# DAC__Sources.net
KiCad netlist of a schematic drawn in Altium Designer
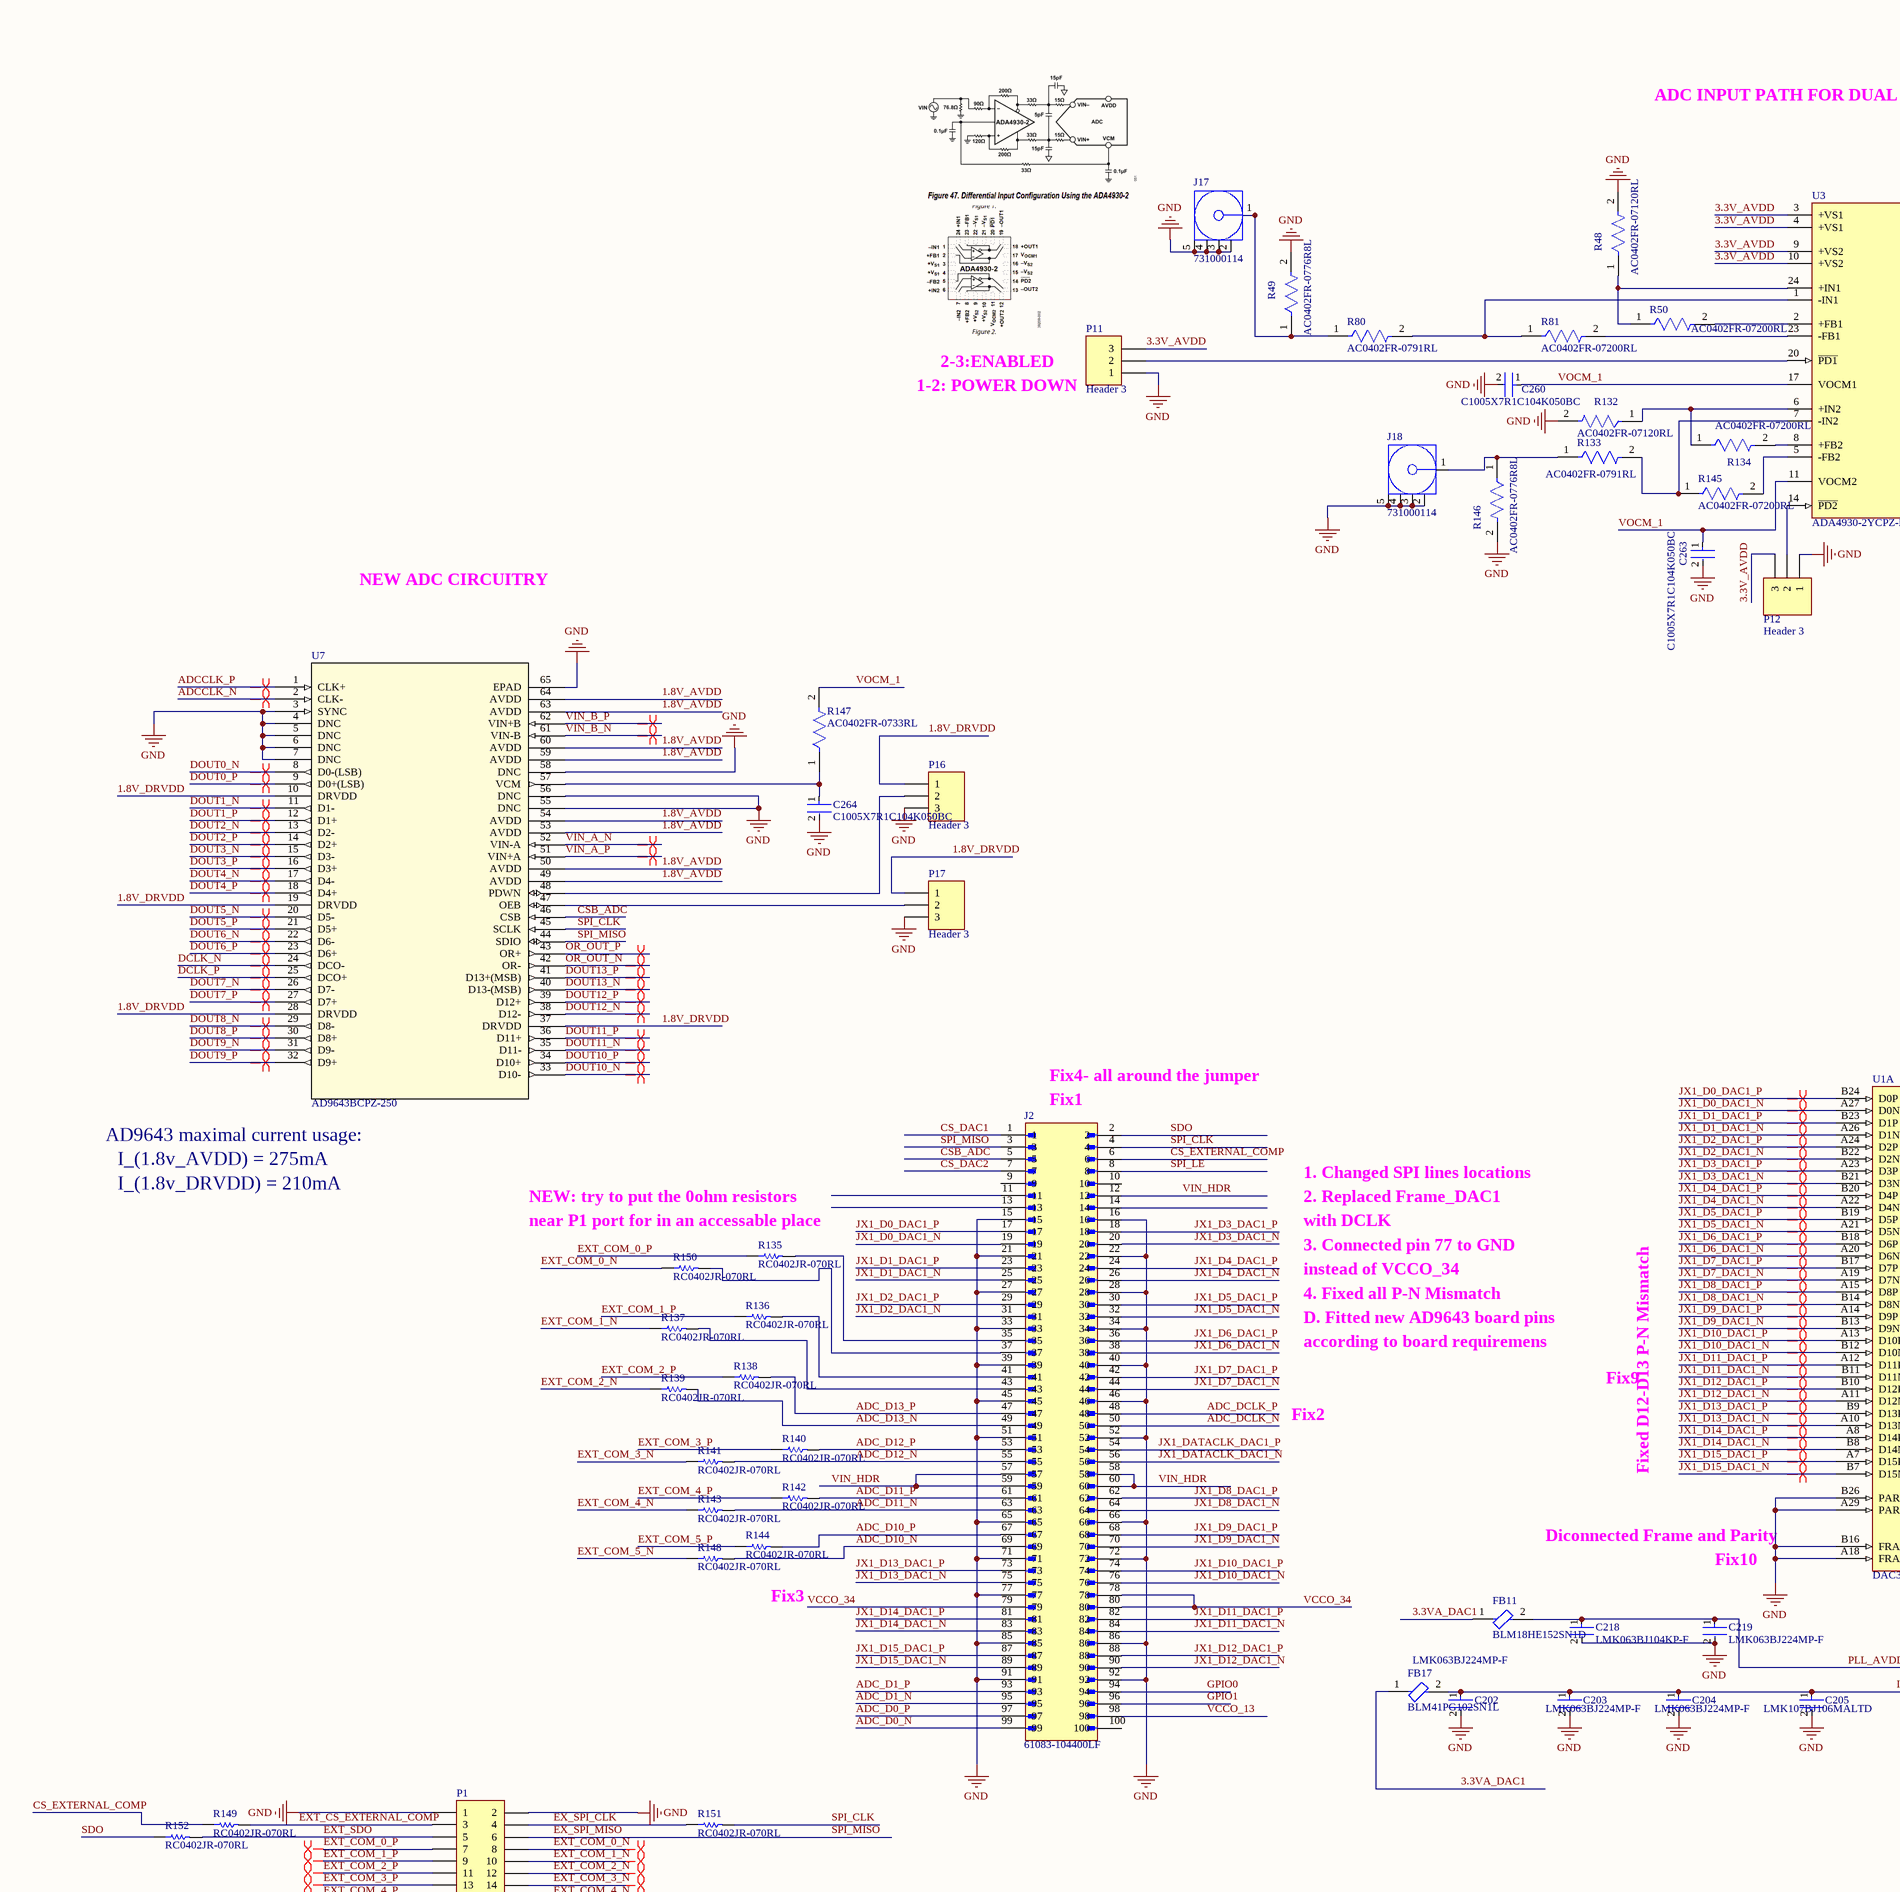
[diagram p0: DACֹֹ_Sources.SchDoc, top left]
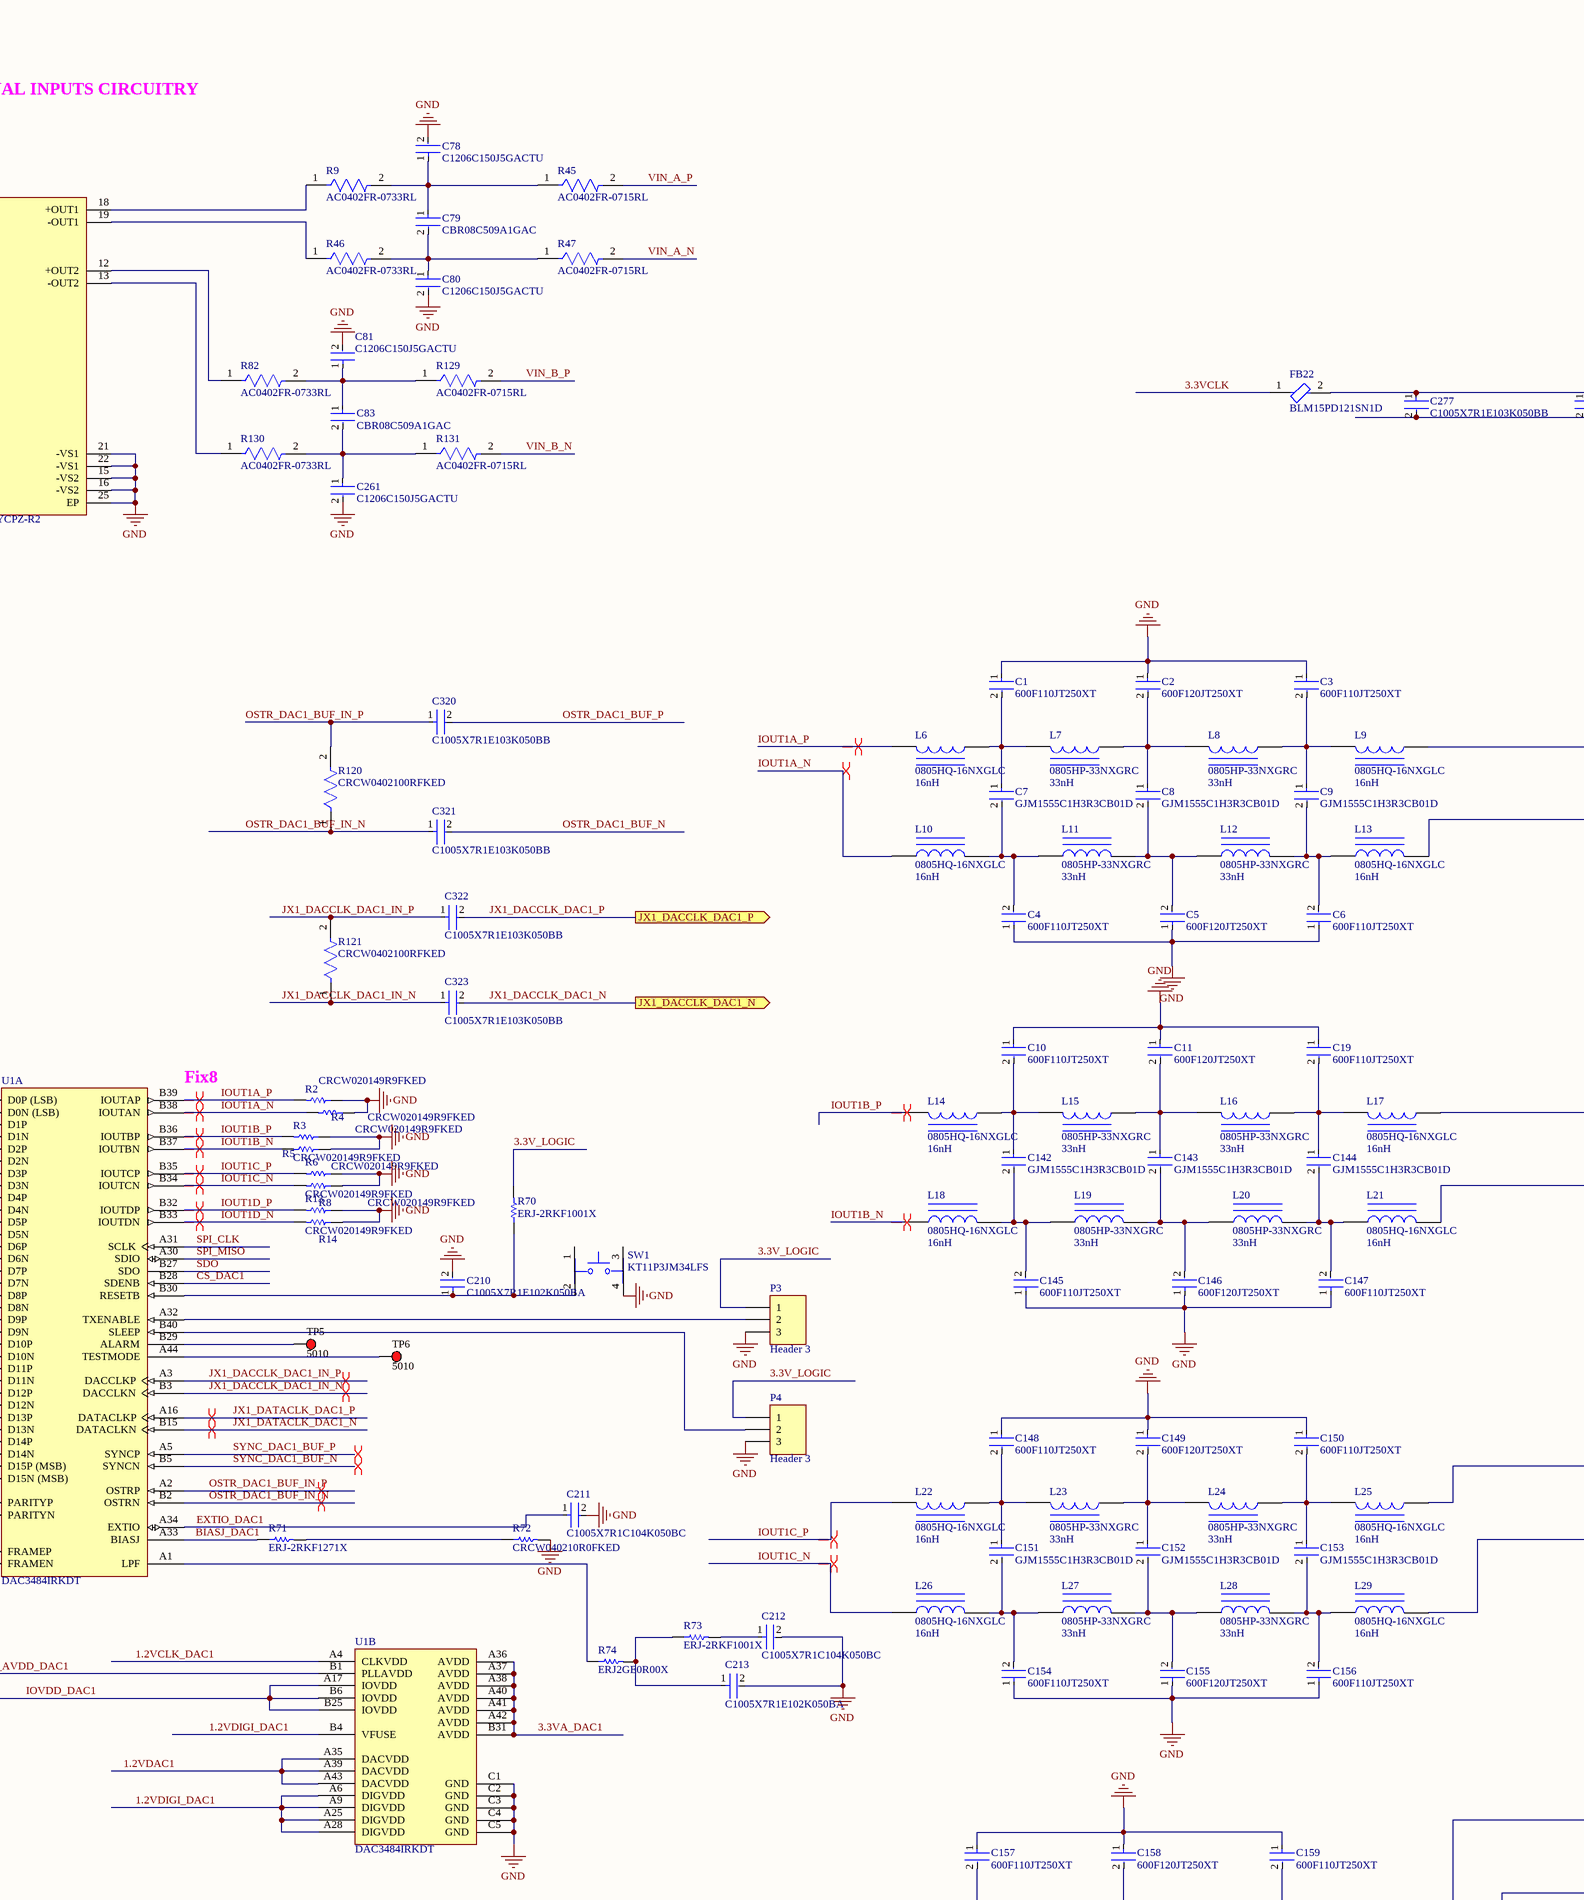
[diagram p1: DACֹֹ_Sources.SchDoc, top middle]
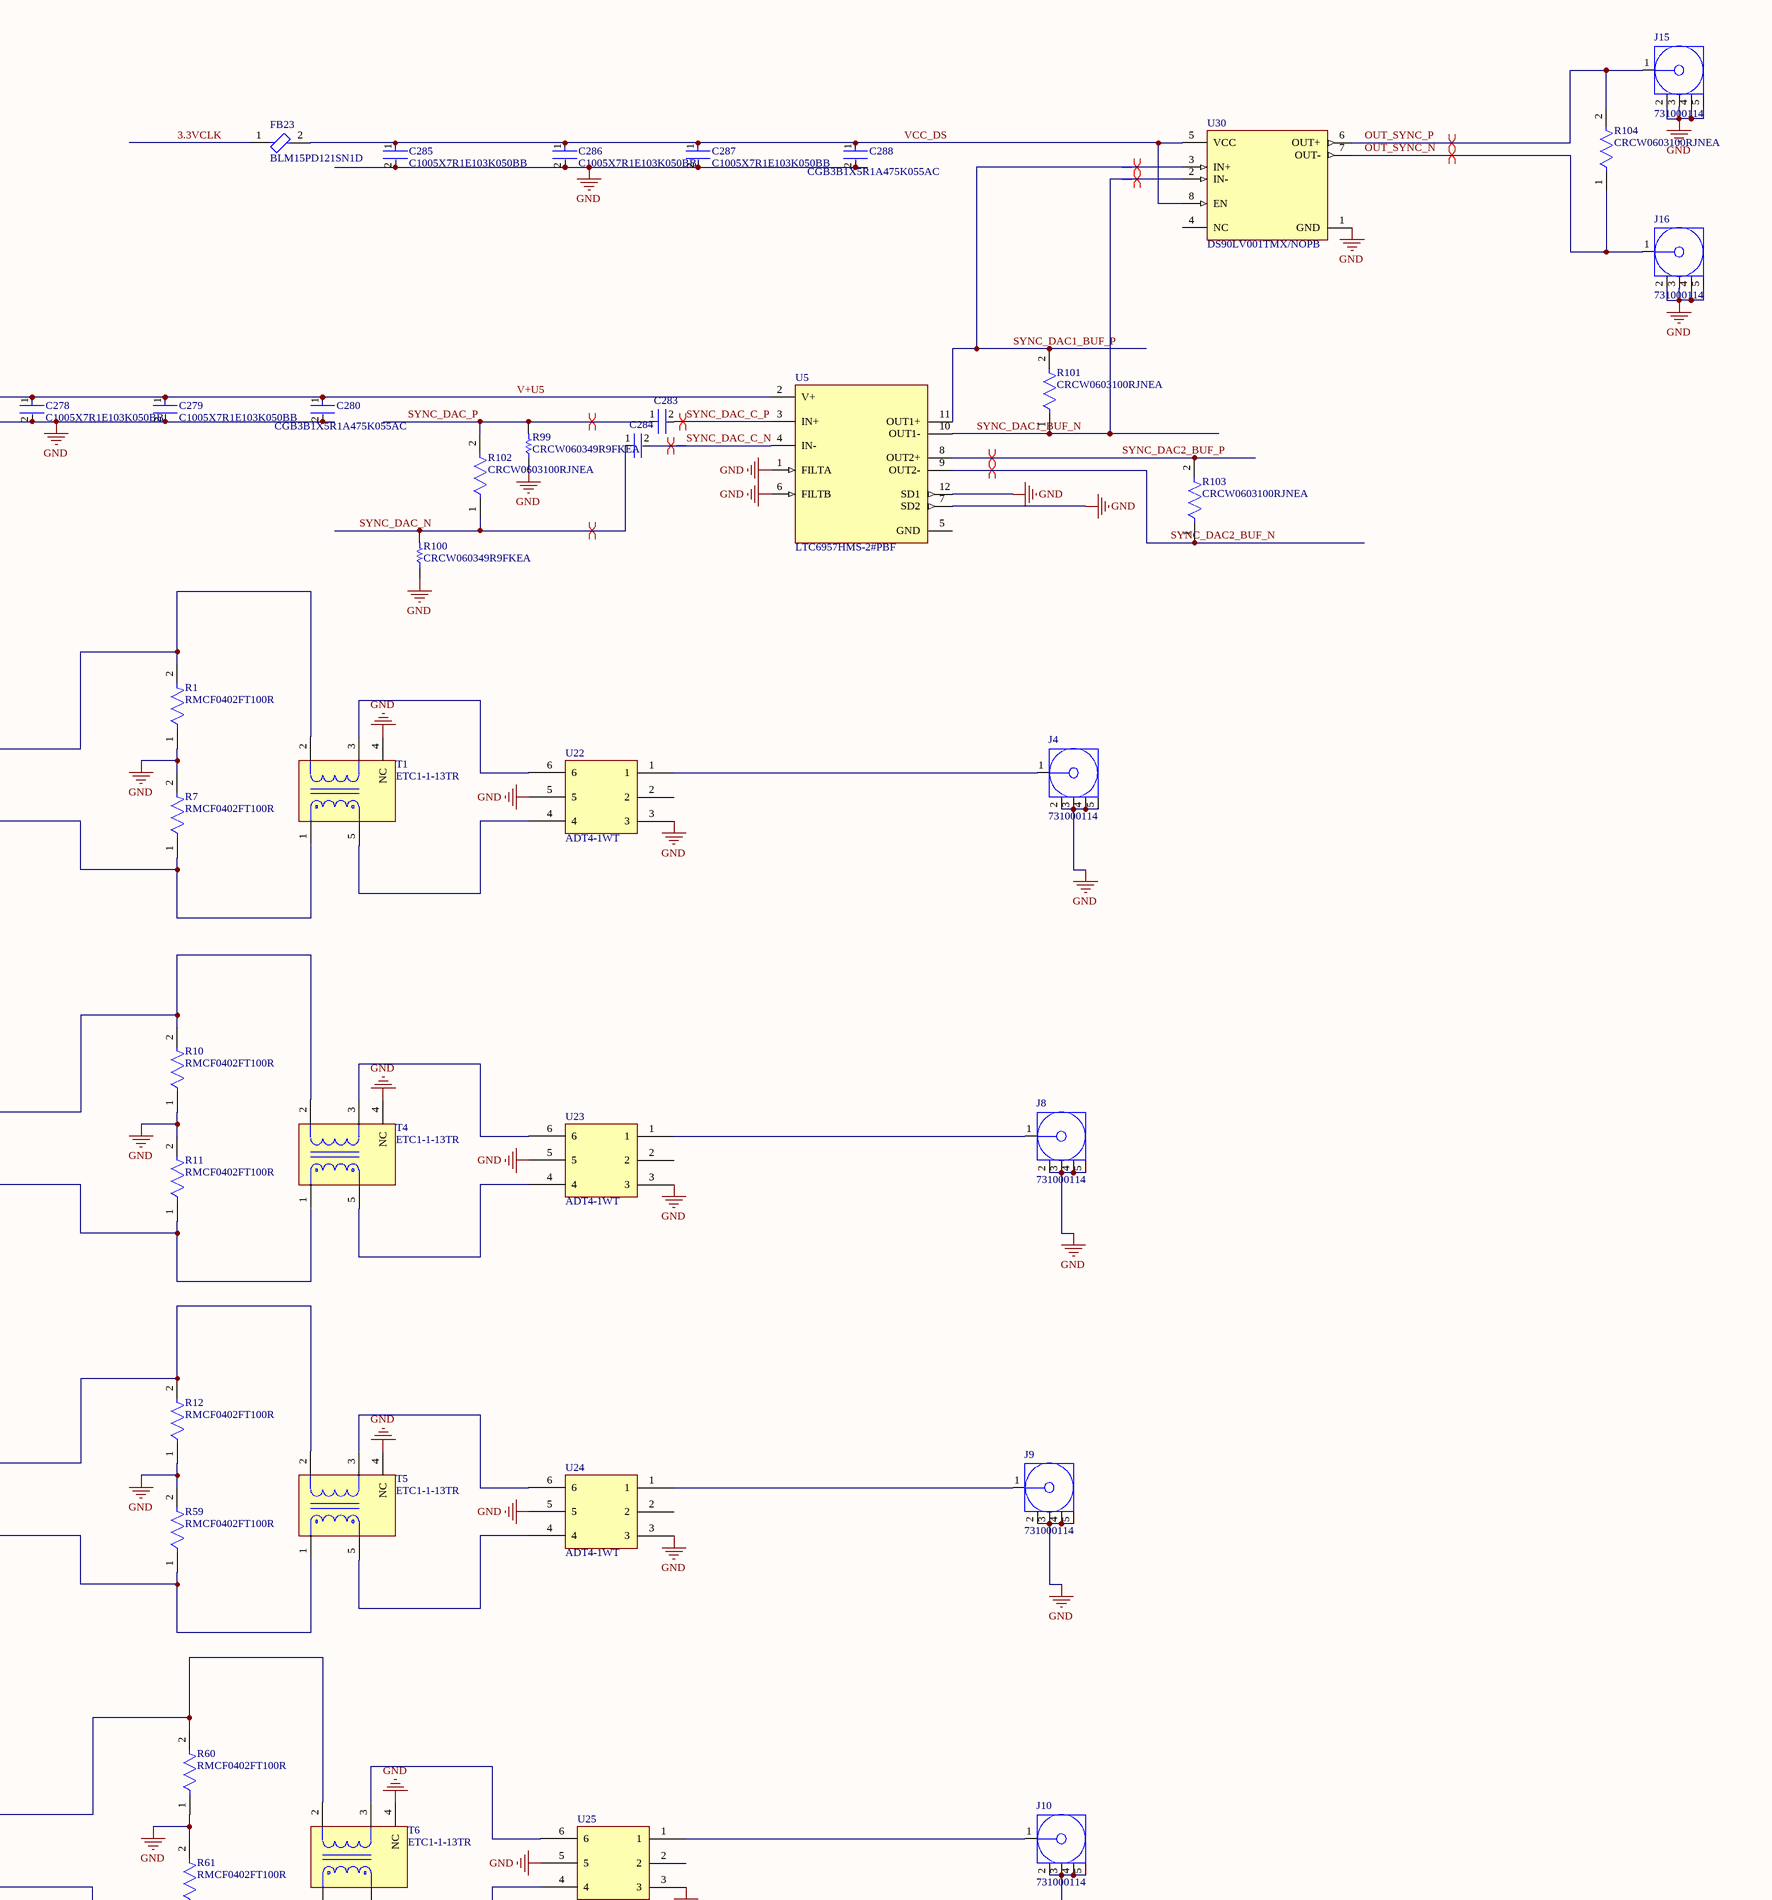
[diagram p2: DACֹֹ_Sources.SchDoc, top right]
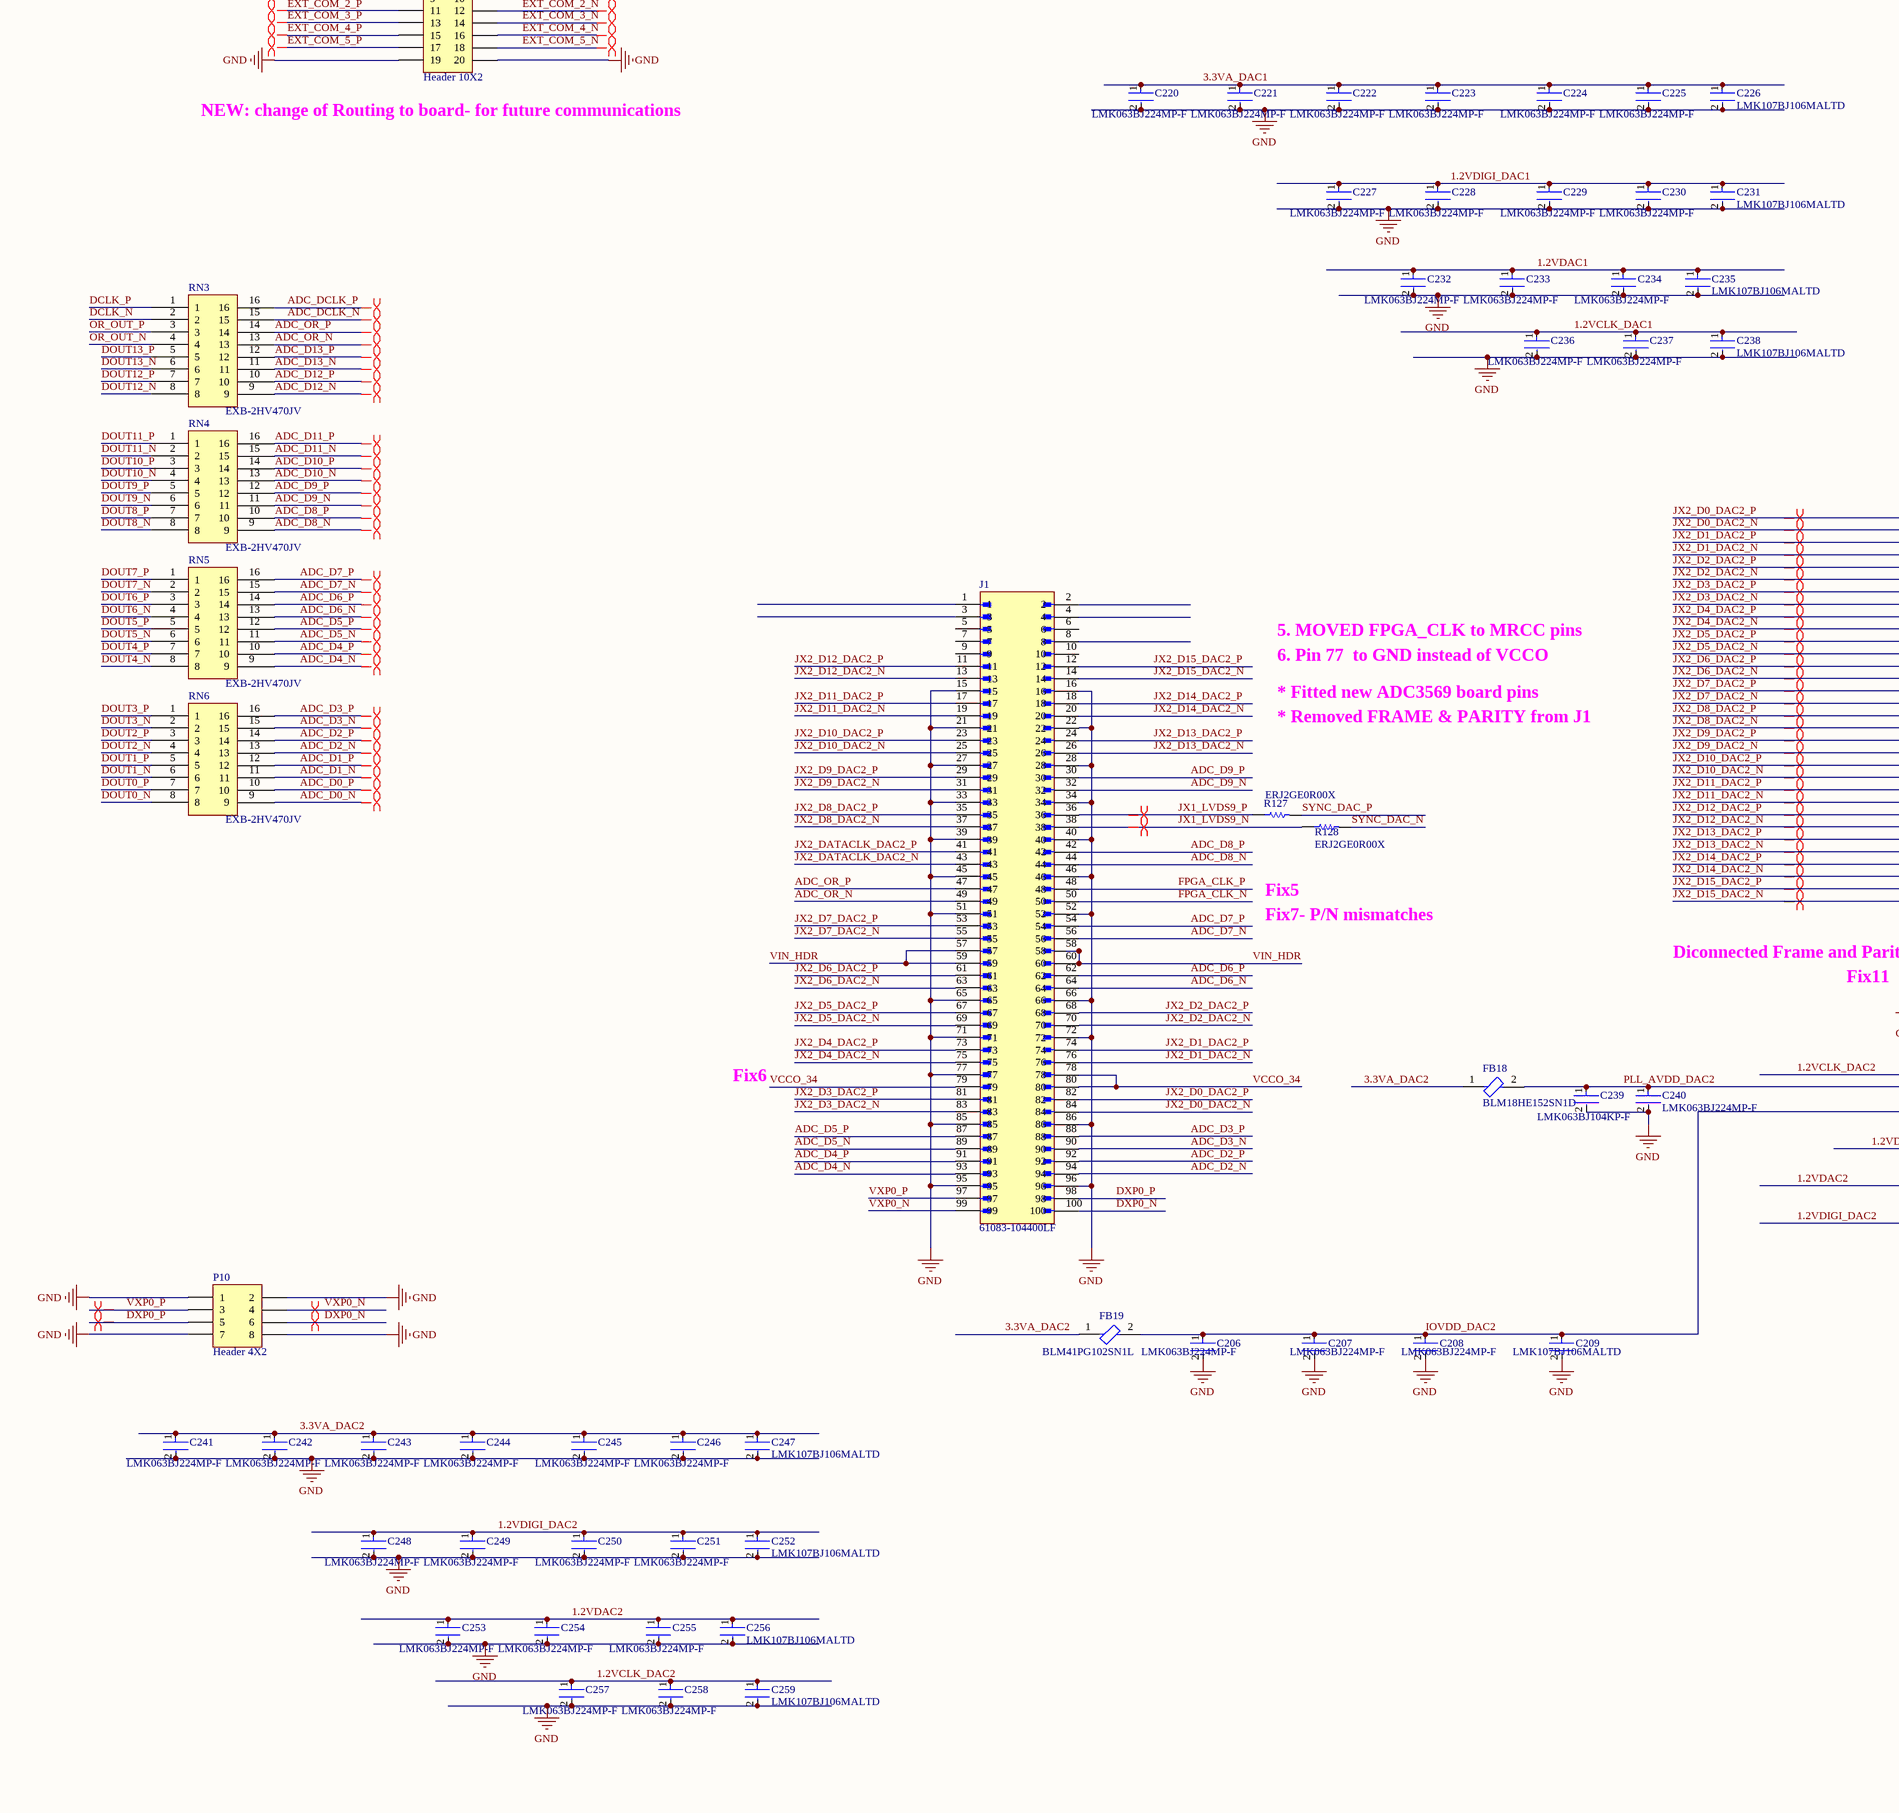
[diagram p3: DACֹֹ_Sources.SchDoc, bottom left]
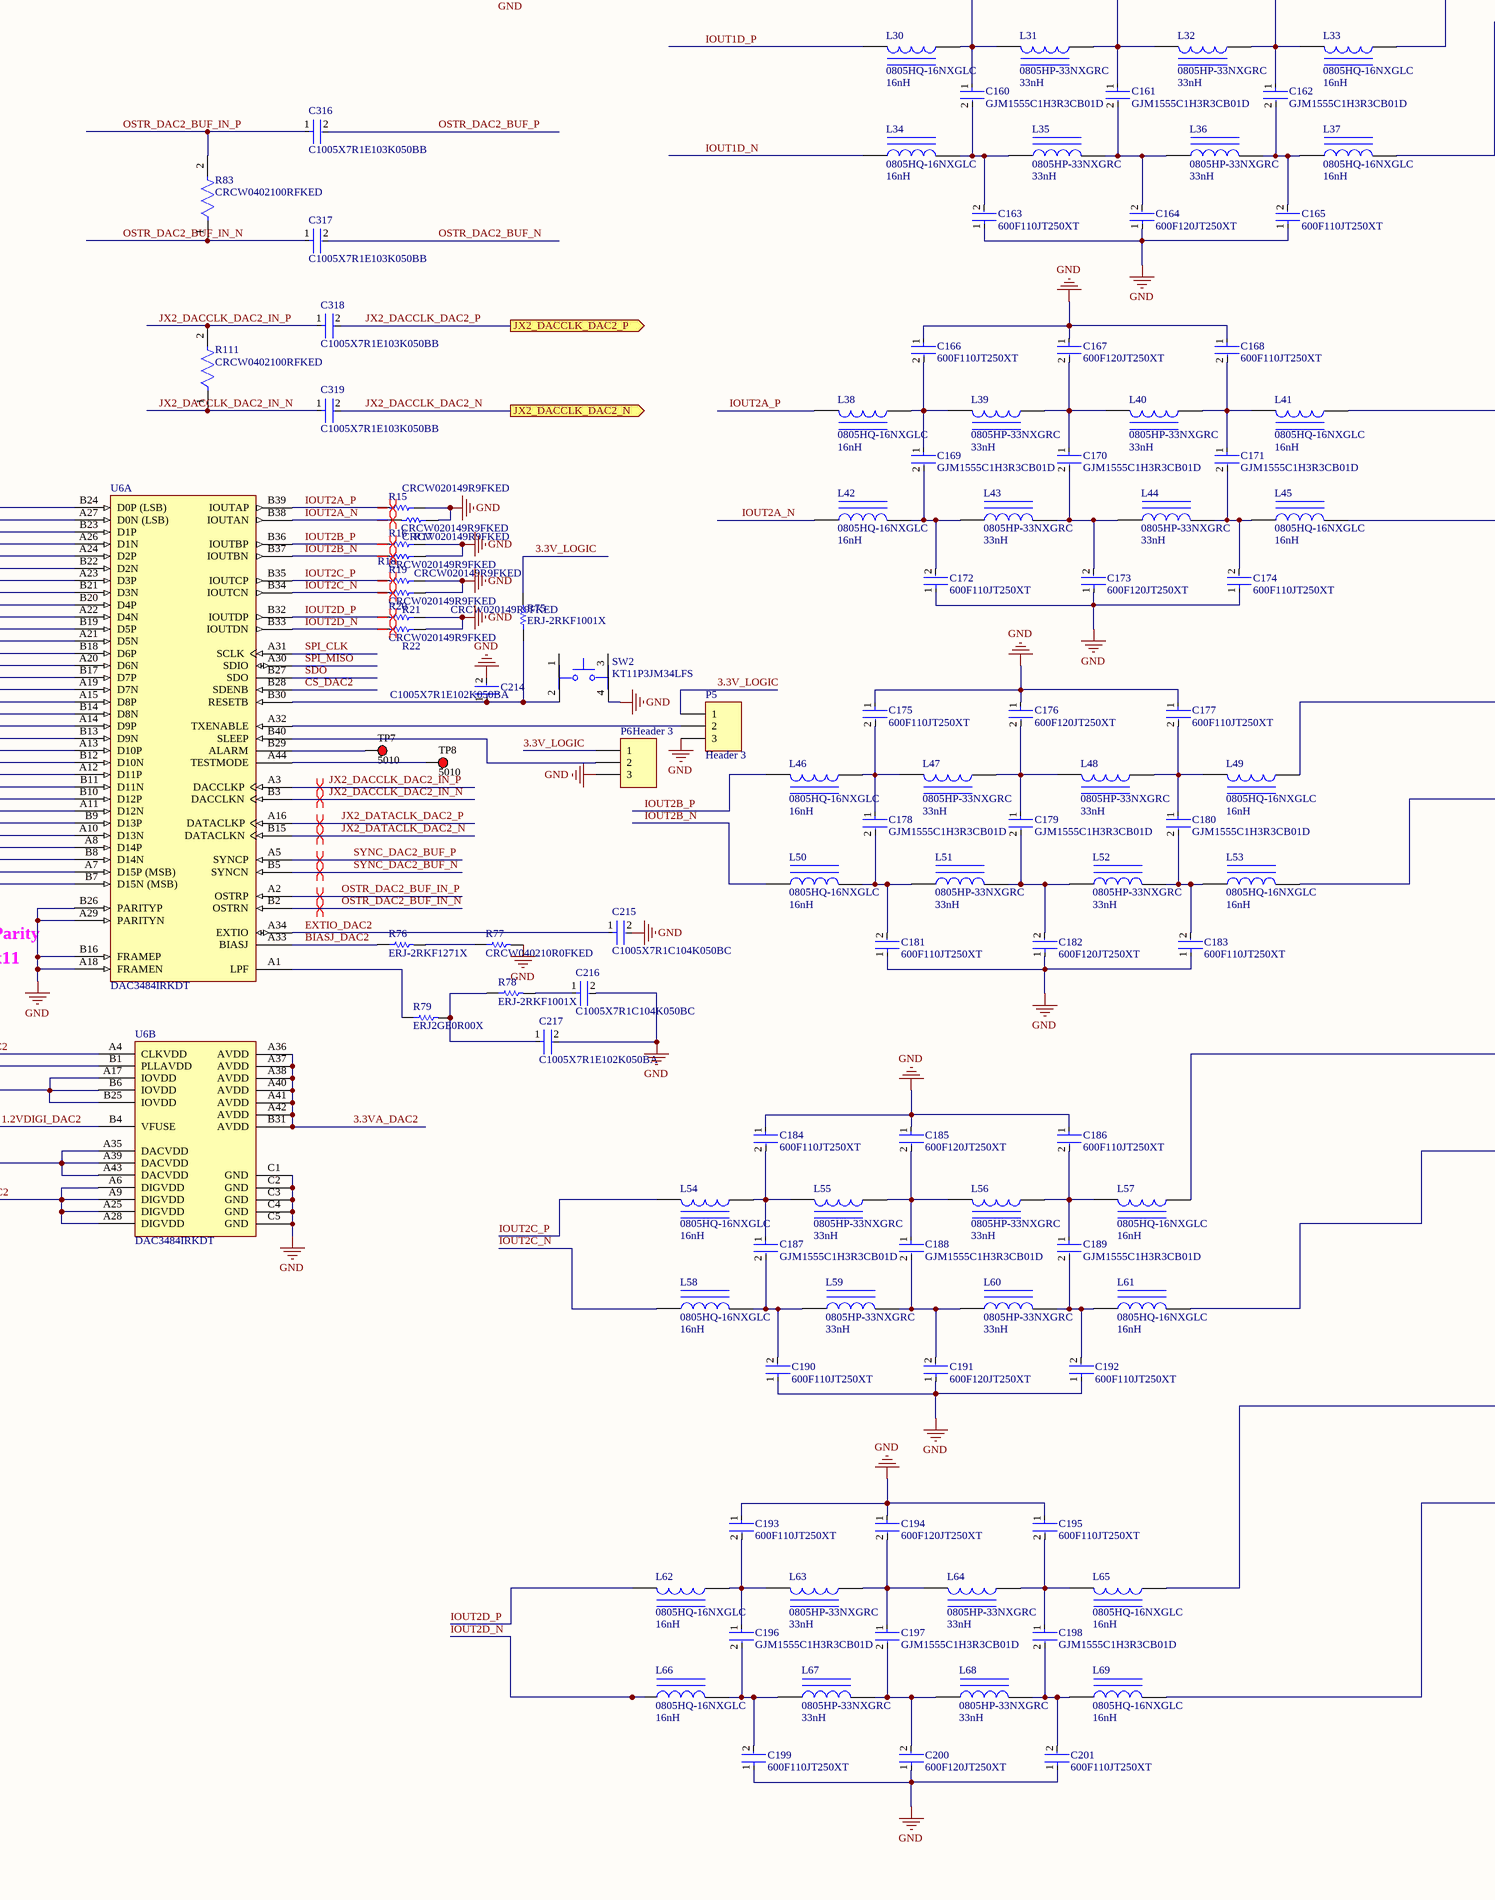
[diagram p4: DACֹֹ_Sources.SchDoc, bottom middle]
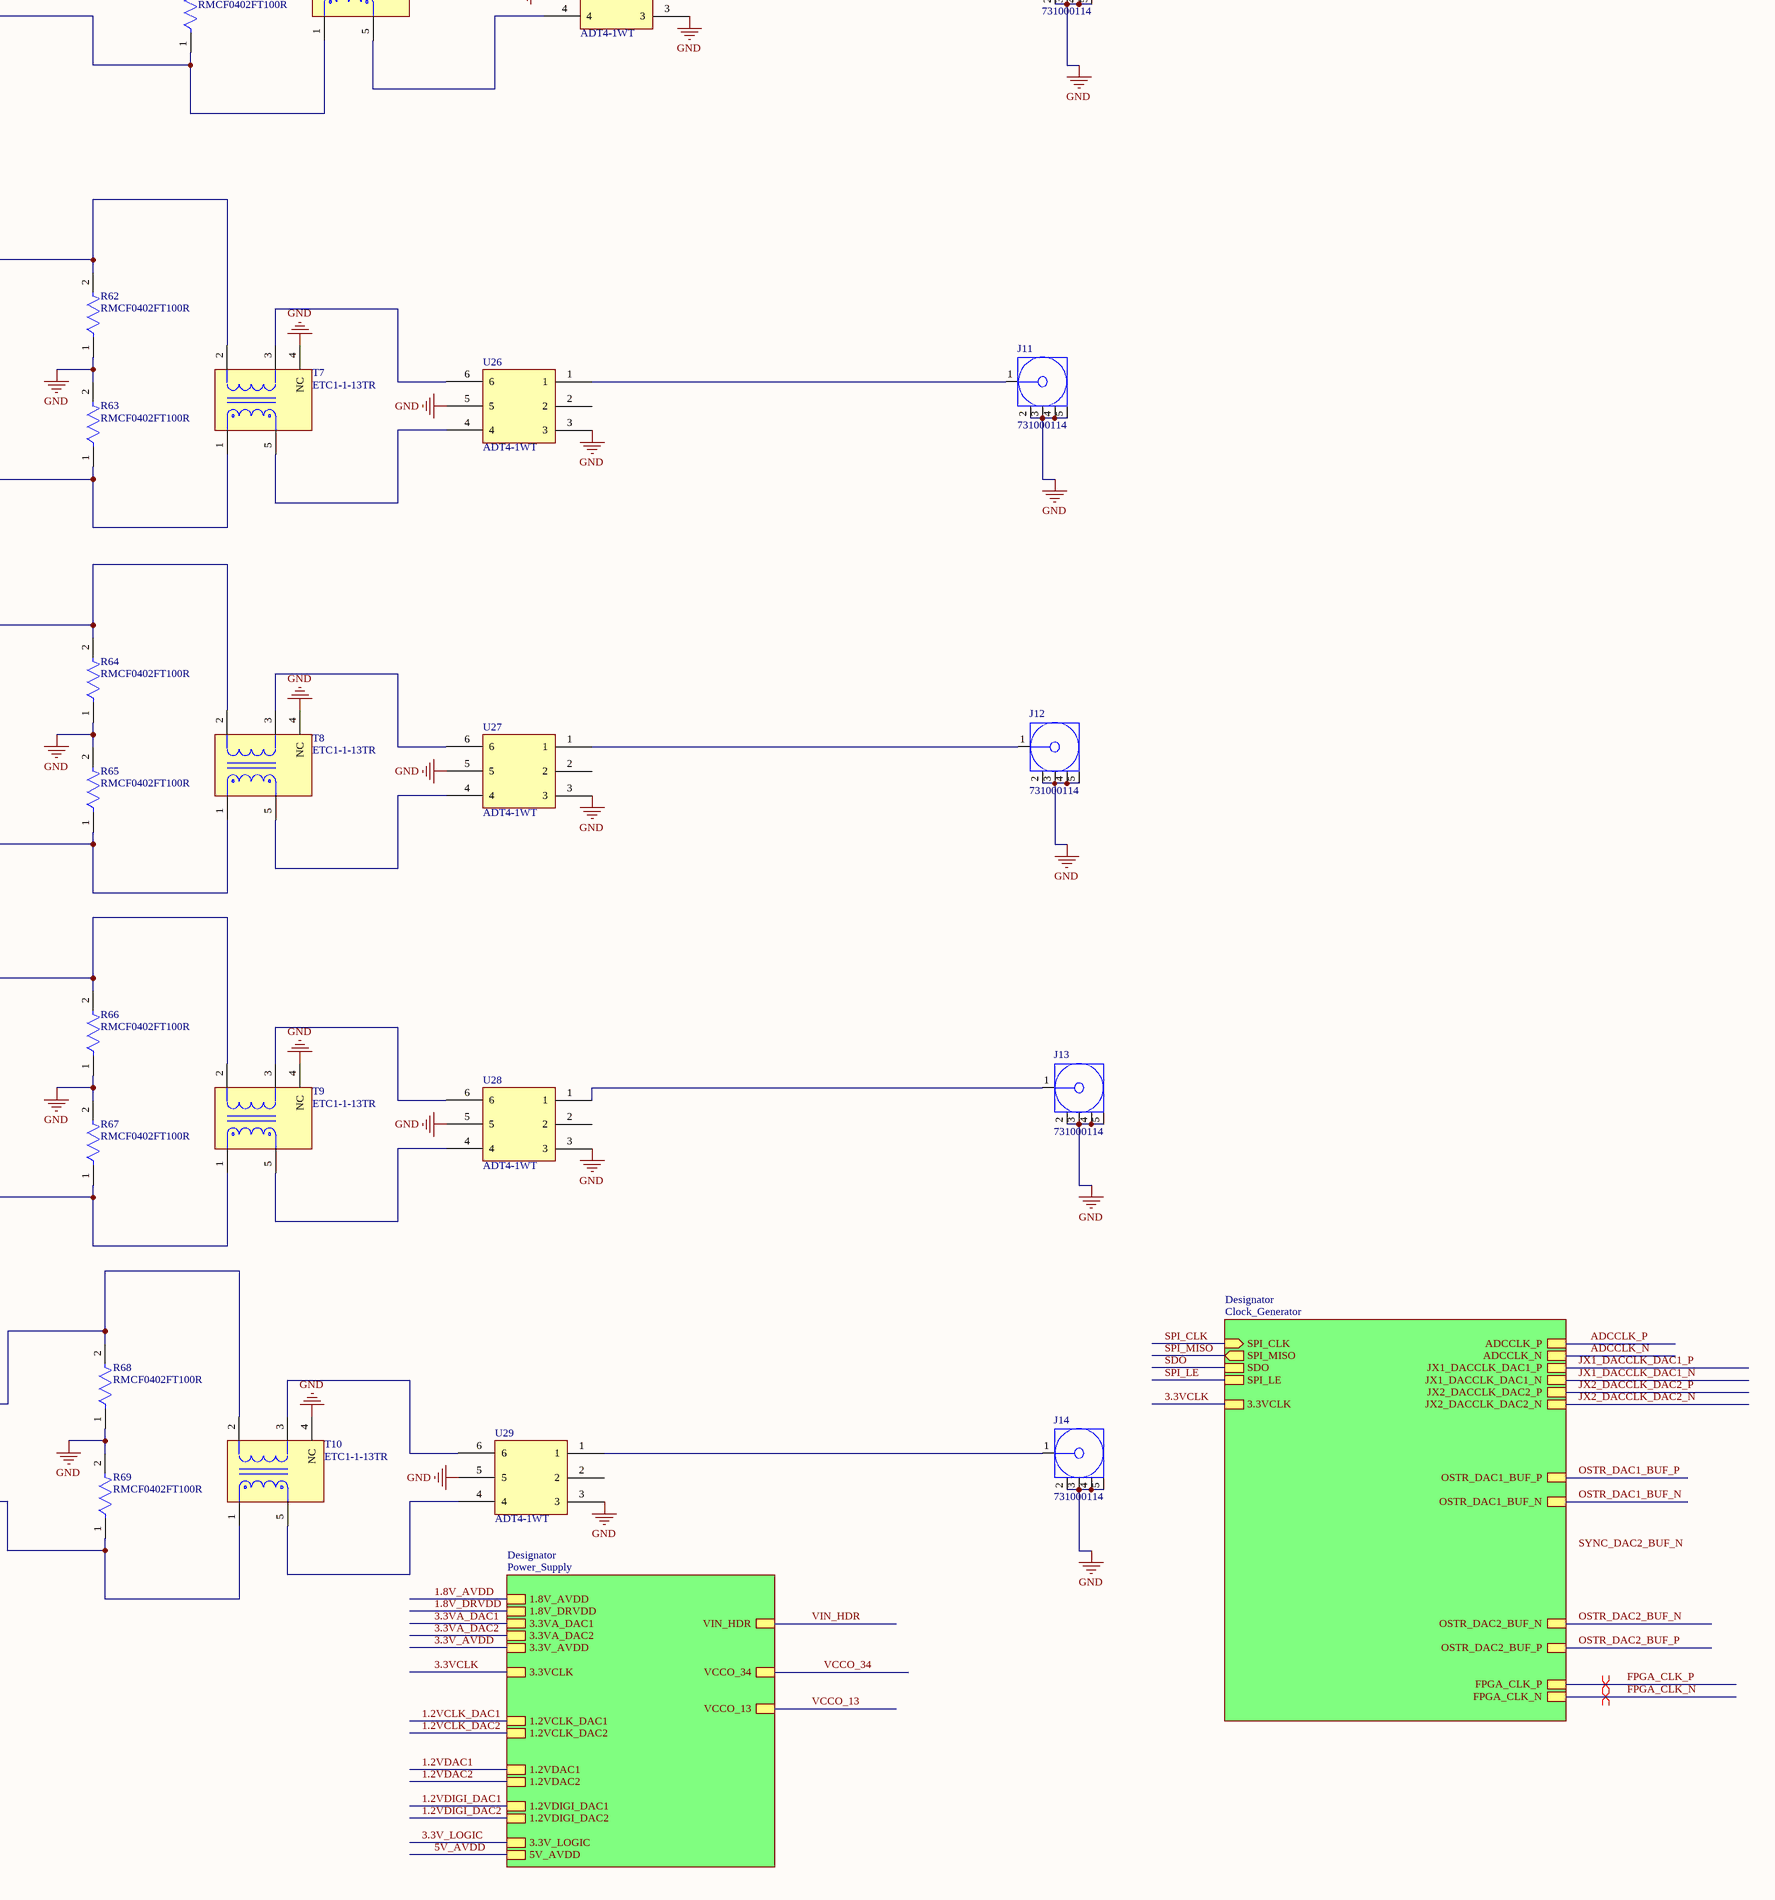
[diagram p5: DACֹֹ_Sources.SchDoc, bottom right]

(export (version "E")
  (design (tool "Eeschema 10.0.6"))
  (components
    (comp (ref "C1")
      (value "600F110JT250XT")
      (footprint "C0805")
      (description "CAP CER 11PF 50V 5% NP0 0805")
      (fields (field (name "TOLERANCE") "0.05") (field (name "MANUFACTURER PART NUMBER") "C0805C110J5GACTU"))
      (libsource (lib "DACֹֹ_Sources") (part "b4654b650e69147ec39a6b967a45e02"))
    )
    (comp (ref "C2")
      (value "600F120JT250XT")
      (footprint "C0805")
      (description "CAP CER 11PF 50V 5% NP0 0805")
      (fields (field (name "TOLERANCE") "0.05") (field (name "MANUFACTURER PART NUMBER") "C0805C110J5GACTU"))
      (libsource (lib "DACֹֹ_Sources") (part "b4654b650e69147ec39a6b967a45e02"))
    )
    (comp (ref "C3")
      (value "600F110JT250XT")
      (footprint "C0805")
      (description "CAP CER 11PF 50V 5% NP0 0805")
      (fields (field (name "TOLERANCE") "0.05") (field (name "MANUFACTURER PART NUMBER") "C0805C110J5GACTU"))
      (libsource (lib "DACֹֹ_Sources") (part "b4654b650e69147ec39a6b967a45e02"))
    )
    (comp (ref "C4")
      (value "600F110JT250XT")
      (footprint "C0805")
      (description "CAP CER 11PF 50V 5% NP0 0805")
      (fields (field (name "TOLERANCE") "0.05") (field (name "MANUFACTURER PART NUMBER") "C0805C110J5GACTU"))
      (libsource (lib "DACֹֹ_Sources") (part "b4654b650e69147ec39a6b967a45e02"))
    )
    (comp (ref "C5")
      (value "600F120JT250XT")
      (footprint "C0805")
      (description "CAP CER 11PF 50V 5% NP0 0805")
      (fields (field (name "TOLERANCE") "0.05") (field (name "MANUFACTURER PART NUMBER") "C0805C110J5GACTU"))
      (libsource (lib "DACֹֹ_Sources") (part "b4654b650e69147ec39a6b967a45e02"))
    )
    (comp (ref "C6")
      (value "600F110JT250XT")
      (footprint "C0805")
      (description "CAP CER 11PF 50V 5% NP0 0805")
      (fields (field (name "TOLERANCE") "0.05") (field (name "MANUFACTURER PART NUMBER") "C0805C110J5GACTU"))
      (libsource (lib "DACֹֹ_Sources") (part "b4654b650e69147ec39a6b967a45e02"))
    )
    (comp (ref "C7")
      (value "GJM1555C1H3R3CB01D")
      (footprint "C0402")
      (description "Multi-Layer Ceramic Capacitor 3.3pF C0G  ±0.25pF 0402 Paper T/R")
      (fields (field (name "VOLTAGE") "50V"))
      (libsource (lib "DACֹֹ_Sources") (part "02cd4be3c70576c341d710602a673aa"))
    )
    (comp (ref "C8")
      (value "GJM1555C1H3R3CB01D")
      (footprint "C0402")
      (description "Multi-Layer Ceramic Capacitor 3.3pF C0G  ±0.25pF 0402 Paper T/R")
      (fields (field (name "VOLTAGE") "50V"))
      (libsource (lib "DACֹֹ_Sources") (part "02cd4be3c70576c341d710602a673aa"))
    )
    (comp (ref "C9")
      (value "GJM1555C1H3R3CB01D")
      (footprint "C0402")
      (description "Multi-Layer Ceramic Capacitor 3.3pF C0G  ±0.25pF 0402 Paper T/R")
      (fields (field (name "VOLTAGE") "50V"))
      (libsource (lib "DACֹֹ_Sources") (part "02cd4be3c70576c341d710602a673aa"))
    )
    (comp (ref "C10")
      (value "600F110JT250XT")
      (footprint "C0805")
      (description "CAP CER 11PF 50V 5% NP0 0805")
      (fields (field (name "TOLERANCE") "0.05") (field (name "MANUFACTURER PART NUMBER") "C0805C110J5GACTU"))
      (libsource (lib "DACֹֹ_Sources") (part "b4654b650e69147ec39a6b967a45e02"))
    )
    (comp (ref "C11")
      (value "600F120JT250XT")
      (footprint "C0805")
      (description "CAP CER 11PF 50V 5% NP0 0805")
      (fields (field (name "TOLERANCE") "0.05") (field (name "MANUFACTURER PART NUMBER") "C0805C110J5GACTU"))
      (libsource (lib "DACֹֹ_Sources") (part "b4654b650e69147ec39a6b967a45e02"))
    )
    (comp (ref "C19")
      (value "600F110JT250XT")
      (footprint "C0805")
      (description "CAP CER 11PF 50V 5% NP0 0805")
      (fields (field (name "TOLERANCE") "0.05") (field (name "MANUFACTURER PART NUMBER") "C0805C110J5GACTU"))
      (libsource (lib "DACֹֹ_Sources") (part "b4654b650e69147ec39a6b967a45e02"))
    )
    (comp (ref "C78")
      (value "C1206C150J5GACTU")
      (footprint "C1206")
      (description "1206 C 15pF Ceramic Multilayer Capacitor; 50 VDC; +125degC; C0G Dielec; +/-5%")
      (fields (field (name "TOLERANCE") "0.05") (field (name "MANUFACTURER") "KEMET"))
      (libsource (lib "Simulation Generic Components") (part "b4654b650e69147ec39a6b967a45e02"))
    )
    (comp (ref "C79")
      (value "CBR08C509A1GAC")
      (footprint "C0805")
      (description "CAP CER 5PF 100V NP0 0805")
      (fields (field (name "TOLERANCE") "0.05 pF") (field (name "MANUFACTURER") "KEMET"))
      (libsource (lib "Simulation Generic Components") (part "11868f565c42a9108669ba33697ecf6"))
    )
    (comp (ref "C80")
      (value "C1206C150J5GACTU")
      (footprint "C1206")
      (description "1206 C 15pF Ceramic Multilayer Capacitor; 50 VDC; +125degC; C0G Dielec; +/-5%")
      (fields (field (name "TOLERANCE") "0.05") (field (name "MANUFACTURER") "KEMET"))
      (libsource (lib "Simulation Generic Components") (part "b4654b650e69147ec39a6b967a45e02"))
    )
    (comp (ref "C81")
      (value "C1206C150J5GACTU")
      (footprint "C1206")
      (description "1206 C 15pF Ceramic Multilayer Capacitor; 50 VDC; +125degC; C0G Dielec; +/-5%")
      (fields (field (name "TOLERANCE") "0.05") (field (name "MANUFACTURER") "KEMET"))
      (libsource (lib "Simulation Generic Components") (part "b4654b650e69147ec39a6b967a45e02"))
    )
    (comp (ref "C83")
      (value "CBR08C509A1GAC")
      (footprint "C0805")
      (description "CAP CER 5PF 100V NP0 0805")
      (fields (field (name "TOLERANCE") "0.05 pF") (field (name "MANUFACTURER") "KEMET"))
      (libsource (lib "Simulation Generic Components") (part "11868f565c42a9108669ba33697ecf6"))
    )
    (comp (ref "C142")
      (value "GJM1555C1H3R3CB01D")
      (footprint "C0402")
      (description "Multi-Layer Ceramic Capacitor 3.3pF C0G  ±0.25pF 0402 Paper T/R")
      (fields (field (name "VOLTAGE") "50V"))
      (libsource (lib "DACֹֹ_Sources") (part "02cd4be3c70576c341d710602a673aa"))
    )
    (comp (ref "C143")
      (value "GJM1555C1H3R3CB01D")
      (footprint "C0402")
      (description "Multi-Layer Ceramic Capacitor 3.3pF C0G  ±0.25pF 0402 Paper T/R")
      (fields (field (name "VOLTAGE") "50V"))
      (libsource (lib "DACֹֹ_Sources") (part "02cd4be3c70576c341d710602a673aa"))
    )
    (comp (ref "C144")
      (value "GJM1555C1H3R3CB01D")
      (footprint "C0402")
      (description "Multi-Layer Ceramic Capacitor 3.3pF C0G  ±0.25pF 0402 Paper T/R")
      (fields (field (name "VOLTAGE") "50V"))
      (libsource (lib "DACֹֹ_Sources") (part "02cd4be3c70576c341d710602a673aa"))
    )
    (comp (ref "C145")
      (value "600F110JT250XT")
      (footprint "C0805")
      (description "CAP CER 11PF 50V 5% NP0 0805")
      (fields (field (name "TOLERANCE") "0.05") (field (name "MANUFACTURER PART NUMBER") "C0805C110J5GACTU"))
      (libsource (lib "DACֹֹ_Sources") (part "b4654b650e69147ec39a6b967a45e02"))
    )
    (comp (ref "C146")
      (value "600F120JT250XT")
      (footprint "C0805")
      (description "CAP CER 11PF 50V 5% NP0 0805")
      (fields (field (name "TOLERANCE") "0.05") (field (name "MANUFACTURER PART NUMBER") "C0805C110J5GACTU"))
      (libsource (lib "DACֹֹ_Sources") (part "b4654b650e69147ec39a6b967a45e02"))
    )
    (comp (ref "C147")
      (value "600F110JT250XT")
      (footprint "C0805")
      (description "CAP CER 11PF 50V 5% NP0 0805")
      (fields (field (name "TOLERANCE") "0.05") (field (name "MANUFACTURER PART NUMBER") "C0805C110J5GACTU"))
      (libsource (lib "DACֹֹ_Sources") (part "b4654b650e69147ec39a6b967a45e02"))
    )
    (comp (ref "C148")
      (value "600F110JT250XT")
      (footprint "C0805")
      (description "CAP CER 11PF 50V 5% NP0 0805")
      (fields (field (name "TOLERANCE") "0.05") (field (name "MANUFACTURER PART NUMBER") "C0805C110J5GACTU"))
      (libsource (lib "DACֹֹ_Sources") (part "b4654b650e69147ec39a6b967a45e02"))
    )
    (comp (ref "C149")
      (value "600F120JT250XT")
      (footprint "C0805")
      (description "CAP CER 11PF 50V 5% NP0 0805")
      (fields (field (name "TOLERANCE") "0.05") (field (name "MANUFACTURER PART NUMBER") "C0805C110J5GACTU"))
      (libsource (lib "DACֹֹ_Sources") (part "b4654b650e69147ec39a6b967a45e02"))
    )
    (comp (ref "C150")
      (value "600F110JT250XT")
      (footprint "C0805")
      (description "CAP CER 11PF 50V 5% NP0 0805")
      (fields (field (name "TOLERANCE") "0.05") (field (name "MANUFACTURER PART NUMBER") "C0805C110J5GACTU"))
      (libsource (lib "DACֹֹ_Sources") (part "b4654b650e69147ec39a6b967a45e02"))
    )
    (comp (ref "C151")
      (value "GJM1555C1H3R3CB01D")
      (footprint "C0402")
      (description "Multi-Layer Ceramic Capacitor 3.3pF C0G  ±0.25pF 0402 Paper T/R")
      (fields (field (name "VOLTAGE") "50V"))
      (libsource (lib "DACֹֹ_Sources") (part "02cd4be3c70576c341d710602a673aa"))
    )
    (comp (ref "C152")
      (value "GJM1555C1H3R3CB01D")
      (footprint "C0402")
      (description "Multi-Layer Ceramic Capacitor 3.3pF C0G  ±0.25pF 0402 Paper T/R")
      (fields (field (name "VOLTAGE") "50V"))
      (libsource (lib "DACֹֹ_Sources") (part "02cd4be3c70576c341d710602a673aa"))
    )
    (comp (ref "C153")
      (value "GJM1555C1H3R3CB01D")
      (footprint "C0402")
      (description "Multi-Layer Ceramic Capacitor 3.3pF C0G  ±0.25pF 0402 Paper T/R")
      (fields (field (name "VOLTAGE") "50V"))
      (libsource (lib "DACֹֹ_Sources") (part "02cd4be3c70576c341d710602a673aa"))
    )
    (comp (ref "C154")
      (value "600F110JT250XT")
      (footprint "C0805")
      (description "CAP CER 11PF 50V 5% NP0 0805")
      (fields (field (name "TOLERANCE") "0.05") (field (name "MANUFACTURER PART NUMBER") "C0805C110J5GACTU"))
      (libsource (lib "DACֹֹ_Sources") (part "b4654b650e69147ec39a6b967a45e02"))
    )
    (comp (ref "C155")
      (value "600F120JT250XT")
      (footprint "C0805")
      (description "CAP CER 11PF 50V 5% NP0 0805")
      (fields (field (name "TOLERANCE") "0.05") (field (name "MANUFACTURER PART NUMBER") "C0805C110J5GACTU"))
      (libsource (lib "DACֹֹ_Sources") (part "b4654b650e69147ec39a6b967a45e02"))
    )
    (comp (ref "C156")
      (value "600F110JT250XT")
      (footprint "C0805")
      (description "CAP CER 11PF 50V 5% NP0 0805")
      (fields (field (name "TOLERANCE") "0.05") (field (name "MANUFACTURER PART NUMBER") "C0805C110J5GACTU"))
      (libsource (lib "DACֹֹ_Sources") (part "b4654b650e69147ec39a6b967a45e02"))
    )
    (comp (ref "C157")
      (value "600F110JT250XT")
      (footprint "C0805")
      (description "CAP CER 11PF 50V 5% NP0 0805")
      (fields (field (name "TOLERANCE") "0.05") (field (name "MANUFACTURER PART NUMBER") "C0805C110J5GACTU"))
      (libsource (lib "DACֹֹ_Sources") (part "b4654b650e69147ec39a6b967a45e02"))
    )
    (comp (ref "C158")
      (value "600F120JT250XT")
      (footprint "C0805")
      (description "CAP CER 11PF 50V 5% NP0 0805")
      (fields (field (name "TOLERANCE") "0.05") (field (name "MANUFACTURER PART NUMBER") "C0805C110J5GACTU"))
      (libsource (lib "DACֹֹ_Sources") (part "b4654b650e69147ec39a6b967a45e02"))
    )
    (comp (ref "C159")
      (value "600F110JT250XT")
      (footprint "C0805")
      (description "CAP CER 11PF 50V 5% NP0 0805")
      (fields (field (name "TOLERANCE") "0.05") (field (name "MANUFACTURER PART NUMBER") "C0805C110J5GACTU"))
      (libsource (lib "DACֹֹ_Sources") (part "b4654b650e69147ec39a6b967a45e02"))
    )
    (comp (ref "C160")
      (value "GJM1555C1H3R3CB01D")
      (footprint "C0402")
      (description "Multi-Layer Ceramic Capacitor 3.3pF C0G  ±0.25pF 0402 Paper T/R")
      (fields (field (name "VOLTAGE") "50V"))
      (libsource (lib "DACֹֹ_Sources") (part "02cd4be3c70576c341d710602a673aa"))
    )
    (comp (ref "C161")
      (value "GJM1555C1H3R3CB01D")
      (footprint "C0402")
      (description "Multi-Layer Ceramic Capacitor 3.3pF C0G  ±0.25pF 0402 Paper T/R")
      (fields (field (name "VOLTAGE") "50V"))
      (libsource (lib "DACֹֹ_Sources") (part "02cd4be3c70576c341d710602a673aa"))
    )
    (comp (ref "C162")
      (value "GJM1555C1H3R3CB01D")
      (footprint "C0402")
      (description "Multi-Layer Ceramic Capacitor 3.3pF C0G  ±0.25pF 0402 Paper T/R")
      (fields (field (name "VOLTAGE") "50V"))
      (libsource (lib "DACֹֹ_Sources") (part "02cd4be3c70576c341d710602a673aa"))
    )
    (comp (ref "C163")
      (value "600F110JT250XT")
      (footprint "C0805")
      (description "CAP CER 11PF 50V 5% NP0 0805")
      (fields (field (name "TOLERANCE") "0.05") (field (name "MANUFACTURER PART NUMBER") "C0805C110J5GACTU"))
      (libsource (lib "DACֹֹ_Sources") (part "b4654b650e69147ec39a6b967a45e02"))
    )
    (comp (ref "C164")
      (value "600F120JT250XT")
      (footprint "C0805")
      (description "CAP CER 11PF 50V 5% NP0 0805")
      (fields (field (name "TOLERANCE") "0.05") (field (name "MANUFACTURER PART NUMBER") "C0805C110J5GACTU"))
      (libsource (lib "DACֹֹ_Sources") (part "b4654b650e69147ec39a6b967a45e02"))
    )
    (comp (ref "C165")
      (value "600F110JT250XT")
      (footprint "C0805")
      (description "CAP CER 11PF 50V 5% NP0 0805")
      (fields (field (name "TOLERANCE") "0.05") (field (name "MANUFACTURER PART NUMBER") "C0805C110J5GACTU"))
      (libsource (lib "DACֹֹ_Sources") (part "b4654b650e69147ec39a6b967a45e02"))
    )
    (comp (ref "C166")
      (value "600F110JT250XT")
      (footprint "C0805")
      (description "CAP CER 11PF 50V 5% NP0 0805")
      (fields (field (name "TOLERANCE") "0.05") (field (name "MANUFACTURER PART NUMBER") "C0805C110J5GACTU"))
      (libsource (lib "DACֹֹ_Sources") (part "b4654b650e69147ec39a6b967a45e02"))
    )
    (comp (ref "C167")
      (value "600F120JT250XT")
      (footprint "C0805")
      (description "CAP CER 11PF 50V 5% NP0 0805")
      (fields (field (name "TOLERANCE") "0.05") (field (name "MANUFACTURER PART NUMBER") "C0805C110J5GACTU"))
      (libsource (lib "DACֹֹ_Sources") (part "b4654b650e69147ec39a6b967a45e02"))
    )
    (comp (ref "C168")
      (value "600F110JT250XT")
      (footprint "C0805")
      (description "CAP CER 11PF 50V 5% NP0 0805")
      (fields (field (name "TOLERANCE") "0.05") (field (name "MANUFACTURER PART NUMBER") "C0805C110J5GACTU"))
      (libsource (lib "DACֹֹ_Sources") (part "b4654b650e69147ec39a6b967a45e02"))
    )
    (comp (ref "C169")
      (value "GJM1555C1H3R3CB01D")
      (footprint "C0402")
      (description "Multi-Layer Ceramic Capacitor 3.3pF C0G  ±0.25pF 0402 Paper T/R")
      (fields (field (name "VOLTAGE") "50V"))
      (libsource (lib "DACֹֹ_Sources") (part "02cd4be3c70576c341d710602a673aa"))
    )
    (comp (ref "C170")
      (value "GJM1555C1H3R3CB01D")
      (footprint "C0402")
      (description "Multi-Layer Ceramic Capacitor 3.3pF C0G  ±0.25pF 0402 Paper T/R")
      (fields (field (name "VOLTAGE") "50V"))
      (libsource (lib "DACֹֹ_Sources") (part "02cd4be3c70576c341d710602a673aa"))
    )
    (comp (ref "C171")
      (value "GJM1555C1H3R3CB01D")
      (footprint "C0402")
      (description "Multi-Layer Ceramic Capacitor 3.3pF C0G  ±0.25pF 0402 Paper T/R")
      (fields (field (name "VOLTAGE") "50V"))
      (libsource (lib "DACֹֹ_Sources") (part "02cd4be3c70576c341d710602a673aa"))
    )
    (comp (ref "C172")
      (value "600F110JT250XT")
      (footprint "C0805")
      (description "CAP CER 11PF 50V 5% NP0 0805")
      (fields (field (name "TOLERANCE") "0.05") (field (name "MANUFACTURER PART NUMBER") "C0805C110J5GACTU"))
      (libsource (lib "DACֹֹ_Sources") (part "b4654b650e69147ec39a6b967a45e02"))
    )
    (comp (ref "C173")
      (value "600F120JT250XT")
      (footprint "C0805")
      (description "CAP CER 11PF 50V 5% NP0 0805")
      (fields (field (name "TOLERANCE") "0.05") (field (name "MANUFACTURER PART NUMBER") "C0805C110J5GACTU"))
      (libsource (lib "DACֹֹ_Sources") (part "b4654b650e69147ec39a6b967a45e02"))
    )
    (comp (ref "C174")
      (value "600F110JT250XT")
      (footprint "C0805")
      (description "CAP CER 11PF 50V 5% NP0 0805")
      (fields (field (name "TOLERANCE") "0.05") (field (name "MANUFACTURER PART NUMBER") "C0805C110J5GACTU"))
      (libsource (lib "DACֹֹ_Sources") (part "b4654b650e69147ec39a6b967a45e02"))
    )
    (comp (ref "C175")
      (value "600F110JT250XT")
      (footprint "C0805")
      (description "CAP CER 11PF 50V 5% NP0 0805")
      (fields (field (name "TOLERANCE") "0.05") (field (name "MANUFACTURER PART NUMBER") "C0805C110J5GACTU"))
      (libsource (lib "DACֹֹ_Sources") (part "b4654b650e69147ec39a6b967a45e02"))
    )
    (comp (ref "C176")
      (value "600F120JT250XT")
      (footprint "C0805")
      (description "CAP CER 11PF 50V 5% NP0 0805")
      (fields (field (name "TOLERANCE") "0.05") (field (name "MANUFACTURER PART NUMBER") "C0805C110J5GACTU"))
      (libsource (lib "DACֹֹ_Sources") (part "b4654b650e69147ec39a6b967a45e02"))
    )
    (comp (ref "C177")
      (value "600F110JT250XT")
      (footprint "C0805")
      (description "CAP CER 11PF 50V 5% NP0 0805")
      (fields (field (name "TOLERANCE") "0.05") (field (name "MANUFACTURER PART NUMBER") "C0805C110J5GACTU"))
      (libsource (lib "DACֹֹ_Sources") (part "b4654b650e69147ec39a6b967a45e02"))
    )
    (comp (ref "C178")
      (value "GJM1555C1H3R3CB01D")
      (footprint "C0402")
      (description "Multi-Layer Ceramic Capacitor 3.3pF C0G  ±0.25pF 0402 Paper T/R")
      (fields (field (name "VOLTAGE") "50V"))
      (libsource (lib "DACֹֹ_Sources") (part "02cd4be3c70576c341d710602a673aa"))
    )
    (comp (ref "C179")
      (value "GJM1555C1H3R3CB01D")
      (footprint "C0402")
      (description "Multi-Layer Ceramic Capacitor 3.3pF C0G  ±0.25pF 0402 Paper T/R")
      (fields (field (name "VOLTAGE") "50V"))
      (libsource (lib "DACֹֹ_Sources") (part "02cd4be3c70576c341d710602a673aa"))
    )
    (comp (ref "C180")
      (value "GJM1555C1H3R3CB01D")
      (footprint "C0402")
      (description "Multi-Layer Ceramic Capacitor 3.3pF C0G  ±0.25pF 0402 Paper T/R")
      (fields (field (name "VOLTAGE") "50V"))
      (libsource (lib "DACֹֹ_Sources") (part "02cd4be3c70576c341d710602a673aa"))
    )
    (comp (ref "C181")
      (value "600F110JT250XT")
      (footprint "C0805")
      (description "CAP CER 11PF 50V 5% NP0 0805")
      (fields (field (name "TOLERANCE") "0.05") (field (name "MANUFACTURER PART NUMBER") "C0805C110J5GACTU"))
      (libsource (lib "DACֹֹ_Sources") (part "b4654b650e69147ec39a6b967a45e02"))
    )
    (comp (ref "C182")
      (value "600F120JT250XT")
      (footprint "C0805")
      (description "CAP CER 11PF 50V 5% NP0 0805")
      (fields (field (name "TOLERANCE") "0.05") (field (name "MANUFACTURER PART NUMBER") "C0805C110J5GACTU"))
      (libsource (lib "DACֹֹ_Sources") (part "b4654b650e69147ec39a6b967a45e02"))
    )
    (comp (ref "C183")
      (value "600F110JT250XT")
      (footprint "C0805")
      (description "CAP CER 11PF 50V 5% NP0 0805")
      (fields (field (name "TOLERANCE") "0.05") (field (name "MANUFACTURER PART NUMBER") "C0805C110J5GACTU"))
      (libsource (lib "DACֹֹ_Sources") (part "b4654b650e69147ec39a6b967a45e02"))
    )
    (comp (ref "C184")
      (value "600F110JT250XT")
      (footprint "C0805")
      (description "CAP CER 11PF 50V 5% NP0 0805")
      (fields (field (name "TOLERANCE") "0.05") (field (name "MANUFACTURER PART NUMBER") "C0805C110J5GACTU"))
      (libsource (lib "DACֹֹ_Sources") (part "b4654b650e69147ec39a6b967a45e02"))
    )
    (comp (ref "C185")
      (value "600F120JT250XT")
      (footprint "C0805")
      (description "CAP CER 11PF 50V 5% NP0 0805")
      (fields (field (name "TOLERANCE") "0.05") (field (name "MANUFACTURER PART NUMBER") "C0805C110J5GACTU"))
      (libsource (lib "DACֹֹ_Sources") (part "b4654b650e69147ec39a6b967a45e02"))
    )
    (comp (ref "C186")
      (value "600F110JT250XT")
      (footprint "C0805")
      (description "CAP CER 11PF 50V 5% NP0 0805")
      (fields (field (name "TOLERANCE") "0.05") (field (name "MANUFACTURER PART NUMBER") "C0805C110J5GACTU"))
      (libsource (lib "DACֹֹ_Sources") (part "b4654b650e69147ec39a6b967a45e02"))
    )
    (comp (ref "C187")
      (value "GJM1555C1H3R3CB01D")
      (footprint "C0402")
      (description "Multi-Layer Ceramic Capacitor 3.3pF C0G  ±0.25pF 0402 Paper T/R")
      (fields (field (name "VOLTAGE") "50V"))
      (libsource (lib "DACֹֹ_Sources") (part "02cd4be3c70576c341d710602a673aa"))
    )
    (comp (ref "C188")
      (value "GJM1555C1H3R3CB01D")
      (footprint "C0402")
      (description "Multi-Layer Ceramic Capacitor 3.3pF C0G  ±0.25pF 0402 Paper T/R")
      (fields (field (name "VOLTAGE") "50V"))
      (libsource (lib "DACֹֹ_Sources") (part "02cd4be3c70576c341d710602a673aa"))
    )
    (comp (ref "C189")
      (value "GJM1555C1H3R3CB01D")
      (footprint "C0402")
      (description "Multi-Layer Ceramic Capacitor 3.3pF C0G  ±0.25pF 0402 Paper T/R")
      (fields (field (name "VOLTAGE") "50V"))
      (libsource (lib "DACֹֹ_Sources") (part "02cd4be3c70576c341d710602a673aa"))
    )
    (comp (ref "C190")
      (value "600F110JT250XT")
      (footprint "C0805")
      (description "CAP CER 11PF 50V 5% NP0 0805")
      (fields (field (name "TOLERANCE") "0.05") (field (name "MANUFACTURER PART NUMBER") "C0805C110J5GACTU"))
      (libsource (lib "DACֹֹ_Sources") (part "b4654b650e69147ec39a6b967a45e02"))
    )
    (comp (ref "C191")
      (value "600F120JT250XT")
      (footprint "C0805")
      (description "CAP CER 11PF 50V 5% NP0 0805")
      (fields (field (name "TOLERANCE") "0.05") (field (name "MANUFACTURER PART NUMBER") "C0805C110J5GACTU"))
      (libsource (lib "DACֹֹ_Sources") (part "b4654b650e69147ec39a6b967a45e02"))
    )
    (comp (ref "C192")
      (value "600F110JT250XT")
      (footprint "C0805")
      (description "CAP CER 11PF 50V 5% NP0 0805")
      (fields (field (name "TOLERANCE") "0.05") (field (name "MANUFACTURER PART NUMBER") "C0805C110J5GACTU"))
      (libsource (lib "DACֹֹ_Sources") (part "b4654b650e69147ec39a6b967a45e02"))
    )
    (comp (ref "C193")
      (value "600F110JT250XT")
      (footprint "C0805")
      (description "CAP CER 11PF 50V 5% NP0 0805")
      (fields (field (name "TOLERANCE") "0.05") (field (name "MANUFACTURER PART NUMBER") "C0805C110J5GACTU"))
      (libsource (lib "DACֹֹ_Sources") (part "b4654b650e69147ec39a6b967a45e02"))
    )
    (comp (ref "C194")
      (value "600F120JT250XT")
      (footprint "C0805")
      (description "CAP CER 11PF 50V 5% NP0 0805")
      (fields (field (name "TOLERANCE") "0.05") (field (name "MANUFACTURER PART NUMBER") "C0805C110J5GACTU"))
      (libsource (lib "DACֹֹ_Sources") (part "b4654b650e69147ec39a6b967a45e02"))
    )
    (comp (ref "C195")
      (value "600F110JT250XT")
      (footprint "C0805")
      (description "CAP CER 11PF 50V 5% NP0 0805")
      (fields (field (name "TOLERANCE") "0.05") (field (name "MANUFACTURER PART NUMBER") "C0805C110J5GACTU"))
      (libsource (lib "DACֹֹ_Sources") (part "b4654b650e69147ec39a6b967a45e02"))
    )
    (comp (ref "C196")
      (value "GJM1555C1H3R3CB01D")
      (footprint "C0402")
      (description "Multi-Layer Ceramic Capacitor 3.3pF C0G  ±0.25pF 0402 Paper T/R")
      (fields (field (name "VOLTAGE") "50V"))
      (libsource (lib "DACֹֹ_Sources") (part "02cd4be3c70576c341d710602a673aa"))
    )
    (comp (ref "C197")
      (value "GJM1555C1H3R3CB01D")
      (footprint "C0402")
      (description "Multi-Layer Ceramic Capacitor 3.3pF C0G  ±0.25pF 0402 Paper T/R")
      (fields (field (name "VOLTAGE") "50V"))
      (libsource (lib "DACֹֹ_Sources") (part "02cd4be3c70576c341d710602a673aa"))
    )
    (comp (ref "C198")
      (value "GJM1555C1H3R3CB01D")
      (footprint "C0402")
      (description "Multi-Layer Ceramic Capacitor 3.3pF C0G  ±0.25pF 0402 Paper T/R")
      (fields (field (name "VOLTAGE") "50V"))
      (libsource (lib "DACֹֹ_Sources") (part "02cd4be3c70576c341d710602a673aa"))
    )
    (comp (ref "C199")
      (value "600F110JT250XT")
      (footprint "C0805")
      (description "CAP CER 11PF 50V 5% NP0 0805")
      (fields (field (name "TOLERANCE") "0.05") (field (name "MANUFACTURER PART NUMBER") "C0805C110J5GACTU"))
      (libsource (lib "DACֹֹ_Sources") (part "b4654b650e69147ec39a6b967a45e02"))
    )
    (comp (ref "C200")
      (value "600F120JT250XT")
      (footprint "C0805")
      (description "CAP CER 11PF 50V 5% NP0 0805")
      (fields (field (name "TOLERANCE") "0.05") (field (name "MANUFACTURER PART NUMBER") "C0805C110J5GACTU"))
      (libsource (lib "DACֹֹ_Sources") (part "b4654b650e69147ec39a6b967a45e02"))
    )
    (comp (ref "C201")
      (value "600F110JT250XT")
      (footprint "C0805")
      (description "CAP CER 11PF 50V 5% NP0 0805")
      (fields (field (name "TOLERANCE") "0.05") (field (name "MANUFACTURER PART NUMBER") "C0805C110J5GACTU"))
      (libsource (lib "DACֹֹ_Sources") (part "b4654b650e69147ec39a6b967a45e02"))
    )
    (comp (ref "C202")
      (value "LMK063BJ224MP-F")
      (footprint "C0201")
      (description "None")
      (fields (field (name "VOLTAGE") "10V") (field (name "TOLERANCE") "20%"))
      (libsource (lib "DACֹֹ_Sources") (part "b4654b650e69147ec39a6b967a45e02"))
    )
    (comp (ref "C203")
      (value "LMK063BJ224MP-F")
      (footprint "C0201")
      (description "None")
      (fields (field (name "VOLTAGE") "10V") (field (name "TOLERANCE") "20%"))
      (libsource (lib "DACֹֹ_Sources") (part "b4654b650e69147ec39a6b967a45e02"))
    )
    (comp (ref "C204")
      (value "LMK063BJ224MP-F")
      (footprint "C0201")
      (description "None")
      (fields (field (name "VOLTAGE") "10V") (field (name "TOLERANCE") "20%"))
      (libsource (lib "DACֹֹ_Sources") (part "b4654b650e69147ec39a6b967a45e02"))
    )
    (comp (ref "C205")
      (value "LMK107BJ106MALTD")
      (footprint "C0603")
      (description "CAP CER 10UF 10V X5R 0603")
      (fields (field (name "TOLERANCE") "20%"))
      (libsource (lib "DACֹֹ_Sources") (part "b4654b650e69147ec39a6b967a45e02"))
    )
    (comp (ref "C206")
      (value "LMK063BJ224MP-F")
      (footprint "C0201")
      (description "None")
      (fields (field (name "VOLTAGE") "10V") (field (name "TOLERANCE") "20%"))
      (libsource (lib "DACֹֹ_Sources") (part "b4654b650e69147ec39a6b967a45e02"))
    )
    (comp (ref "C207")
      (value "LMK063BJ224MP-F")
      (footprint "C0201")
      (description "None")
      (fields (field (name "VOLTAGE") "10V") (field (name "TOLERANCE") "20%"))
      (libsource (lib "DACֹֹ_Sources") (part "b4654b650e69147ec39a6b967a45e02"))
    )
    (comp (ref "C208")
      (value "LMK063BJ224MP-F")
      (footprint "C0201")
      (description "None")
      (fields (field (name "VOLTAGE") "10V") (field (name "TOLERANCE") "20%"))
      (libsource (lib "DACֹֹ_Sources") (part "b4654b650e69147ec39a6b967a45e02"))
    )
    (comp (ref "C209")
      (value "LMK107BJ106MALTD")
      (footprint "C0603")
      (description "CAP CER 10UF 10V X5R 0603")
      (fields (field (name "TOLERANCE") "20%"))
      (libsource (lib "DACֹֹ_Sources") (part "b4654b650e69147ec39a6b967a45e02"))
    )
    (comp (ref "C210")
      (value "C1005X7R1E102K050BA")
      (footprint "C0402")
      (description "Multilayer Ceramic Capacitors 1nF ±10% 25V X7R SMD 0402")
      (fields (field (name "TOLERANCE") "10%"))
      (libsource (lib "DACֹֹ_Sources") (part "b4654b650e69147ec39a6b967a45e02"))
    )
    (comp (ref "C211")
      (value "C1005X7R1C104K050BC")
      (footprint "C0402")
      (description "Multilayer Ceramic Capacitors 100nF ±10% 16V X7R SMD 0402")
      (fields (field (name "VOLTAGE") "16V") (field (name "TOLERANCE") "10%"))
      (libsource (lib "DACֹֹ_Sources") (part "b4654b650e69147ec39a6b967a45e02"))
    )
    (comp (ref "C212")
      (value "C1005X7R1C104K050BC")
      (footprint "C0402")
      (description "Multilayer Ceramic Capacitors 100nF ±10% 16V X7R SMD 0402")
      (fields (field (name "VOLTAGE") "16V") (field (name "TOLERANCE") "10%"))
      (libsource (lib "DACֹֹ_Sources") (part "b4654b650e69147ec39a6b967a45e02"))
    )
    (comp (ref "C213")
      (value "C1005X7R1E102K050BA")
      (footprint "C0402")
      (description "Multilayer Ceramic Capacitors 1nF ±10% 25V X7R SMD 0402")
      (fields (field (name "TOLERANCE") "10%"))
      (libsource (lib "DACֹֹ_Sources") (part "b4654b650e69147ec39a6b967a45e02"))
    )
    (comp (ref "C214")
      (value "C1005X7R1E102K050BA")
      (footprint "C0402")
      (description "Multilayer Ceramic Capacitors 1nF ±10% 25V X7R SMD 0402")
      (fields (field (name "TOLERANCE") "10%"))
      (libsource (lib "DACֹֹ_Sources") (part "b4654b650e69147ec39a6b967a45e02"))
    )
    (comp (ref "C215")
      (value "C1005X7R1C104K050BC")
      (footprint "C0402")
      (description "Multilayer Ceramic Capacitors 100nF ±10% 16V X7R SMD 0402")
      (fields (field (name "VOLTAGE") "16V") (field (name "TOLERANCE") "10%"))
      (libsource (lib "DACֹֹ_Sources") (part "b4654b650e69147ec39a6b967a45e02"))
    )
    (comp (ref "C216")
      (value "C1005X7R1C104K050BC")
      (footprint "C0402")
      (description "Multilayer Ceramic Capacitors 100nF ±10% 16V X7R SMD 0402")
      (fields (field (name "VOLTAGE") "16V") (field (name "TOLERANCE") "10%"))
      (libsource (lib "DACֹֹ_Sources") (part "b4654b650e69147ec39a6b967a45e02"))
    )
    (comp (ref "C217")
      (value "C1005X7R1E102K050BA")
      (footprint "C0402")
      (description "Multilayer Ceramic Capacitors 1nF ±10% 25V X7R SMD 0402")
      (fields (field (name "TOLERANCE") "10%"))
      (libsource (lib "DACֹֹ_Sources") (part "b4654b650e69147ec39a6b967a45e02"))
    )
    (comp (ref "C218")
      (value "LMK063BJ104KP-F")
      (footprint "C0201")
      (description "None")
      (fields (field (name "TOLERANCE") "10%"))
      (libsource (lib "DACֹֹ_Sources") (part "b4654b650e69147ec39a6b967a45e02"))
    )
    (comp (ref "C219")
      (value "LMK063BJ224MP-F")
      (footprint "C0201")
      (description "None")
      (fields (field (name "VOLTAGE") "10V") (field (name "TOLERANCE") "20%"))
      (libsource (lib "DACֹֹ_Sources") (part "b4654b650e69147ec39a6b967a45e02"))
    )
    (comp (ref "C220")
      (value "LMK063BJ224MP-F")
      (footprint "C0201")
      (description "None")
      (fields (field (name "VOLTAGE") "10V") (field (name "TOLERANCE") "20%"))
      (libsource (lib "DACֹֹ_Sources") (part "b4654b650e69147ec39a6b967a45e02"))
    )
    (comp (ref "C221")
      (value "LMK063BJ224MP-F")
      (footprint "C0201")
      (description "None")
      (fields (field (name "VOLTAGE") "10V") (field (name "TOLERANCE") "20%"))
      (libsource (lib "DACֹֹ_Sources") (part "b4654b650e69147ec39a6b967a45e02"))
    )
    (comp (ref "C222")
      (value "LMK063BJ224MP-F")
      (footprint "C0201")
      (description "None")
      (fields (field (name "VOLTAGE") "10V") (field (name "TOLERANCE") "20%"))
      (libsource (lib "DACֹֹ_Sources") (part "b4654b650e69147ec39a6b967a45e02"))
    )
    (comp (ref "C223")
      (value "LMK063BJ224MP-F")
      (footprint "C0201")
      (description "None")
      (fields (field (name "VOLTAGE") "10V") (field (name "TOLERANCE") "20%"))
      (libsource (lib "DACֹֹ_Sources") (part "b4654b650e69147ec39a6b967a45e02"))
    )
    (comp (ref "C224")
      (value "LMK063BJ224MP-F")
      (footprint "C0201")
      (description "None")
      (fields (field (name "VOLTAGE") "10V") (field (name "TOLERANCE") "20%"))
      (libsource (lib "DACֹֹ_Sources") (part "b4654b650e69147ec39a6b967a45e02"))
    )
    (comp (ref "C225")
      (value "LMK063BJ224MP-F")
      (footprint "C0201")
      (description "None")
      (fields (field (name "VOLTAGE") "10V") (field (name "TOLERANCE") "20%"))
      (libsource (lib "DACֹֹ_Sources") (part "b4654b650e69147ec39a6b967a45e02"))
    )
    (comp (ref "C226")
      (value "LMK107BJ106MALTD")
      (footprint "C0603")
      (description "CAP CER 10UF 10V X5R 0603")
      (fields (field (name "TOLERANCE") "20%"))
      (libsource (lib "DACֹֹ_Sources") (part "b4654b650e69147ec39a6b967a45e02"))
    )
    (comp (ref "C227")
      (value "LMK063BJ224MP-F")
      (footprint "C0201")
      (description "None")
      (fields (field (name "VOLTAGE") "10V") (field (name "TOLERANCE") "20%"))
      (libsource (lib "DACֹֹ_Sources") (part "b4654b650e69147ec39a6b967a45e02"))
    )
    (comp (ref "C228")
      (value "LMK063BJ224MP-F")
      (footprint "C0201")
      (description "None")
      (fields (field (name "VOLTAGE") "10V") (field (name "TOLERANCE") "20%"))
      (libsource (lib "DACֹֹ_Sources") (part "b4654b650e69147ec39a6b967a45e02"))
    )
    (comp (ref "C229")
      (value "LMK063BJ224MP-F")
      (footprint "C0201")
      (description "None")
      (fields (field (name "VOLTAGE") "10V") (field (name "TOLERANCE") "20%"))
      (libsource (lib "DACֹֹ_Sources") (part "b4654b650e69147ec39a6b967a45e02"))
    )
    (comp (ref "C230")
      (value "LMK063BJ224MP-F")
      (footprint "C0201")
      (description "None")
      (fields (field (name "VOLTAGE") "10V") (field (name "TOLERANCE") "20%"))
      (libsource (lib "DACֹֹ_Sources") (part "b4654b650e69147ec39a6b967a45e02"))
    )
    (comp (ref "C231")
      (value "LMK107BJ106MALTD")
      (footprint "C0603")
      (description "CAP CER 10UF 10V X5R 0603")
      (fields (field (name "TOLERANCE") "20%"))
      (libsource (lib "DACֹֹ_Sources") (part "b4654b650e69147ec39a6b967a45e02"))
    )
    (comp (ref "C232")
      (value "LMK063BJ224MP-F")
      (footprint "C0201")
      (description "None")
      (fields (field (name "VOLTAGE") "10V") (field (name "TOLERANCE") "20%"))
      (libsource (lib "DACֹֹ_Sources") (part "b4654b650e69147ec39a6b967a45e02"))
    )
    (comp (ref "C233")
      (value "LMK063BJ224MP-F")
      (footprint "C0201")
      (description "None")
      (fields (field (name "VOLTAGE") "10V") (field (name "TOLERANCE") "20%"))
      (libsource (lib "DACֹֹ_Sources") (part "b4654b650e69147ec39a6b967a45e02"))
    )
    (comp (ref "C234")
      (value "LMK063BJ224MP-F")
      (footprint "C0201")
      (description "None")
      (fields (field (name "VOLTAGE") "10V") (field (name "TOLERANCE") "20%"))
      (libsource (lib "DACֹֹ_Sources") (part "b4654b650e69147ec39a6b967a45e02"))
    )
    (comp (ref "C235")
      (value "LMK107BJ106MALTD")
      (footprint "C0603")
      (description "CAP CER 10UF 10V X5R 0603")
      (fields (field (name "TOLERANCE") "20%"))
      (libsource (lib "DACֹֹ_Sources") (part "b4654b650e69147ec39a6b967a45e02"))
    )
    (comp (ref "C236")
      (value "LMK063BJ224MP-F")
      (footprint "C0201")
      (description "None")
      (fields (field (name "VOLTAGE") "10V") (field (name "TOLERANCE") "20%"))
      (libsource (lib "DACֹֹ_Sources") (part "b4654b650e69147ec39a6b967a45e02"))
    )
    (comp (ref "C237")
      (value "LMK063BJ224MP-F")
      (footprint "C0201")
      (description "None")
      (fields (field (name "VOLTAGE") "10V") (field (name "TOLERANCE") "20%"))
      (libsource (lib "DACֹֹ_Sources") (part "b4654b650e69147ec39a6b967a45e02"))
    )
    (comp (ref "C238")
      (value "LMK107BJ106MALTD")
      (footprint "C0603")
      (description "CAP CER 10UF 10V X5R 0603")
      (fields (field (name "TOLERANCE") "20%"))
      (libsource (lib "DACֹֹ_Sources") (part "b4654b650e69147ec39a6b967a45e02"))
    )
    (comp (ref "C239")
      (value "LMK063BJ104KP-F")
      (footprint "C0201")
      (description "None")
      (fields (field (name "TOLERANCE") "10%"))
      (libsource (lib "DACֹֹ_Sources") (part "b4654b650e69147ec39a6b967a45e02"))
    )
    (comp (ref "C240")
      (value "LMK063BJ224MP-F")
      (footprint "C0201")
      (description "None")
      (fields (field (name "VOLTAGE") "10V") (field (name "TOLERANCE") "20%"))
      (libsource (lib "DACֹֹ_Sources") (part "b4654b650e69147ec39a6b967a45e02"))
    )
    (comp (ref "C241")
      (value "LMK063BJ224MP-F")
      (footprint "C0201")
      (description "None")
      (fields (field (name "VOLTAGE") "10V") (field (name "TOLERANCE") "20%"))
      (libsource (lib "DACֹֹ_Sources") (part "b4654b650e69147ec39a6b967a45e02"))
    )
    (comp (ref "C242")
      (value "LMK063BJ224MP-F")
      (footprint "C0201")
      (description "None")
      (fields (field (name "VOLTAGE") "10V") (field (name "TOLERANCE") "20%"))
      (libsource (lib "DACֹֹ_Sources") (part "b4654b650e69147ec39a6b967a45e02"))
    )
    (comp (ref "C243")
      (value "LMK063BJ224MP-F")
      (footprint "C0201")
      (description "None")
      (fields (field (name "VOLTAGE") "10V") (field (name "TOLERANCE") "20%"))
      (libsource (lib "DACֹֹ_Sources") (part "b4654b650e69147ec39a6b967a45e02"))
    )
    (comp (ref "C244")
      (value "LMK063BJ224MP-F")
      (footprint "C0201")
      (description "None")
      (fields (field (name "VOLTAGE") "10V") (field (name "TOLERANCE") "20%"))
      (libsource (lib "DACֹֹ_Sources") (part "b4654b650e69147ec39a6b967a45e02"))
    )
    (comp (ref "C245")
      (value "LMK063BJ224MP-F")
      (footprint "C0201")
      (description "None")
      (fields (field (name "VOLTAGE") "10V") (field (name "TOLERANCE") "20%"))
      (libsource (lib "DACֹֹ_Sources") (part "b4654b650e69147ec39a6b967a45e02"))
    )
    (comp (ref "C246")
      (value "LMK063BJ224MP-F")
      (footprint "C0201")
      (description "None")
      (fields (field (name "VOLTAGE") "10V") (field (name "TOLERANCE") "20%"))
      (libsource (lib "DACֹֹ_Sources") (part "b4654b650e69147ec39a6b967a45e02"))
    )
    (comp (ref "C247")
      (value "LMK107BJ106MALTD")
      (footprint "C0603")
      (description "CAP CER 10UF 10V X5R 0603")
      (fields (field (name "TOLERANCE") "20%"))
      (libsource (lib "DACֹֹ_Sources") (part "b4654b650e69147ec39a6b967a45e02"))
    )
    (comp (ref "C248")
      (value "LMK063BJ224MP-F")
      (footprint "C0201")
      (description "None")
      (fields (field (name "VOLTAGE") "10V") (field (name "TOLERANCE") "20%"))
      (libsource (lib "DACֹֹ_Sources") (part "b4654b650e69147ec39a6b967a45e02"))
    )
    (comp (ref "C249")
      (value "LMK063BJ224MP-F")
      (footprint "C0201")
      (description "None")
      (fields (field (name "VOLTAGE") "10V") (field (name "TOLERANCE") "20%"))
      (libsource (lib "DACֹֹ_Sources") (part "b4654b650e69147ec39a6b967a45e02"))
    )
    (comp (ref "C250")
      (value "LMK063BJ224MP-F")
      (footprint "C0201")
      (description "None")
      (fields (field (name "VOLTAGE") "10V") (field (name "TOLERANCE") "20%"))
      (libsource (lib "DACֹֹ_Sources") (part "b4654b650e69147ec39a6b967a45e02"))
    )
    (comp (ref "C251")
      (value "LMK063BJ224MP-F")
      (footprint "C0201")
      (description "None")
      (fields (field (name "VOLTAGE") "10V") (field (name "TOLERANCE") "20%"))
      (libsource (lib "DACֹֹ_Sources") (part "b4654b650e69147ec39a6b967a45e02"))
    )
    (comp (ref "C252")
      (value "LMK107BJ106MALTD")
      (footprint "C0603")
      (description "CAP CER 10UF 10V X5R 0603")
      (fields (field (name "TOLERANCE") "20%"))
      (libsource (lib "DACֹֹ_Sources") (part "b4654b650e69147ec39a6b967a45e02"))
    )
    (comp (ref "C253")
      (value "LMK063BJ224MP-F")
      (footprint "C0201")
      (description "None")
      (fields (field (name "VOLTAGE") "10V") (field (name "TOLERANCE") "20%"))
      (libsource (lib "DACֹֹ_Sources") (part "b4654b650e69147ec39a6b967a45e02"))
    )
    (comp (ref "C254")
      (value "LMK063BJ224MP-F")
      (footprint "C0201")
      (description "None")
      (fields (field (name "VOLTAGE") "10V") (field (name "TOLERANCE") "20%"))
      (libsource (lib "DACֹֹ_Sources") (part "b4654b650e69147ec39a6b967a45e02"))
    )
    (comp (ref "C255")
      (value "LMK063BJ224MP-F")
      (footprint "C0201")
      (description "None")
      (fields (field (name "VOLTAGE") "10V") (field (name "TOLERANCE") "20%"))
      (libsource (lib "DACֹֹ_Sources") (part "b4654b650e69147ec39a6b967a45e02"))
    )
    (comp (ref "C256")
      (value "LMK107BJ106MALTD")
      (footprint "C0603")
      (description "CAP CER 10UF 10V X5R 0603")
      (fields (field (name "TOLERANCE") "20%"))
      (libsource (lib "DACֹֹ_Sources") (part "b4654b650e69147ec39a6b967a45e02"))
    )
    (comp (ref "C257")
      (value "LMK063BJ224MP-F")
      (footprint "C0201")
      (description "None")
      (fields (field (name "VOLTAGE") "10V") (field (name "TOLERANCE") "20%"))
      (libsource (lib "DACֹֹ_Sources") (part "b4654b650e69147ec39a6b967a45e02"))
    )
    (comp (ref "C258")
      (value "LMK063BJ224MP-F")
      (footprint "C0201")
      (description "None")
      (fields (field (name "VOLTAGE") "10V") (field (name "TOLERANCE") "20%"))
      (libsource (lib "DACֹֹ_Sources") (part "b4654b650e69147ec39a6b967a45e02"))
    )
    (comp (ref "C259")
      (value "LMK107BJ106MALTD")
      (footprint "C0603")
      (description "CAP CER 10UF 10V X5R 0603")
      (fields (field (name "TOLERANCE") "20%"))
      (libsource (lib "DACֹֹ_Sources") (part "b4654b650e69147ec39a6b967a45e02"))
    )
    (comp (ref "C260")
      (value "C1005X7R1C104K050BC")
      (footprint "C0402")
      (description "Multilayer Ceramic Capacitors 100nF ±10% 16V X7R SMD 0402")
      (fields (field (name "VOLTAGE") "16V") (field (name "TOLERANCE") "10%"))
      (libsource (lib "Simulation Generic Components") (part "b4654b650e69147ec39a6b967a45e02"))
    )
    (comp (ref "C261")
      (value "C1206C150J5GACTU")
      (footprint "C1206")
      (description "1206 C 15pF Ceramic Multilayer Capacitor; 50 VDC; +125degC; C0G Dielec; +/-5%")
      (fields (field (name "TOLERANCE") "0.05") (field (name "MANUFACTURER") "KEMET"))
      (libsource (lib "Simulation Generic Components") (part "b4654b650e69147ec39a6b967a45e02"))
    )
    (comp (ref "C263")
      (value "C1005X7R1C104K050BC")
      (footprint "C0402")
      (description "Multilayer Ceramic Capacitors 100nF ±10% 16V X7R SMD 0402")
      (fields (field (name "VOLTAGE") "16V") (field (name "TOLERANCE") "10%"))
      (libsource (lib "Simulation Generic Components") (part "b4654b650e69147ec39a6b967a45e02"))
    )
    (comp (ref "C264")
      (value "C1005X7R1C104K050BC")
      (footprint "C0402")
      (description "Multilayer Ceramic Capacitors 100nF ±10% 16V X7R SMD 0402")
      (fields (field (name "VOLTAGE") "16V") (field (name "TOLERANCE") "10%"))
      (libsource (lib "Simulation Generic Components") (part "b4654b650e69147ec39a6b967a45e02"))
    )
    (comp (ref "C277")
      (value "C1005X7R1E103K050BB")
      (footprint "C0402")
      (description "Multilayer Ceramic Capacitors 10nF ±10% 25V X7R SMD 0402")
      (fields (field (name "TOLERANCE") "10%") (field (name "VOLTAGE") "25V"))
      (libsource (lib "DACֹֹ_Sources") (part "b4654b650e69147ec39a6b967a45e02"))
    )
    (comp (ref "C278")
      (value "C1005X7R1E103K050BB")
      (footprint "C0402")
      (description "Multilayer Ceramic Capacitors 10nF ±10% 25V X7R SMD 0402")
      (fields (field (name "TOLERANCE") "10%") (field (name "VOLTAGE") "25V"))
      (libsource (lib "DACֹֹ_Sources") (part "b4654b650e69147ec39a6b967a45e02"))
    )
    (comp (ref "C279")
      (value "C1005X7R1E103K050BB")
      (footprint "C0402")
      (description "Multilayer Ceramic Capacitors 10nF ±10% 25V X7R SMD 0402")
      (fields (field (name "TOLERANCE") "10%") (field (name "VOLTAGE") "25V"))
      (libsource (lib "DACֹֹ_Sources") (part "b4654b650e69147ec39a6b967a45e02"))
    )
    (comp (ref "C280")
      (value "CGB3B1X5R1A475K055AC")
      (footprint "C0603")
      (description "CAP CER 4.7UF 10V X5R 0603")
      (fields (field (name "TOLERANCE") "10%"))
      (libsource (lib "DACֹֹ_Sources") (part "b4654b650e69147ec39a6b967a45e02"))
    )
    (comp (ref "C283")
      (value "CC0603KRX7R9BB103")
      (footprint "C0603")
      (description "CAP CER 10000PF 50V X7R 0603")
      (fields (field (name "TOLERANCE") "0.1") (field (name "MANUFACTURER") "YAGEO"))
      (libsource (lib "DACֹֹ_Sources") (part "11868f565c42a9108669ba33697ecf6"))
    )
    (comp (ref "C284")
      (value "CC0603KRX7R9BB103")
      (footprint "C0603")
      (description "CAP CER 10000PF 50V X7R 0603")
      (fields (field (name "TOLERANCE") "0.1") (field (name "MANUFACTURER") "YAGEO"))
      (libsource (lib "DACֹֹ_Sources") (part "11868f565c42a9108669ba33697ecf6"))
    )
    (comp (ref "C285")
      (value "C1005X7R1E103K050BB")
      (footprint "C0402")
      (description "Multilayer Ceramic Capacitors 10nF ±10% 25V X7R SMD 0402")
      (fields (field (name "TOLERANCE") "10%") (field (name "VOLTAGE") "25V"))
      (libsource (lib "DACֹֹ_Sources") (part "b4654b650e69147ec39a6b967a45e02"))
    )
    (comp (ref "C286")
      (value "C1005X7R1E103K050BB")
      (footprint "C0402")
      (description "Multilayer Ceramic Capacitors 10nF ±10% 25V X7R SMD 0402")
      (fields (field (name "TOLERANCE") "10%") (field (name "VOLTAGE") "25V"))
      (libsource (lib "DACֹֹ_Sources") (part "b4654b650e69147ec39a6b967a45e02"))
    )
    (comp (ref "C287")
      (value "C1005X7R1E103K050BB")
      (footprint "C0402")
      (description "Multilayer Ceramic Capacitors 10nF ±10% 25V X7R SMD 0402")
      (fields (field (name "TOLERANCE") "10%") (field (name "VOLTAGE") "25V"))
      (libsource (lib "DACֹֹ_Sources") (part "b4654b650e69147ec39a6b967a45e02"))
    )
    (comp (ref "C288")
      (value "CGB3B1X5R1A475K055AC")
      (footprint "C0603")
      (description "CAP CER 4.7UF 10V X5R 0603")
      (fields (field (name "TOLERANCE") "10%"))
      (libsource (lib "DACֹֹ_Sources") (part "b4654b650e69147ec39a6b967a45e02"))
    )
    (comp (ref "C316")
      (value "C1005X7R1E103K050BB")
      (footprint "C0402")
      (description "Multilayer Ceramic Capacitors 10nF ±10% 25V X7R SMD 0402")
      (fields (field (name "TOLERANCE") "10%") (field (name "VOLTAGE") "25V"))
      (libsource (lib "DACֹֹ_Sources") (part "b4654b650e69147ec39a6b967a45e02"))
    )
    (comp (ref "C317")
      (value "C1005X7R1E103K050BB")
      (footprint "C0402")
      (description "Multilayer Ceramic Capacitors 10nF ±10% 25V X7R SMD 0402")
      (fields (field (name "TOLERANCE") "10%") (field (name "VOLTAGE") "25V"))
      (libsource (lib "DACֹֹ_Sources") (part "b4654b650e69147ec39a6b967a45e02"))
    )
    (comp (ref "C318")
      (value "C1005X7R1E103K050BB")
      (footprint "C0402")
      (description "Multilayer Ceramic Capacitors 10nF ±10% 25V X7R SMD 0402")
      (fields (field (name "TOLERANCE") "10%") (field (name "VOLTAGE") "25V"))
      (libsource (lib "DACֹֹ_Sources") (part "b4654b650e69147ec39a6b967a45e02"))
    )
    (comp (ref "C319")
      (value "C1005X7R1E103K050BB")
      (footprint "C0402")
      (description "Multilayer Ceramic Capacitors 10nF ±10% 25V X7R SMD 0402")
      (fields (field (name "TOLERANCE") "10%") (field (name "VOLTAGE") "25V"))
      (libsource (lib "DACֹֹ_Sources") (part "b4654b650e69147ec39a6b967a45e02"))
    )
    (comp (ref "C320")
      (value "C1005X7R1E103K050BB")
      (footprint "C0402")
      (description "Multilayer Ceramic Capacitors 10nF ±10% 25V X7R SMD 0402")
      (fields (field (name "TOLERANCE") "10%") (field (name "VOLTAGE") "25V"))
      (libsource (lib "DACֹֹ_Sources") (part "b4654b650e69147ec39a6b967a45e02"))
    )
    (comp (ref "C321")
      (value "C1005X7R1E103K050BB")
      (footprint "C0402")
      (description "Multilayer Ceramic Capacitors 10nF ±10% 25V X7R SMD 0402")
      (fields (field (name "TOLERANCE") "10%") (field (name "VOLTAGE") "25V"))
      (libsource (lib "DACֹֹ_Sources") (part "b4654b650e69147ec39a6b967a45e02"))
    )
    (comp (ref "C322")
      (value "C1005X7R1E103K050BB")
      (footprint "C0402")
      (description "Multilayer Ceramic Capacitors 10nF ±10% 25V X7R SMD 0402")
      (fields (field (name "TOLERANCE") "10%") (field (name "VOLTAGE") "25V"))
      (libsource (lib "DACֹֹ_Sources") (part "b4654b650e69147ec39a6b967a45e02"))
    )
    (comp (ref "C323")
      (value "C1005X7R1E103K050BB")
      (footprint "C0402")
      (description "Multilayer Ceramic Capacitors 10nF ±10% 25V X7R SMD 0402")
      (fields (field (name "TOLERANCE") "10%") (field (name "VOLTAGE") "25V"))
      (libsource (lib "DACֹֹ_Sources") (part "b4654b650e69147ec39a6b967a45e02"))
    )
    (comp (ref "FB11")
      (value "BLM18HE152SN1D")
      (footprint "BLM18")
      (description "Chip Ferrite Bead, 0603, 1500Ω @ 100MHz, 0.5Ω, 25%, 500mA")
      (fields (field (name "TOLERANCE") "25%"))
      (libsource (lib "DACֹֹ_Sources") (part "5f30dd21d616792df468990f7003faa"))
    )
    (comp (ref "FB17")
      (value "BLM41PG102SN1L")
      (footprint "BLM41")
      (description "Ferrite Bead, 1806, 1000Ω @ 100MHz, 25%, 0.09Ω, 1.5A")
      (fields (field (name "TOLERANCE") "25%"))
      (libsource (lib "DACֹֹ_Sources") (part "5f30dd21d616792df468990f7003faa"))
    )
    (comp (ref "FB18")
      (value "BLM18HE152SN1D")
      (footprint "BLM41")
      (description "Chip Ferrite Bead, 0603, 1500Ω @ 100MHz, 0.5Ω, 25%, 500mA")
      (fields (field (name "TOLERANCE") "25%"))
      (libsource (lib "DACֹֹ_Sources") (part "5f30dd21d616792df468990f7003faa"))
    )
    (comp (ref "FB19")
      (value "BLM41PG102SN1L")
      (footprint "BLM41")
      (description "Ferrite Bead, 1806, 1000Ω @ 100MHz, 25%, 0.09Ω, 1.5A")
      (fields (field (name "TOLERANCE") "25%"))
      (libsource (lib "DACֹֹ_Sources") (part "5f30dd21d616792df468990f7003faa"))
    )
    (comp (ref "FB22")
      (value "BLM15PD121SN1D")
      (footprint "BLM15")
      (description "Chip Ferrite Bead, 0402, 120Ω @ 100MHz, 0.09Ω, 25%, 1.3A")
      (fields (field (name "TOLERANCE") "25%"))
      (libsource (lib "DACֹֹ_Sources") (part "5f30dd21d616792df468990f7003faa"))
    )
    (comp (ref "FB23")
      (value "BLM15PD121SN1D")
      (footprint "BLM15")
      (description "Chip Ferrite Bead, 0402, 120Ω @ 100MHz, 0.09Ω, 25%, 1.3A")
      (fields (field (name "TOLERANCE") "25%"))
      (libsource (lib "DACֹֹ_Sources") (part "5f30dd21d616792df468990f7003faa"))
    )
    (comp (ref "J1")
      (value "61083-104400LF")
      (footprint "AMPHENOL_61083-104400LF")
      (description "Conn Fine Pitch Connector PL 100 POS 0.8mm Solder ST Top Entry SMD BergstakÂ® Tube")
      (fields (field (name "MF") "Amphenol"))
      (libsource (lib "DACֹֹ_Sources") (part "61083-104400LF"))
    )
    (comp (ref "J2")
      (value "61083-104400LF")
      (footprint "AMPHENOL_61083-104400LF")
      (description "Conn Fine Pitch Connector PL 100 POS 0.8mm Solder ST Top Entry SMD BergstakÂ® Tube")
      (fields (field (name "MF") "Amphenol"))
      (libsource (lib "DACֹֹ_Sources") (part "61083-104400LF"))
    )
    (comp (ref "J4")
      (value "731000114")
      (footprint "MOLX-731000114_V")
      (description "SMA Right-Angle PCB Jack Receptacle, Brass Body, Gold Plated, 50 Ohm, 5-Pin THD, RoHS, Tray")
      (fields (field (name "MANUFACTURER") "Molex"))
      (libsource (lib "DACֹֹ_Sources") (part "CN-S-4F-RF5"))
    )
    (comp (ref "J8")
      (value "731000114")
      (footprint "MOLX-731000114_V")
      (description "SMA Right-Angle PCB Jack Receptacle, Brass Body, Gold Plated, 50 Ohm, 5-Pin THD, RoHS, Tray")
      (fields (field (name "MANUFACTURER") "Molex"))
      (libsource (lib "DACֹֹ_Sources") (part "CN-S-4F-RF5"))
    )
    (comp (ref "J9")
      (value "731000114")
      (footprint "MOLX-731000114_V")
      (description "SMA Right-Angle PCB Jack Receptacle, Brass Body, Gold Plated, 50 Ohm, 5-Pin THD, RoHS, Tray")
      (fields (field (name "MANUFACTURER") "Molex"))
      (libsource (lib "DACֹֹ_Sources") (part "CN-S-4F-RF5"))
    )
    (comp (ref "J10")
      (value "731000114")
      (footprint "MOLX-731000114_V")
      (description "SMA Right-Angle PCB Jack Receptacle, Brass Body, Gold Plated, 50 Ohm, 5-Pin THD, RoHS, Tray")
      (fields (field (name "MANUFACTURER") "Molex"))
      (libsource (lib "DACֹֹ_Sources") (part "CN-S-4F-RF5"))
    )
    (comp (ref "J11")
      (value "731000114")
      (footprint "MOLX-731000114_V")
      (description "SMA Right-Angle PCB Jack Receptacle, Brass Body, Gold Plated, 50 Ohm, 5-Pin THD, RoHS, Tray")
      (fields (field (name "MANUFACTURER") "Molex"))
      (libsource (lib "DACֹֹ_Sources") (part "CN-S-4F-RF5"))
    )
    (comp (ref "J12")
      (value "731000114")
      (footprint "MOLX-731000114_V")
      (description "SMA Right-Angle PCB Jack Receptacle, Brass Body, Gold Plated, 50 Ohm, 5-Pin THD, RoHS, Tray")
      (fields (field (name "MANUFACTURER") "Molex"))
      (libsource (lib "DACֹֹ_Sources") (part "CN-S-4F-RF5"))
    )
    (comp (ref "J13")
      (value "731000114")
      (footprint "MOLX-731000114_V")
      (description "SMA Right-Angle PCB Jack Receptacle, Brass Body, Gold Plated, 50 Ohm, 5-Pin THD, RoHS, Tray")
      (fields (field (name "MANUFACTURER") "Molex"))
      (libsource (lib "DACֹֹ_Sources") (part "CN-S-4F-RF5"))
    )
    (comp (ref "J14")
      (value "731000114")
      (footprint "MOLX-731000114_V")
      (description "SMA Right-Angle PCB Jack Receptacle, Brass Body, Gold Plated, 50 Ohm, 5-Pin THD, RoHS, Tray")
      (fields (field (name "MANUFACTURER") "Molex"))
      (libsource (lib "DACֹֹ_Sources") (part "CN-S-4F-RF5"))
    )
    (comp (ref "J15")
      (value "731000114")
      (footprint "MOLX-731000114_V")
      (description "SMA Right-Angle PCB Jack Receptacle, Brass Body, Gold Plated, 50 Ohm, 5-Pin THD, RoHS, Tray")
      (fields (field (name "MANUFACTURER") "Molex"))
      (libsource (lib "DACֹֹ_Sources") (part "CN-S-4F-RF5"))
    )
    (comp (ref "J16")
      (value "731000114")
      (footprint "MOLX-731000114_V")
      (description "SMA Right-Angle PCB Jack Receptacle, Brass Body, Gold Plated, 50 Ohm, 5-Pin THD, RoHS, Tray")
      (fields (field (name "MANUFACTURER") "Molex"))
      (libsource (lib "DACֹֹ_Sources") (part "CN-S-4F-RF5"))
    )
    (comp (ref "J17")
      (value "731000114")
      (footprint "MOLX-731000114_V")
      (description "SMA Right-Angle PCB Jack Receptacle, Brass Body, Gold Plated, 50 Ohm, 5-Pin THD, RoHS, Tray")
      (fields (field (name "MANUFACTURER") "Molex"))
      (libsource (lib "DACֹֹ_Sources") (part "CN-S-4F-RF5"))
    )
    (comp (ref "J18")
      (value "731000114")
      (footprint "MOLX-731000114_V")
      (description "SMA Right-Angle PCB Jack Receptacle, Brass Body, Gold Plated, 50 Ohm, 5-Pin THD, RoHS, Tray")
      (fields (field (name "MANUFACTURER") "Molex"))
      (libsource (lib "DACֹֹ_Sources") (part "CN-S-4F-RF5"))
    )
    (comp (ref "L6")
      (value "0805HQ-16NXGLC")
      (footprint "0805HP")
      (fields (field (name "ALTIUM_VALUE") "16nH") (field (name "PUBLISHER") "Altium Limited"))
      (libsource (lib "DACֹֹ_Sources") (part "Inductor Iron"))
    )
    (comp (ref "L7")
      (value "0805HP-33NXGRC")
      (footprint "0805HP")
      (description "0805HP  33nH")
      (fields (field (name "ALTIUM_VALUE") "33nH") (field (name "PUBLISHER") "Altium Limited"))
      (libsource (lib "DACֹֹ_Sources") (part "Inductor Iron"))
    )
    (comp (ref "L8")
      (value "0805HP-33NXGRC")
      (footprint "0805HP")
      (description "0805HP  33nH")
      (fields (field (name "ALTIUM_VALUE") "33nH") (field (name "PUBLISHER") "Altium Limited"))
      (libsource (lib "DACֹֹ_Sources") (part "Inductor Iron"))
    )
    (comp (ref "L9")
      (value "0805HQ-16NXGLC")
      (footprint "0805HP")
      (fields (field (name "ALTIUM_VALUE") "16nH") (field (name "PUBLISHER") "Altium Limited"))
      (libsource (lib "DACֹֹ_Sources") (part "Inductor Iron"))
    )
    (comp (ref "L10")
      (value "0805HQ-16NXGLC")
      (footprint "0805HP")
      (fields (field (name "ALTIUM_VALUE") "16nH") (field (name "PUBLISHER") "Altium Limited"))
      (libsource (lib "DACֹֹ_Sources") (part "Inductor Iron"))
    )
    (comp (ref "L11")
      (value "0805HP-33NXGRC")
      (footprint "0805HP")
      (description "0805HP  33nH")
      (fields (field (name "ALTIUM_VALUE") "33nH") (field (name "PUBLISHER") "Altium Limited"))
      (libsource (lib "DACֹֹ_Sources") (part "Inductor Iron"))
    )
    (comp (ref "L12")
      (value "0805HP-33NXGRC")
      (footprint "0805HP")
      (description "0805HP  33nH")
      (fields (field (name "ALTIUM_VALUE") "33nH") (field (name "PUBLISHER") "Altium Limited"))
      (libsource (lib "DACֹֹ_Sources") (part "Inductor Iron"))
    )
    (comp (ref "L13")
      (value "0805HQ-16NXGLC")
      (footprint "0805HP")
      (fields (field (name "ALTIUM_VALUE") "16nH") (field (name "PUBLISHER") "Altium Limited"))
      (libsource (lib "DACֹֹ_Sources") (part "Inductor Iron"))
    )
    (comp (ref "L14")
      (value "0805HQ-16NXGLC")
      (footprint "0805HP")
      (fields (field (name "ALTIUM_VALUE") "16nH") (field (name "PUBLISHER") "Altium Limited"))
      (libsource (lib "DACֹֹ_Sources") (part "Inductor Iron"))
    )
    (comp (ref "L15")
      (value "0805HP-33NXGRC")
      (footprint "0805HP")
      (description "0805HP  33nH")
      (fields (field (name "ALTIUM_VALUE") "33nH") (field (name "PUBLISHER") "Altium Limited"))
      (libsource (lib "DACֹֹ_Sources") (part "Inductor Iron"))
    )
    (comp (ref "L16")
      (value "0805HP-33NXGRC")
      (footprint "0805HP")
      (description "0805HP  33nH")
      (fields (field (name "ALTIUM_VALUE") "33nH") (field (name "PUBLISHER") "Altium Limited"))
      (libsource (lib "DACֹֹ_Sources") (part "Inductor Iron"))
    )
    (comp (ref "L17")
      (value "0805HQ-16NXGLC")
      (footprint "0805HP")
      (fields (field (name "ALTIUM_VALUE") "16nH") (field (name "PUBLISHER") "Altium Limited"))
      (libsource (lib "DACֹֹ_Sources") (part "Inductor Iron"))
    )
    (comp (ref "L18")
      (value "0805HQ-16NXGLC")
      (footprint "0805HP")
      (fields (field (name "ALTIUM_VALUE") "16nH") (field (name "PUBLISHER") "Altium Limited"))
      (libsource (lib "DACֹֹ_Sources") (part "Inductor Iron"))
    )
    (comp (ref "L19")
      (value "0805HP-33NXGRC")
      (footprint "0805HP")
      (description "0805HP  33nH")
      (fields (field (name "ALTIUM_VALUE") "33nH") (field (name "PUBLISHER") "Altium Limited"))
      (libsource (lib "DACֹֹ_Sources") (part "Inductor Iron"))
    )
    (comp (ref "L20")
      (value "0805HP-33NXGRC")
      (footprint "0805HP")
      (description "0805HP  33nH")
      (fields (field (name "ALTIUM_VALUE") "33nH") (field (name "PUBLISHER") "Altium Limited"))
      (libsource (lib "DACֹֹ_Sources") (part "Inductor Iron"))
    )
    (comp (ref "L21")
      (value "0805HQ-16NXGLC")
      (footprint "0805HP")
      (fields (field (name "ALTIUM_VALUE") "16nH") (field (name "PUBLISHER") "Altium Limited"))
      (libsource (lib "DACֹֹ_Sources") (part "Inductor Iron"))
    )
    (comp (ref "L22")
      (value "0805HQ-16NXGLC")
      (footprint "0805HP")
      (fields (field (name "ALTIUM_VALUE") "16nH") (field (name "PUBLISHER") "Altium Limited"))
      (libsource (lib "DACֹֹ_Sources") (part "Inductor Iron"))
    )
    (comp (ref "L23")
      (value "0805HP-33NXGRC")
      (footprint "0805HP")
      (description "0805HP  33nH")
      (fields (field (name "ALTIUM_VALUE") "33nH") (field (name "PUBLISHER") "Altium Limited"))
      (libsource (lib "DACֹֹ_Sources") (part "Inductor Iron"))
    )
    (comp (ref "L24")
      (value "0805HP-33NXGRC")
      (footprint "0805HP")
      (description "0805HP  33nH")
      (fields (field (name "ALTIUM_VALUE") "33nH") (field (name "PUBLISHER") "Altium Limited"))
      (libsource (lib "DACֹֹ_Sources") (part "Inductor Iron"))
    )
    (comp (ref "L25")
      (value "0805HQ-16NXGLC")
      (footprint "0805HP")
      (fields (field (name "ALTIUM_VALUE") "16nH") (field (name "PUBLISHER") "Altium Limited"))
      (libsource (lib "DACֹֹ_Sources") (part "Inductor Iron"))
    )
    (comp (ref "L26")
      (value "0805HQ-16NXGLC")
      (footprint "0805HP")
      (fields (field (name "ALTIUM_VALUE") "16nH") (field (name "PUBLISHER") "Altium Limited"))
      (libsource (lib "DACֹֹ_Sources") (part "Inductor Iron"))
    )
    (comp (ref "L27")
      (value "0805HP-33NXGRC")
      (footprint "0805HP")
      (description "0805HP  33nH")
      (fields (field (name "ALTIUM_VALUE") "33nH") (field (name "PUBLISHER") "Altium Limited"))
      (libsource (lib "DACֹֹ_Sources") (part "Inductor Iron"))
    )
    (comp (ref "L28")
      (value "0805HP-33NXGRC")
      (footprint "0805HP")
      (description "0805HP  33nH")
      (fields (field (name "ALTIUM_VALUE") "33nH") (field (name "PUBLISHER") "Altium Limited"))
      (libsource (lib "DACֹֹ_Sources") (part "Inductor Iron"))
    )
    (comp (ref "L29")
      (value "0805HQ-16NXGLC")
      (footprint "0805HP")
      (fields (field (name "ALTIUM_VALUE") "16nH") (field (name "PUBLISHER") "Altium Limited"))
      (libsource (lib "DACֹֹ_Sources") (part "Inductor Iron"))
    )
    (comp (ref "L30")
      (value "0805HQ-16NXGLC")
      (footprint "0805HP")
      (fields (field (name "ALTIUM_VALUE") "16nH") (field (name "PUBLISHER") "Altium Limited"))
      (libsource (lib "DACֹֹ_Sources") (part "Inductor Iron"))
    )
    (comp (ref "L31")
      (value "0805HP-33NXGRC")
      (footprint "0805HP")
      (description "0805HP  33nH")
      (fields (field (name "ALTIUM_VALUE") "33nH") (field (name "PUBLISHER") "Altium Limited"))
      (libsource (lib "DACֹֹ_Sources") (part "Inductor Iron"))
    )
    (comp (ref "L32")
      (value "0805HP-33NXGRC")
      (footprint "0805HP")
      (description "0805HP  33nH")
      (fields (field (name "ALTIUM_VALUE") "33nH") (field (name "PUBLISHER") "Altium Limited"))
      (libsource (lib "DACֹֹ_Sources") (part "Inductor Iron"))
    )
    (comp (ref "L33")
      (value "0805HQ-16NXGLC")
      (footprint "0805HP")
      (fields (field (name "ALTIUM_VALUE") "16nH") (field (name "PUBLISHER") "Altium Limited"))
      (libsource (lib "DACֹֹ_Sources") (part "Inductor Iron"))
    )
    (comp (ref "L34")
      (value "0805HQ-16NXGLC")
      (footprint "0805HP")
      (fields (field (name "ALTIUM_VALUE") "16nH") (field (name "PUBLISHER") "Altium Limited"))
      (libsource (lib "DACֹֹ_Sources") (part "Inductor Iron"))
    )
    (comp (ref "L35")
      (value "0805HP-33NXGRC")
      (footprint "0805HP")
      (description "0805HP  33nH")
      (fields (field (name "ALTIUM_VALUE") "33nH") (field (name "PUBLISHER") "Altium Limited"))
      (libsource (lib "DACֹֹ_Sources") (part "Inductor Iron"))
    )
    (comp (ref "L36")
      (value "0805HP-33NXGRC")
      (footprint "0805HP")
      (description "0805HP  33nH")
      (fields (field (name "ALTIUM_VALUE") "33nH") (field (name "PUBLISHER") "Altium Limited"))
      (libsource (lib "DACֹֹ_Sources") (part "Inductor Iron"))
    )
    (comp (ref "L37")
      (value "0805HQ-16NXGLC")
      (footprint "0805HP")
      (fields (field (name "ALTIUM_VALUE") "16nH") (field (name "PUBLISHER") "Altium Limited"))
      (libsource (lib "DACֹֹ_Sources") (part "Inductor Iron"))
    )
    (comp (ref "L38")
      (value "0805HQ-16NXGLC")
      (footprint "0805HP")
      (fields (field (name "ALTIUM_VALUE") "16nH") (field (name "PUBLISHER") "Altium Limited"))
      (libsource (lib "DACֹֹ_Sources") (part "Inductor Iron"))
    )
    (comp (ref "L39")
      (value "0805HP-33NXGRC")
      (footprint "0805HP")
      (description "0805HP  33nH")
      (fields (field (name "ALTIUM_VALUE") "33nH") (field (name "PUBLISHER") "Altium Limited"))
      (libsource (lib "DACֹֹ_Sources") (part "Inductor Iron"))
    )
    (comp (ref "L40")
      (value "0805HP-33NXGRC")
      (footprint "0805HP")
      (description "0805HP  33nH")
      (fields (field (name "ALTIUM_VALUE") "33nH") (field (name "PUBLISHER") "Altium Limited"))
      (libsource (lib "DACֹֹ_Sources") (part "Inductor Iron"))
    )
    (comp (ref "L41")
      (value "0805HQ-16NXGLC")
      (footprint "0805HP")
      (fields (field (name "ALTIUM_VALUE") "16nH") (field (name "PUBLISHER") "Altium Limited"))
      (libsource (lib "DACֹֹ_Sources") (part "Inductor Iron"))
    )
    (comp (ref "L42")
      (value "0805HQ-16NXGLC")
      (footprint "0805HP")
      (fields (field (name "ALTIUM_VALUE") "16nH") (field (name "PUBLISHER") "Altium Limited"))
      (libsource (lib "DACֹֹ_Sources") (part "Inductor Iron"))
    )
    (comp (ref "L43")
      (value "0805HP-33NXGRC")
      (footprint "0805HP")
      (description "0805HP  33nH")
      (fields (field (name "ALTIUM_VALUE") "33nH") (field (name "PUBLISHER") "Altium Limited"))
      (libsource (lib "DACֹֹ_Sources") (part "Inductor Iron"))
    )
    (comp (ref "L44")
      (value "0805HP-33NXGRC")
      (footprint "0805HP")
      (description "0805HP  33nH")
      (fields (field (name "ALTIUM_VALUE") "33nH") (field (name "PUBLISHER") "Altium Limited"))
      (libsource (lib "DACֹֹ_Sources") (part "Inductor Iron"))
    )
    (comp (ref "L45")
      (value "0805HQ-16NXGLC")
      (footprint "0805HP")
      (fields (field (name "ALTIUM_VALUE") "16nH") (field (name "PUBLISHER") "Altium Limited"))
      (libsource (lib "DACֹֹ_Sources") (part "Inductor Iron"))
    )
    (comp (ref "L46")
      (value "0805HQ-16NXGLC")
      (footprint "0805HP")
      (fields (field (name "ALTIUM_VALUE") "16nH") (field (name "PUBLISHER") "Altium Limited"))
      (libsource (lib "DACֹֹ_Sources") (part "Inductor Iron"))
    )
    (comp (ref "L47")
      (value "0805HP-33NXGRC")
      (footprint "0805HP")
      (description "0805HP  33nH")
      (fields (field (name "ALTIUM_VALUE") "33nH") (field (name "PUBLISHER") "Altium Limited"))
      (libsource (lib "DACֹֹ_Sources") (part "Inductor Iron"))
    )
    (comp (ref "L48")
      (value "0805HP-33NXGRC")
      (footprint "0805HP")
      (description "0805HP  33nH")
      (fields (field (name "ALTIUM_VALUE") "33nH") (field (name "PUBLISHER") "Altium Limited"))
      (libsource (lib "DACֹֹ_Sources") (part "Inductor Iron"))
    )
    (comp (ref "L49")
      (value "0805HQ-16NXGLC")
      (footprint "0805HP")
      (fields (field (name "ALTIUM_VALUE") "16nH") (field (name "PUBLISHER") "Altium Limited"))
      (libsource (lib "DACֹֹ_Sources") (part "Inductor Iron"))
    )
    (comp (ref "L50")
      (value "0805HQ-16NXGLC")
      (footprint "0805HP")
      (fields (field (name "ALTIUM_VALUE") "16nH") (field (name "PUBLISHER") "Altium Limited"))
      (libsource (lib "DACֹֹ_Sources") (part "Inductor Iron"))
    )
    (comp (ref "L51")
      (value "0805HP-33NXGRC")
      (footprint "0805HP")
      (description "0805HP  33nH")
      (fields (field (name "ALTIUM_VALUE") "33nH") (field (name "PUBLISHER") "Altium Limited"))
      (libsource (lib "DACֹֹ_Sources") (part "Inductor Iron"))
    )
    (comp (ref "L52")
      (value "0805HP-33NXGRC")
      (footprint "0805HP")
      (description "0805HP  33nH")
      (fields (field (name "ALTIUM_VALUE") "33nH") (field (name "PUBLISHER") "Altium Limited"))
      (libsource (lib "DACֹֹ_Sources") (part "Inductor Iron"))
    )
    (comp (ref "L53")
      (value "0805HQ-16NXGLC")
      (footprint "0805HP")
      (fields (field (name "ALTIUM_VALUE") "16nH") (field (name "PUBLISHER") "Altium Limited"))
      (libsource (lib "DACֹֹ_Sources") (part "Inductor Iron"))
    )
    (comp (ref "L54")
      (value "0805HQ-16NXGLC")
      (footprint "0805HP")
      (fields (field (name "ALTIUM_VALUE") "16nH") (field (name "PUBLISHER") "Altium Limited"))
      (libsource (lib "DACֹֹ_Sources") (part "Inductor Iron"))
    )
    (comp (ref "L55")
      (value "0805HP-33NXGRC")
      (footprint "0805HP")
      (description "0805HP  33nH")
      (fields (field (name "ALTIUM_VALUE") "33nH") (field (name "PUBLISHER") "Altium Limited"))
      (libsource (lib "DACֹֹ_Sources") (part "Inductor Iron"))
    )
    (comp (ref "L56")
      (value "0805HP-33NXGRC")
      (footprint "0805HP")
      (description "0805HP  33nH")
      (fields (field (name "ALTIUM_VALUE") "33nH") (field (name "PUBLISHER") "Altium Limited"))
      (libsource (lib "DACֹֹ_Sources") (part "Inductor Iron"))
    )
    (comp (ref "L57")
      (value "0805HQ-16NXGLC")
      (footprint "0805HP")
      (fields (field (name "ALTIUM_VALUE") "16nH") (field (name "PUBLISHER") "Altium Limited"))
      (libsource (lib "DACֹֹ_Sources") (part "Inductor Iron"))
    )
    (comp (ref "L58")
      (value "0805HQ-16NXGLC")
      (footprint "0805HP")
      (fields (field (name "ALTIUM_VALUE") "16nH") (field (name "PUBLISHER") "Altium Limited"))
      (libsource (lib "DACֹֹ_Sources") (part "Inductor Iron"))
    )
    (comp (ref "L59")
      (value "0805HP-33NXGRC")
      (footprint "0805HP")
      (description "0805HP  33nH")
      (fields (field (name "ALTIUM_VALUE") "33nH") (field (name "PUBLISHER") "Altium Limited"))
      (libsource (lib "DACֹֹ_Sources") (part "Inductor Iron"))
    )
    (comp (ref "L60")
      (value "0805HP-33NXGRC")
      (footprint "0805HP")
      (description "0805HP  33nH")
      (fields (field (name "ALTIUM_VALUE") "33nH") (field (name "PUBLISHER") "Altium Limited"))
      (libsource (lib "DACֹֹ_Sources") (part "Inductor Iron"))
    )
    (comp (ref "L61")
      (value "0805HQ-16NXGLC")
      (footprint "0805HP")
      (fields (field (name "ALTIUM_VALUE") "16nH") (field (name "PUBLISHER") "Altium Limited"))
      (libsource (lib "DACֹֹ_Sources") (part "Inductor Iron"))
    )
    (comp (ref "L62")
      (value "0805HQ-16NXGLC")
      (footprint "0805HP")
      (fields (field (name "ALTIUM_VALUE") "16nH") (field (name "PUBLISHER") "Altium Limited"))
      (libsource (lib "DACֹֹ_Sources") (part "Inductor Iron"))
    )
    (comp (ref "L63")
      (value "0805HP-33NXGRC")
      (footprint "0805HP")
      (description "0805HP  33nH")
      (fields (field (name "ALTIUM_VALUE") "33nH") (field (name "PUBLISHER") "Altium Limited"))
      (libsource (lib "DACֹֹ_Sources") (part "Inductor Iron"))
    )
    (comp (ref "L64")
      (value "0805HP-33NXGRC")
      (footprint "0805HP")
      (description "0805HP  33nH")
      (fields (field (name "ALTIUM_VALUE") "33nH") (field (name "PUBLISHER") "Altium Limited"))
      (libsource (lib "DACֹֹ_Sources") (part "Inductor Iron"))
    )
    (comp (ref "L65")
      (value "0805HQ-16NXGLC")
      (footprint "0805HP")
      (fields (field (name "ALTIUM_VALUE") "16nH") (field (name "PUBLISHER") "Altium Limited"))
      (libsource (lib "DACֹֹ_Sources") (part "Inductor Iron"))
    )
    (comp (ref "L66")
      (value "0805HQ-16NXGLC")
      (footprint "0805HP")
      (fields (field (name "ALTIUM_VALUE") "16nH") (field (name "PUBLISHER") "Altium Limited"))
      (libsource (lib "DACֹֹ_Sources") (part "Inductor Iron"))
    )
    (comp (ref "L67")
      (value "0805HP-33NXGRC")
      (footprint "0805HP")
      (description "0805HP  33nH")
      (fields (field (name "ALTIUM_VALUE") "33nH") (field (name "PUBLISHER") "Altium Limited"))
      (libsource (lib "DACֹֹ_Sources") (part "Inductor Iron"))
    )
    (comp (ref "L68")
      (value "0805HP-33NXGRC")
      (footprint "0805HP")
      (description "0805HP  33nH")
      (fields (field (name "ALTIUM_VALUE") "33nH") (field (name "PUBLISHER") "Altium Limited"))
      (libsource (lib "DACֹֹ_Sources") (part "Inductor Iron"))
    )
    (comp (ref "L69")
      (value "0805HQ-16NXGLC")
      (footprint "0805HP")
      (fields (field (name "ALTIUM_VALUE") "16nH") (field (name "PUBLISHER") "Altium Limited"))
      (libsource (lib "DACֹֹ_Sources") (part "Inductor Iron"))
    )
    (comp (ref "P1")
      (value "Header 10X2")
      (footprint "HEADER_10X2")
      (description "Header, 10-Pin, Dual row")
      (fields (field (name "PUBLISHER") "Altium Limited"))
      (libsource (lib "Miscellaneous Connectors") (part "Header 10X2"))
    )
    (comp (ref "P3")
      (value "Header 3")
      (footprint "HEADER_3X1")
      (description "Header, 3-Pin")
      (fields (field (name "PUBLISHER") "Altium Limited"))
      (libsource (lib "DACֹֹ_Sources") (part "Header 3"))
    )
    (comp (ref "P4")
      (value "Header 3")
      (footprint "HEADER_3X1")
      (description "Header, 3-Pin")
      (fields (field (name "PUBLISHER") "Altium Limited"))
      (libsource (lib "DACֹֹ_Sources") (part "Header 3"))
    )
    (comp (ref "P5")
      (value "Header 3")
      (footprint "HEADER_3X1")
      (description "Header, 3-Pin")
      (fields (field (name "PUBLISHER") "Altium Limited"))
      (libsource (lib "DACֹֹ_Sources") (part "Header 3"))
    )
    (comp (ref "P6")
      (value "Header 3")
      (footprint "HEADER_3X1")
      (description "Header, 3-Pin")
      (fields (field (name "PUBLISHER") "Altium Limited"))
      (libsource (lib "DACֹֹ_Sources") (part "Header 3"))
    )
    (comp (ref "P10")
      (value "Header 4X2")
      (footprint "HEADER_4X2")
      (description "Header, 4-Pin, Dual row")
      (fields (field (name "PUBLISHER") "Altium Limited"))
      (libsource (lib "Miscellaneous Connectors") (part "Header 4X2"))
    )
    (comp (ref "P11")
      (value "Header 3")
      (footprint "HEADER_3X1")
      (description "Header, 3-Pin")
      (fields (field (name "PUBLISHER") "Altium Limited"))
      (libsource (lib "") (part "Header 3_1"))
    )
    (comp (ref "P12")
      (value "Header 3")
      (footprint "HEADER_3X1")
      (description "Header, 3-Pin")
      (fields (field (name "PUBLISHER") "Altium Limited"))
      (libsource (lib "") (part "Header 3_2"))
    )
    (comp (ref "P16")
      (value "Header 3")
      (footprint "HEADER_3X1")
      (description "Header, 3-Pin")
      (fields (field (name "PUBLISHER") "Altium Limited"))
      (libsource (lib "DACֹֹ_Sources") (part "Header 3"))
    )
    (comp (ref "P17")
      (value "Header 3")
      (footprint "HEADER_3X1")
      (description "Header, 3-Pin")
      (fields (field (name "PUBLISHER") "Altium Limited"))
      (libsource (lib "DACֹֹ_Sources") (part "Header 3"))
    )
    (comp (ref "R1")
      (value "RMCF0402FT100R")
      (footprint "R0402")
      (description "100Ω ±1% 0.063W 0402 Thick Film Chip Resistor AEC-Q200 compliant")
      (fields (field (name "TOLERANCE") "1%"))
      (libsource (lib "DACֹֹ_Sources") (part "1029c3af85768c4190bb7ad29bc67b5"))
    )
    (comp (ref "R2")
      (value "CRCW020149R9FKED")
      (footprint "R0201")
      (fields (field (name "MANUFACTURER") "Vishay Dale"))
      (libsource (lib "DACֹֹ_Sources") (part "RES"))
    )
    (comp (ref "R3")
      (value "CRCW020149R9FKED")
      (footprint "R0201")
      (fields (field (name "MANUFACTURER") "Vishay Dale"))
      (libsource (lib "DACֹֹ_Sources") (part "RES"))
    )
    (comp (ref "R4")
      (value "CRCW020149R9FKED")
      (footprint "R0201")
      (fields (field (name "MANUFACTURER") "Vishay Dale"))
      (libsource (lib "DACֹֹ_Sources") (part "RES"))
    )
    (comp (ref "R5")
      (value "CRCW020149R9FKED")
      (footprint "R0201")
      (fields (field (name "MANUFACTURER") "Vishay Dale"))
      (libsource (lib "DACֹֹ_Sources") (part "RES"))
    )
    (comp (ref "R6")
      (value "CRCW020149R9FKED")
      (footprint "R0201")
      (fields (field (name "MANUFACTURER") "Vishay Dale"))
      (libsource (lib "DACֹֹ_Sources") (part "RES"))
    )
    (comp (ref "R7")
      (value "RMCF0402FT100R")
      (footprint "R0402")
      (description "100Ω ±1% 0.063W 0402 Thick Film Chip Resistor AEC-Q200 compliant")
      (fields (field (name "TOLERANCE") "1%"))
      (libsource (lib "DACֹֹ_Sources") (part "1029c3af85768c4190bb7ad29bc67b5"))
    )
    (comp (ref "R8")
      (value "CRCW020149R9FKED")
      (footprint "R0201")
      (fields (field (name "MANUFACTURER") "Vishay Dale"))
      (libsource (lib "DACֹֹ_Sources") (part "RES"))
    )
    (comp (ref "R9")
      (value "AC0402FR-0733RL")
      (footprint "R0402")
      (description "RES 33Ω ±1% 0.063W 0402")
      (fields (field (name "TOLERANCE") "1%"))
      (libsource (lib "Simulation Generic Components") (part "1029c3af85768c4190bb7ad29bc67b5"))
    )
    (comp (ref "R10")
      (value "RMCF0402FT100R")
      (footprint "R0402")
      (description "100Ω ±1% 0.063W 0402 Thick Film Chip Resistor AEC-Q200 compliant")
      (fields (field (name "TOLERANCE") "1%"))
      (libsource (lib "DACֹֹ_Sources") (part "1029c3af85768c4190bb7ad29bc67b5"))
    )
    (comp (ref "R11")
      (value "RMCF0402FT100R")
      (footprint "R0402")
      (description "100Ω ±1% 0.063W 0402 Thick Film Chip Resistor AEC-Q200 compliant")
      (fields (field (name "TOLERANCE") "1%"))
      (libsource (lib "DACֹֹ_Sources") (part "1029c3af85768c4190bb7ad29bc67b5"))
    )
    (comp (ref "R12")
      (value "RMCF0402FT100R")
      (footprint "R0402")
      (description "100Ω ±1% 0.063W 0402 Thick Film Chip Resistor AEC-Q200 compliant")
      (fields (field (name "TOLERANCE") "1%"))
      (libsource (lib "DACֹֹ_Sources") (part "1029c3af85768c4190bb7ad29bc67b5"))
    )
    (comp (ref "R13")
      (value "CRCW020149R9FKED")
      (footprint "R0201")
      (fields (field (name "MANUFACTURER") "Vishay Dale"))
      (libsource (lib "DACֹֹ_Sources") (part "RES"))
    )
    (comp (ref "R14")
      (value "CRCW020149R9FKED")
      (footprint "R0201")
      (fields (field (name "MANUFACTURER") "Vishay Dale"))
      (libsource (lib "DACֹֹ_Sources") (part "RES"))
    )
    (comp (ref "R15")
      (value "CRCW020149R9FKED")
      (footprint "R0201")
      (fields (field (name "MANUFACTURER") "Vishay Dale"))
      (libsource (lib "DACֹֹ_Sources") (part "RES"))
    )
    (comp (ref "R16")
      (value "CRCW020149R9FKED")
      (footprint "R0201")
      (fields (field (name "MANUFACTURER") "Vishay Dale"))
      (libsource (lib "DACֹֹ_Sources") (part "RES"))
    )
    (comp (ref "R17")
      (value "CRCW020149R9FKED")
      (footprint "R0201")
      (fields (field (name "MANUFACTURER") "Vishay Dale"))
      (libsource (lib "DACֹֹ_Sources") (part "RES"))
    )
    (comp (ref "R18")
      (value "CRCW020149R9FKED")
      (footprint "R0201")
      (fields (field (name "MANUFACTURER") "Vishay Dale"))
      (libsource (lib "DACֹֹ_Sources") (part "RES"))
    )
    (comp (ref "R19")
      (value "CRCW020149R9FKED")
      (footprint "R0201")
      (fields (field (name "MANUFACTURER") "Vishay Dale"))
      (libsource (lib "DACֹֹ_Sources") (part "RES"))
    )
    (comp (ref "R20")
      (value "CRCW020149R9FKED")
      (footprint "R0201")
      (fields (field (name "MANUFACTURER") "Vishay Dale"))
      (libsource (lib "DACֹֹ_Sources") (part "RES"))
    )
    (comp (ref "R21")
      (value "CRCW020149R9FKED")
      (footprint "R0201")
      (fields (field (name "MANUFACTURER") "Vishay Dale"))
      (libsource (lib "DACֹֹ_Sources") (part "RES"))
    )
    (comp (ref "R22")
      (value "CRCW020149R9FKED")
      (footprint "R0201")
      (fields (field (name "MANUFACTURER") "Vishay Dale"))
      (libsource (lib "DACֹֹ_Sources") (part "RES"))
    )
    (comp (ref "R45")
      (value "AC0402FR-0715RL")
      (footprint "R0402")
      (description "RES 15Ω ±1% 0.063W 0402")
      (fields (field (name "TOLERANCE") "1%"))
      (libsource (lib "Simulation Generic Components") (part "1029c3af85768c4190bb7ad29bc67b5"))
    )
    (comp (ref "R46")
      (value "AC0402FR-0733RL")
      (footprint "R0402")
      (description "RES 33Ω ±1% 0.063W 0402")
      (fields (field (name "TOLERANCE") "1%"))
      (libsource (lib "Simulation Generic Components") (part "1029c3af85768c4190bb7ad29bc67b5"))
    )
    (comp (ref "R47")
      (value "AC0402FR-0715RL")
      (footprint "R0402")
      (description "RES 15Ω ±1% 0.063W 0402")
      (fields (field (name "TOLERANCE") "1%"))
      (libsource (lib "Simulation Generic Components") (part "1029c3af85768c4190bb7ad29bc67b5"))
    )
    (comp (ref "R48")
      (value "AC0402FR-07120RL")
      (footprint "R0402")
      (description "RES 120Ω ±1% 0.063W 0402")
      (fields (field (name "TOLERANCE") "1%"))
      (libsource (lib "Simulation Generic Components") (part "1029c3af85768c4190bb7ad29bc67b5"))
    )
    (comp (ref "R49")
      (value "AC0402FR-0776R8L")
      (footprint "R0402")
      (description "RES 76.8Ω ±1% 0.063W 0402")
      (libsource (lib "Simulation Generic Components") (part "1029c3af85768c4190bb7ad29bc67b5"))
    )
    (comp (ref "R50")
      (value "AC0402FR-07200RL")
      (footprint "R0402")
      (description "RES 200Ω ±1% 0.063W 0402")
      (fields (field (name "TOLERANCE") "1%"))
      (libsource (lib "Simulation Generic Components") (part "1029c3af85768c4190bb7ad29bc67b5"))
    )
    (comp (ref "R59")
      (value "RMCF0402FT100R")
      (footprint "R0402")
      (description "100Ω ±1% 0.063W 0402 Thick Film Chip Resistor AEC-Q200 compliant")
      (fields (field (name "TOLERANCE") "1%"))
      (libsource (lib "DACֹֹ_Sources") (part "1029c3af85768c4190bb7ad29bc67b5"))
    )
    (comp (ref "R60")
      (value "RMCF0402FT100R")
      (footprint "R0402")
      (description "100Ω ±1% 0.063W 0402 Thick Film Chip Resistor AEC-Q200 compliant")
      (fields (field (name "TOLERANCE") "1%"))
      (libsource (lib "DACֹֹ_Sources") (part "1029c3af85768c4190bb7ad29bc67b5"))
    )
    (comp (ref "R61")
      (value "RMCF0402FT100R")
      (footprint "R0402")
      (description "100Ω ±1% 0.063W 0402 Thick Film Chip Resistor AEC-Q200 compliant")
      (fields (field (name "TOLERANCE") "1%"))
      (libsource (lib "DACֹֹ_Sources") (part "1029c3af85768c4190bb7ad29bc67b5"))
    )
    (comp (ref "R62")
      (value "RMCF0402FT100R")
      (footprint "R0402")
      (description "100Ω ±1% 0.063W 0402 Thick Film Chip Resistor AEC-Q200 compliant")
      (fields (field (name "TOLERANCE") "1%"))
      (libsource (lib "DACֹֹ_Sources") (part "1029c3af85768c4190bb7ad29bc67b5"))
    )
    (comp (ref "R63")
      (value "RMCF0402FT100R")
      (footprint "R0402")
      (description "100Ω ±1% 0.063W 0402 Thick Film Chip Resistor AEC-Q200 compliant")
      (fields (field (name "TOLERANCE") "1%"))
      (libsource (lib "DACֹֹ_Sources") (part "1029c3af85768c4190bb7ad29bc67b5"))
    )
    (comp (ref "R64")
      (value "RMCF0402FT100R")
      (footprint "R0402")
      (description "100Ω ±1% 0.063W 0402 Thick Film Chip Resistor AEC-Q200 compliant")
      (fields (field (name "TOLERANCE") "1%"))
      (libsource (lib "DACֹֹ_Sources") (part "1029c3af85768c4190bb7ad29bc67b5"))
    )
    (comp (ref "R65")
      (value "RMCF0402FT100R")
      (footprint "R0402")
      (description "100Ω ±1% 0.063W 0402 Thick Film Chip Resistor AEC-Q200 compliant")
      (fields (field (name "TOLERANCE") "1%"))
      (libsource (lib "DACֹֹ_Sources") (part "1029c3af85768c4190bb7ad29bc67b5"))
    )
    (comp (ref "R66")
      (value "RMCF0402FT100R")
      (footprint "R0402")
      (description "100Ω ±1% 0.063W 0402 Thick Film Chip Resistor AEC-Q200 compliant")
      (fields (field (name "TOLERANCE") "1%"))
      (libsource (lib "DACֹֹ_Sources") (part "1029c3af85768c4190bb7ad29bc67b5"))
    )
    (comp (ref "R67")
      (value "RMCF0402FT100R")
      (footprint "R0402")
      (description "100Ω ±1% 0.063W 0402 Thick Film Chip Resistor AEC-Q200 compliant")
      (fields (field (name "TOLERANCE") "1%"))
      (libsource (lib "DACֹֹ_Sources") (part "1029c3af85768c4190bb7ad29bc67b5"))
    )
    (comp (ref "R68")
      (value "RMCF0402FT100R")
      (footprint "R0402")
      (description "100Ω ±1% 0.063W 0402 Thick Film Chip Resistor AEC-Q200 compliant")
      (fields (field (name "TOLERANCE") "1%"))
      (libsource (lib "DACֹֹ_Sources") (part "1029c3af85768c4190bb7ad29bc67b5"))
    )
    (comp (ref "R69")
      (value "RMCF0402FT100R")
      (footprint "R0402")
      (description "100Ω ±1% 0.063W 0402 Thick Film Chip Resistor AEC-Q200 compliant")
      (fields (field (name "TOLERANCE") "1%"))
      (libsource (lib "DACֹֹ_Sources") (part "1029c3af85768c4190bb7ad29bc67b5"))
    )
    (comp (ref "R70")
      (value "ERJ-2RKF1001X")
      (footprint "R0402")
      (description "Chip Resistor, 1 KOhm, +/- 1%, 100 mW, -55 to 155 degC, 0402 (1005 Metric), RoHS, Tape and Reel")
      (fields (field (name "MANUFACTURER") "Basic Passives") (field (name "TOLERANCE") "1%"))
      (libsource (lib "DACֹֹ_Sources") (part "RES-2"))
    )
    (comp (ref "R71")
      (value "ERJ-2RKF1271X")
      (footprint "R0402")
      (fields (field (name "MANUFACTURER") "Panasonic"))
      (libsource (lib "DACֹֹ_Sources") (part "RES"))
    )
    (comp (ref "R72")
      (value "CRCW040210R0FKED")
      (footprint "R0402")
      (fields (field (name "MANUFACTURER") "Vishay Dale"))
      (libsource (lib "DACֹֹ_Sources") (part "RES"))
    )
    (comp (ref "R73")
      (value "ERJ-2RKF1001X")
      (footprint "R0402")
      (description "Chip Resistor, 1 KOhm, +/- 1%, 100 mW, -55 to 155 degC, 0402 (1005 Metric), RoHS, Tape and Reel")
      (fields (field (name "MANUFACTURER") "Basic Passives") (field (name "TOLERANCE") "1%"))
      (libsource (lib "DACֹֹ_Sources") (part "RES-2"))
    )
    (comp (ref "R74")
      (value "ERJ2GE0R00X")
      (footprint "R0402")
      (description "Chip Resistor, 0 Ohm, 0.1 W, -55 to 155 degC, 0402 (1005 Metric), RoHS, Tape and Reel")
      (fields (field (name "MANUFACTURER") "Panasonic") (field (name "TOLERANCE") "5%"))
      (libsource (lib "DACֹֹ_Sources") (part "RES-2"))
    )
    (comp (ref "R75")
      (value "ERJ-2RKF1001X")
      (footprint "R0402")
      (description "Chip Resistor, 1 KOhm, +/- 1%, 100 mW, -55 to 155 degC, 0402 (1005 Metric), RoHS, Tape and Reel")
      (fields (field (name "MANUFACTURER") "Basic Passives") (field (name "TOLERANCE") "1%"))
      (libsource (lib "DACֹֹ_Sources") (part "RES-2"))
    )
    (comp (ref "R76")
      (value "ERJ-2RKF1271X")
      (footprint "R0402")
      (fields (field (name "MANUFACTURER") "Panasonic"))
      (libsource (lib "DACֹֹ_Sources") (part "RES"))
    )
    (comp (ref "R77")
      (value "CRCW040210R0FKED")
      (footprint "R0402")
      (fields (field (name "MANUFACTURER") "Vishay Dale"))
      (libsource (lib "DACֹֹ_Sources") (part "RES"))
    )
    (comp (ref "R78")
      (value "ERJ-2RKF1001X")
      (footprint "R0402")
      (description "Chip Resistor, 1 KOhm, +/- 1%, 100 mW, -55 to 155 degC, 0402 (1005 Metric), RoHS, Tape and Reel")
      (fields (field (name "MANUFACTURER") "Basic Passives") (field (name "TOLERANCE") "1%"))
      (libsource (lib "DACֹֹ_Sources") (part "RES-2"))
    )
    (comp (ref "R79")
      (value "ERJ2GE0R00X")
      (footprint "R0402")
      (description "Chip Resistor, 0 Ohm, 0.1 W, -55 to 155 degC, 0402 (1005 Metric), RoHS, Tape and Reel")
      (fields (field (name "MANUFACTURER") "Panasonic") (field (name "TOLERANCE") "5%"))
      (libsource (lib "DACֹֹ_Sources") (part "RES-2"))
    )
    (comp (ref "R80")
      (value "AC0402FR-0791RL")
      (footprint "R0402")
      (description "RES 91Ω ±1% 0.063W 0402")
      (fields (field (name "TOLERANCE") "1%"))
      (libsource (lib "Simulation Generic Components") (part "1029c3af85768c4190bb7ad29bc67b5"))
    )
    (comp (ref "R81")
      (value "AC0402FR-07200RL")
      (footprint "R0402")
      (description "RES 200Ω ±1% 0.063W 0402")
      (fields (field (name "TOLERANCE") "1%"))
      (libsource (lib "Simulation Generic Components") (part "1029c3af85768c4190bb7ad29bc67b5"))
    )
    (comp (ref "R82")
      (value "AC0402FR-0733RL")
      (footprint "R0402")
      (description "RES 33Ω ±1% 0.063W 0402")
      (fields (field (name "TOLERANCE") "1%"))
      (libsource (lib "Simulation Generic Components") (part "1029c3af85768c4190bb7ad29bc67b5"))
    )
    (comp (ref "R83")
      (value "CRCW0402100RFKED")
      (footprint "R0402")
      (description "RES Thick Film, 100Ω, 1%, 0.063W, 100ppm/°C, 0402")
      (fields (field (name "TOLERANCE") "1%"))
      (libsource (lib "DACֹֹ_Sources") (part "1029c3af85768c4190bb7ad29bc67b5"))
    )
    (comp (ref "R99")
      (value "CRCW060349R9FKEA")
      (footprint "R0603")
      (fields (field (name "MANUFACTURER") "Vishay Dale"))
      (libsource (lib "DACֹֹ_Sources") (part "RES"))
    )
    (comp (ref "R100")
      (value "CRCW060349R9FKEA")
      (footprint "R0603")
      (fields (field (name "MANUFACTURER") "Vishay Dale"))
      (libsource (lib "DACֹֹ_Sources") (part "RES"))
    )
    (comp (ref "R101")
      (value "CRCW0603100RJNEA")
      (footprint "R0603")
      (description "RES Thick Film, 100Ω, 5%, 0.1W, 200ppm/°C, 0603")
      (fields (field (name "TOLERANCE") "5%"))
      (libsource (lib "DACֹֹ_Sources") (part "1029c3af85768c4190bb7ad29bc67b5"))
    )
    (comp (ref "R102")
      (value "CRCW0603100RJNEA")
      (footprint "R0603")
      (description "RES Thick Film, 100Ω, 5%, 0.1W, 200ppm/°C, 0603")
      (fields (field (name "TOLERANCE") "5%"))
      (libsource (lib "DACֹֹ_Sources") (part "1029c3af85768c4190bb7ad29bc67b5"))
    )
    (comp (ref "R103")
      (value "CRCW0603100RJNEA")
      (footprint "R0603")
      (description "RES Thick Film, 100Ω, 5%, 0.1W, 200ppm/°C, 0603")
      (fields (field (name "TOLERANCE") "5%"))
      (libsource (lib "DACֹֹ_Sources") (part "1029c3af85768c4190bb7ad29bc67b5"))
    )
    (comp (ref "R104")
      (value "CRCW0603100RJNEA")
      (footprint "R0603")
      (description "RES Thick Film, 100Ω, 5%, 0.1W, 200ppm/°C, 0603")
      (fields (field (name "TOLERANCE") "5%"))
      (libsource (lib "DACֹֹ_Sources") (part "1029c3af85768c4190bb7ad29bc67b5"))
    )
    (comp (ref "R111")
      (value "CRCW0402100RFKED")
      (footprint "R0402")
      (description "RES Thick Film, 100Ω, 1%, 0.063W, 100ppm/°C, 0402")
      (fields (field (name "TOLERANCE") "1%"))
      (libsource (lib "DACֹֹ_Sources") (part "1029c3af85768c4190bb7ad29bc67b5"))
    )
    (comp (ref "R120")
      (value "CRCW0402100RFKED")
      (footprint "R0402")
      (description "RES Thick Film, 100Ω, 1%, 0.063W, 100ppm/°C, 0402")
      (fields (field (name "TOLERANCE") "1%"))
      (libsource (lib "DACֹֹ_Sources") (part "1029c3af85768c4190bb7ad29bc67b5"))
    )
    (comp (ref "R121")
      (value "CRCW0402100RFKED")
      (footprint "R0402")
      (description "RES Thick Film, 100Ω, 1%, 0.063W, 100ppm/°C, 0402")
      (fields (field (name "TOLERANCE") "1%"))
      (libsource (lib "DACֹֹ_Sources") (part "1029c3af85768c4190bb7ad29bc67b5"))
    )
    (comp (ref "R127")
      (value "ERJ2GE0R00X")
      (footprint "R0402")
      (description "Chip Resistor, 0 Ohm, 0.1 W, -55 to 155 degC, 0402 (1005 Metric), RoHS, Tape and Reel")
      (fields (field (name "MANUFACTURER") "Panasonic") (field (name "TOLERANCE") "5%"))
      (libsource (lib "Simulation Generic Components") (part "RES-2"))
    )
    (comp (ref "R128")
      (value "ERJ2GE0R00X")
      (footprint "R0402")
      (description "Chip Resistor, 0 Ohm, 0.1 W, -55 to 155 degC, 0402 (1005 Metric), RoHS, Tape and Reel")
      (fields (field (name "MANUFACTURER") "Panasonic") (field (name "TOLERANCE") "5%"))
      (libsource (lib "Simulation Generic Components") (part "RES-2"))
    )
    (comp (ref "R129")
      (value "AC0402FR-0715RL")
      (footprint "R0402")
      (description "RES 15Ω ±1% 0.063W 0402")
      (fields (field (name "TOLERANCE") "1%"))
      (libsource (lib "Simulation Generic Components") (part "1029c3af85768c4190bb7ad29bc67b5"))
    )
    (comp (ref "R130")
      (value "AC0402FR-0733RL")
      (footprint "R0402")
      (description "RES 33Ω ±1% 0.063W 0402")
      (fields (field (name "TOLERANCE") "1%"))
      (libsource (lib "Simulation Generic Components") (part "1029c3af85768c4190bb7ad29bc67b5"))
    )
    (comp (ref "R131")
      (value "AC0402FR-0715RL")
      (footprint "R0402")
      (description "RES 15Ω ±1% 0.063W 0402")
      (fields (field (name "TOLERANCE") "1%"))
      (libsource (lib "Simulation Generic Components") (part "1029c3af85768c4190bb7ad29bc67b5"))
    )
    (comp (ref "R132")
      (value "AC0402FR-07120RL")
      (footprint "R0402")
      (description "RES 120Ω ±1% 0.063W 0402")
      (fields (field (name "TOLERANCE") "1%"))
      (libsource (lib "Simulation Generic Components") (part "1029c3af85768c4190bb7ad29bc67b5"))
    )
    (comp (ref "R133")
      (value "AC0402FR-0791RL")
      (footprint "R0402")
      (description "RES 91Ω ±1% 0.063W 0402")
      (fields (field (name "TOLERANCE") "1%"))
      (libsource (lib "Simulation Generic Components") (part "1029c3af85768c4190bb7ad29bc67b5"))
    )
    (comp (ref "R134")
      (value "AC0402FR-07200RL")
      (footprint "R0402")
      (description "RES 200Ω ±1% 0.063W 0402")
      (fields (field (name "TOLERANCE") "1%"))
      (libsource (lib "Simulation Generic Components") (part "1029c3af85768c4190bb7ad29bc67b5"))
    )
    (comp (ref "R135")
      (value "RC0402JR-070RL")
      (footprint "R0402")
      (fields (field (name "MANUFACTURER") "Yageo / Phycomp"))
      (libsource (lib "Simulation Generic Components") (part "RES"))
    )
    (comp (ref "R136")
      (value "RC0402JR-070RL")
      (footprint "R0402")
      (fields (field (name "MANUFACTURER") "Yageo / Phycomp"))
      (libsource (lib "Simulation Generic Components") (part "RES"))
    )
    (comp (ref "R137")
      (value "RC0402JR-070RL")
      (footprint "R0402")
      (fields (field (name "MANUFACTURER") "Yageo / Phycomp"))
      (libsource (lib "Simulation Generic Components") (part "RES"))
    )
    (comp (ref "R138")
      (value "RC0402JR-070RL")
      (footprint "R0402")
      (fields (field (name "MANUFACTURER") "Yageo / Phycomp"))
      (libsource (lib "Simulation Generic Components") (part "RES"))
    )
    (comp (ref "R139")
      (value "RC0402JR-070RL")
      (footprint "R0402")
      (fields (field (name "MANUFACTURER") "Yageo / Phycomp"))
      (libsource (lib "Simulation Generic Components") (part "RES"))
    )
    (comp (ref "R140")
      (value "RC0402JR-070RL")
      (footprint "R0402")
      (fields (field (name "MANUFACTURER") "Yageo / Phycomp"))
      (libsource (lib "Simulation Generic Components") (part "RES"))
    )
    (comp (ref "R141")
      (value "RC0402JR-070RL")
      (footprint "R0402")
      (fields (field (name "MANUFACTURER") "Yageo / Phycomp"))
      (libsource (lib "Simulation Generic Components") (part "RES"))
    )
    (comp (ref "R142")
      (value "RC0402JR-070RL")
      (footprint "R0402")
      (fields (field (name "MANUFACTURER") "Yageo / Phycomp"))
      (libsource (lib "Simulation Generic Components") (part "RES"))
    )
    (comp (ref "R143")
      (value "RC0402JR-070RL")
      (footprint "R0402")
      (fields (field (name "MANUFACTURER") "Yageo / Phycomp"))
      (libsource (lib "Simulation Generic Components") (part "RES"))
    )
    (comp (ref "R144")
      (value "RC0402JR-070RL")
      (footprint "R0402")
      (fields (field (name "MANUFACTURER") "Yageo / Phycomp"))
      (libsource (lib "Simulation Generic Components") (part "RES"))
    )
    (comp (ref "R145")
      (value "AC0402FR-07200RL")
      (footprint "R0402")
      (description "RES 200Ω ±1% 0.063W 0402")
      (fields (field (name "TOLERANCE") "1%"))
      (libsource (lib "Simulation Generic Components") (part "1029c3af85768c4190bb7ad29bc67b5"))
    )
    (comp (ref "R146")
      (value "AC0402FR-0776R8L")
      (footprint "R0402")
      (description "RES 76.8Ω ±1% 0.063W 0402")
      (libsource (lib "Simulation Generic Components") (part "1029c3af85768c4190bb7ad29bc67b5"))
    )
    (comp (ref "R147")
      (value "AC0402FR-0733RL")
      (footprint "R0402")
      (description "RES 33Ω ±1% 0.063W 0402")
      (fields (field (name "TOLERANCE") "1%"))
      (libsource (lib "Simulation Generic Components") (part "1029c3af85768c4190bb7ad29bc67b5"))
    )
    (comp (ref "R148")
      (value "RC0402JR-070RL")
      (footprint "R0402")
      (fields (field (name "MANUFACTURER") "Yageo / Phycomp"))
      (libsource (lib "Simulation Generic Components") (part "RES"))
    )
    (comp (ref "R149")
      (value "RC0402JR-070RL")
      (footprint "R0402")
      (fields (field (name "MANUFACTURER") "Yageo / Phycomp"))
      (libsource (lib "Simulation Generic Components") (part "RES"))
    )
    (comp (ref "R150")
      (value "RC0402JR-070RL")
      (footprint "R0402")
      (fields (field (name "MANUFACTURER") "Yageo / Phycomp"))
      (libsource (lib "Simulation Generic Components") (part "RES"))
    )
    (comp (ref "R151")
      (value "RC0402JR-070RL")
      (footprint "R0402")
      (fields (field (name "MANUFACTURER") "Yageo / Phycomp"))
      (libsource (lib "Simulation Generic Components") (part "RES"))
    )
    (comp (ref "R152")
      (value "RC0402JR-070RL")
      (footprint "R0402")
      (fields (field (name "MANUFACTURER") "Yageo / Phycomp"))
      (libsource (lib "Simulation Generic Components") (part "RES"))
    )
    (comp (ref "RN3")
      (value "EXB-2HV470JV")
      (footprint "EXB-2HV470JV")
      (libsource (lib "") (part "Component_1_1"))
    )
    (comp (ref "RN4")
      (value "EXB-2HV470JV")
      (footprint "EXB-2HV470JV")
      (libsource (lib "") (part "Component_1_1"))
    )
    (comp (ref "RN5")
      (value "EXB-2HV470JV")
      (footprint "EXB-2HV470JV")
      (libsource (lib "") (part "Component_1_1"))
    )
    (comp (ref "RN6")
      (value "EXB-2HV470JV")
      (footprint "EXB-2HV470JV")
      (libsource (lib "") (part "Component_1_1"))
    )
    (comp (ref "SW1")
      (value "KT11P3JM34LFS")
      (footprint "FP-KT11P3JM34LFS-MFG")
      (description "SWITCH TACTILE SPST-NO 1VA 32V")
      (fields
        (field (name "OCTOPART") "https://octopart.com/kt11p3jm34lfs-c%26k+components-55425764")
        (field (name "MANUFACTURER") "C&K Components")
      )
      (libsource (lib "DACֹֹ_Sources") (part "a6a22157dac91622554311b1edc5dcf"))
    )
    (comp (ref "SW2")
      (value "KT11P3JM34LFS")
      (footprint "FP-KT11P3JM34LFS-MFG")
      (description "SWITCH TACTILE SPST-NO 1VA 32V")
      (fields
        (field (name "OCTOPART") "https://octopart.com/kt11p3jm34lfs-c%26k+components-55425764")
        (field (name "MANUFACTURER") "C&K Components")
      )
      (libsource (lib "DACֹֹ_Sources") (part "a6a22157dac91622554311b1edc5dcf"))
    )
    (comp (ref "T1")
      (value "ETC1-1-13TR")
      (footprint "FP-ETC1-1-13TR-MFG")
      (description "BALUN 4.5MHZ-3GHZ 1:1 5SMD")
      (fields
        (field (name "MANUFACTURER") "MA-COM")
        (field (name "OCTOPART") "https://octopart.com/etc1-1-13tr-ma-com-7863633")
      )
      (libsource (lib "DACֹֹ_Sources") (part "4f5dfae470883114705f86a4213dd5e"))
    )
    (comp (ref "T4")
      (value "ETC1-1-13TR")
      (footprint "FP-ETC1-1-13TR-MFG")
      (description "BALUN 4.5MHZ-3GHZ 1:1 5SMD")
      (fields
        (field (name "MANUFACTURER") "MA-COM")
        (field (name "OCTOPART") "https://octopart.com/etc1-1-13tr-ma-com-7863633")
      )
      (libsource (lib "DACֹֹ_Sources") (part "4f5dfae470883114705f86a4213dd5e"))
    )
    (comp (ref "T5")
      (value "ETC1-1-13TR")
      (footprint "FP-ETC1-1-13TR-MFG")
      (description "BALUN 4.5MHZ-3GHZ 1:1 5SMD")
      (fields
        (field (name "MANUFACTURER") "MA-COM")
        (field (name "OCTOPART") "https://octopart.com/etc1-1-13tr-ma-com-7863633")
      )
      (libsource (lib "DACֹֹ_Sources") (part "4f5dfae470883114705f86a4213dd5e"))
    )
    (comp (ref "T6")
      (value "ETC1-1-13TR")
      (footprint "FP-ETC1-1-13TR-MFG")
      (description "BALUN 4.5MHZ-3GHZ 1:1 5SMD")
      (fields
        (field (name "MANUFACTURER") "MA-COM")
        (field (name "OCTOPART") "https://octopart.com/etc1-1-13tr-ma-com-7863633")
      )
      (libsource (lib "DACֹֹ_Sources") (part "4f5dfae470883114705f86a4213dd5e"))
    )
    (comp (ref "T7")
      (value "ETC1-1-13TR")
      (footprint "FP-ETC1-1-13TR-MFG")
      (description "BALUN 4.5MHZ-3GHZ 1:1 5SMD")
      (fields
        (field (name "MANUFACTURER") "MA-COM")
        (field (name "OCTOPART") "https://octopart.com/etc1-1-13tr-ma-com-7863633")
      )
      (libsource (lib "DACֹֹ_Sources") (part "4f5dfae470883114705f86a4213dd5e"))
    )
    (comp (ref "T8")
      (value "ETC1-1-13TR")
      (footprint "FP-ETC1-1-13TR-MFG")
      (description "BALUN 4.5MHZ-3GHZ 1:1 5SMD")
      (fields
        (field (name "MANUFACTURER") "MA-COM")
        (field (name "OCTOPART") "https://octopart.com/etc1-1-13tr-ma-com-7863633")
      )
      (libsource (lib "DACֹֹ_Sources") (part "4f5dfae470883114705f86a4213dd5e"))
    )
    (comp (ref "T9")
      (value "ETC1-1-13TR")
      (footprint "FP-ETC1-1-13TR-MFG")
      (description "BALUN 4.5MHZ-3GHZ 1:1 5SMD")
      (fields
        (field (name "MANUFACTURER") "MA-COM")
        (field (name "OCTOPART") "https://octopart.com/etc1-1-13tr-ma-com-7863633")
      )
      (libsource (lib "DACֹֹ_Sources") (part "4f5dfae470883114705f86a4213dd5e"))
    )
    (comp (ref "T10")
      (value "ETC1-1-13TR")
      (footprint "FP-ETC1-1-13TR-MFG")
      (description "BALUN 4.5MHZ-3GHZ 1:1 5SMD")
      (fields
        (field (name "MANUFACTURER") "MA-COM")
        (field (name "OCTOPART") "https://octopart.com/etc1-1-13tr-ma-com-7863633")
      )
      (libsource (lib "DACֹֹ_Sources") (part "4f5dfae470883114705f86a4213dd5e"))
    )
    (comp (ref "TP5")
      (value "5010")
      (footprint "5010")
      (description "Test Point, Red, Through Hole, RoHS, Bulk")
      (fields (field (name "MANUFACTURER") "Keystone"))
      (libsource (lib "DACֹֹ_Sources") (part "TESTPOINT_RED"))
    )
    (comp (ref "TP6")
      (value "5010")
      (footprint "5010")
      (description "Test Point, Red, Through Hole, RoHS, Bulk")
      (fields (field (name "MANUFACTURER") "Keystone"))
      (libsource (lib "DACֹֹ_Sources") (part "TESTPOINT_RED"))
    )
    (comp (ref "TP7")
      (value "5010")
      (footprint "5010")
      (description "Test Point, Red, Through Hole, RoHS, Bulk")
      (fields (field (name "MANUFACTURER") "Keystone"))
      (libsource (lib "DACֹֹ_Sources") (part "TESTPOINT_RED"))
    )
    (comp (ref "TP8")
      (value "5010")
      (footprint "5010")
      (description "Test Point, Red, Through Hole, RoHS, Bulk")
      (fields (field (name "MANUFACTURER") "Keystone"))
      (libsource (lib "DACֹֹ_Sources") (part "TESTPOINT_RED"))
    )
    (comp (ref "U1")
      (value "DAC3484IRKDT")
      (footprint "TI-RKD88-6300X6300TP_V")
      (description "4-Channel 16-Bit 1.25 GSPS DAC, -40 to 85 degC, 88-pin QFN (RKD88), Green (RoHS & no Sb/Br)")
      (fields (field (name "MANUFACTURER") "Texas Instruments"))
      (libsource (lib "DACֹֹ_Sources") (part "TI-DAC348XRKD88-6300X6300TP"))
    )
    (comp (ref "U3")
      (value "ADA4930-2YCPZ-R2")
      (footprint "24-LFCSP")
      (description "IC OPAMP DIFF 2 CIRCUIT 24LFCSP")
      (libsource (lib "Simulation Generic Components") (part "fefbec2708a79eb2d27bfd4b915d167"))
    )
    (comp (ref "U5")
      (value "LTC6957HMS-2#PBF")
      (footprint "12_MSOP")
      (description "IC CLK BUFFER DVR 1:2 12MSOP")
      (libsource (lib "DACֹֹ_Sources") (part "599d8c5e20d6343fb63873f0ba23ec7"))
    )
    (comp (ref "U6")
      (value "DAC3484IRKDT")
      (footprint "TI-RKD88-6300X6300TP_V")
      (description "4-Channel 16-Bit 1.25 GSPS DAC, -40 to 85 degC, 88-pin QFN (RKD88), Green (RoHS & no Sb/Br)")
      (fields (field (name "MANUFACTURER") "Texas Instruments"))
      (libsource (lib "DACֹֹ_Sources") (part "TI-DAC348XRKD88-6300X6300TP"))
    )
    (comp (ref "U7")
      (value "AD9643BCPZ-250")
      (footprint "64-LFCSP_9X9")
      (description "14-Bit, 170 MSPS/210 MSPS/250 MSPS, 1.8 V Dual Analog-to-Digital Converter (ADC)")
      (fields (field (name "COPYRIGHT") "Copyright (C) 2025 Ultra Librarian. All rights reserved."))
      (libsource (lib "Simulation Generic Components") (part "AD9643BCPZ-250"))
    )
    (comp (ref "U22")
      (value "ADT4-1WT")
      (footprint "CD542")
      (libsource (lib "DACֹֹ_Sources") (part "Component_1"))
    )
    (comp (ref "U23")
      (value "ADT4-1WT")
      (footprint "CD542")
      (libsource (lib "DACֹֹ_Sources") (part "Component_1"))
    )
    (comp (ref "U24")
      (value "ADT4-1WT")
      (footprint "CD542")
      (libsource (lib "DACֹֹ_Sources") (part "Component_1"))
    )
    (comp (ref "U25")
      (value "ADT4-1WT")
      (footprint "CD542")
      (libsource (lib "DACֹֹ_Sources") (part "Component_1"))
    )
    (comp (ref "U26")
      (value "ADT4-1WT")
      (footprint "CD542")
      (libsource (lib "DACֹֹ_Sources") (part "Component_1"))
    )
    (comp (ref "U27")
      (value "ADT4-1WT")
      (footprint "CD542")
      (libsource (lib "DACֹֹ_Sources") (part "Component_1"))
    )
    (comp (ref "U28")
      (value "ADT4-1WT")
      (footprint "CD542")
      (libsource (lib "DACֹֹ_Sources") (part "Component_1"))
    )
    (comp (ref "U29")
      (value "ADT4-1WT")
      (footprint "CD542")
      (libsource (lib "DACֹֹ_Sources") (part "Component_1"))
    )
    (comp (ref "U30")
      (value "DS90LV001TMX/NOPB")
      (footprint "SOIC_8")
      (description "IC REDRIVER LVDS 1CH 8SOIC")
      (libsource (lib "DACֹֹ_Sources") (part "30cb43c013c66b9f7606d7aff426576"))
    )
  )
  (nets
    (net (code "1") (name "/1.2VCLK_DAC1") (class "Default")
      (node (ref "C236") (pin "1") (pinfunction "1_1") (pintype "passive"))
      (node (ref "C237") (pin "1") (pinfunction "1_1") (pintype "passive"))
      (node (ref "C238") (pin "1") (pinfunction "1_1") (pintype "passive"))
      (node (ref "U1") (pin "A4") (pinfunction "CLKVDD_A4") (pintype "power_in"))
    )
    (net (code "2") (name "/1.2VCLK_DAC2") (class "Default")
      (node (ref "C257") (pin "1") (pinfunction "1_1") (pintype "passive"))
      (node (ref "C258") (pin "1") (pinfunction "1_1") (pintype "passive"))
      (node (ref "C259") (pin "1") (pinfunction "1_1") (pintype "passive"))
      (node (ref "U6") (pin "A4") (pinfunction "CLKVDD_A4") (pintype "power_in"))
    )
    (net (code "3") (name "/1.2VDAC1") (class "Default")
      (node (ref "C232") (pin "1") (pinfunction "1_1") (pintype "passive"))
      (node (ref "C233") (pin "1") (pinfunction "1_1") (pintype "passive"))
      (node (ref "C234") (pin "1") (pinfunction "1_1") (pintype "passive"))
      (node (ref "C235") (pin "1") (pinfunction "1_1") (pintype "passive"))
      (node (ref "U1") (pin "A35") (pinfunction "DACVDD_A35") (pintype "power_in"))
      (node (ref "U1") (pin "A39") (pinfunction "DACVDD_A39") (pintype "power_in"))
      (node (ref "U1") (pin "A43") (pinfunction "DACVDD_A43") (pintype "power_in"))
    )
    (net (code "4") (name "/1.2VDAC2") (class "Default")
      (node (ref "C253") (pin "1") (pinfunction "1_1") (pintype "passive"))
      (node (ref "C254") (pin "1") (pinfunction "1_1") (pintype "passive"))
      (node (ref "C255") (pin "1") (pinfunction "1_1") (pintype "passive"))
      (node (ref "C256") (pin "1") (pinfunction "1_1") (pintype "passive"))
      (node (ref "U6") (pin "A35") (pinfunction "DACVDD_A35") (pintype "power_in"))
      (node (ref "U6") (pin "A39") (pinfunction "DACVDD_A39") (pintype "power_in"))
      (node (ref "U6") (pin "A43") (pinfunction "DACVDD_A43") (pintype "power_in"))
    )
    (net (code "5") (name "/1.2VDIGI_DAC1") (class "Default")
      (node (ref "C227") (pin "1") (pinfunction "1_1") (pintype "passive"))
      (node (ref "C228") (pin "1") (pinfunction "1_1") (pintype "passive"))
      (node (ref "C229") (pin "1") (pinfunction "1_1") (pintype "passive"))
      (node (ref "C230") (pin "1") (pinfunction "1_1") (pintype "passive"))
      (node (ref "C231") (pin "1") (pinfunction "1_1") (pintype "passive"))
      (node (ref "U1") (pin "A25") (pinfunction "DIGVDD_A25") (pintype "power_in"))
      (node (ref "U1") (pin "A28") (pinfunction "DIGVDD_A28") (pintype "power_in"))
      (node (ref "U1") (pin "A6") (pinfunction "DIGVDD_A6") (pintype "power_in"))
      (node (ref "U1") (pin "A9") (pinfunction "DIGVDD_A9") (pintype "power_in"))
      (node (ref "U1") (pin "B4") (pinfunction "VFUSE_B4") (pintype "power_in"))
    )
    (net (code "6") (name "/1.2VDIGI_DAC2") (class "Default")
      (node (ref "C248") (pin "1") (pinfunction "1_1") (pintype "passive"))
      (node (ref "C249") (pin "1") (pinfunction "1_1") (pintype "passive"))
      (node (ref "C250") (pin "1") (pinfunction "1_1") (pintype "passive"))
      (node (ref "C251") (pin "1") (pinfunction "1_1") (pintype "passive"))
      (node (ref "C252") (pin "1") (pinfunction "1_1") (pintype "passive"))
      (node (ref "U6") (pin "A25") (pinfunction "DIGVDD_A25") (pintype "power_in"))
      (node (ref "U6") (pin "A28") (pinfunction "DIGVDD_A28") (pintype "power_in"))
      (node (ref "U6") (pin "A6") (pinfunction "DIGVDD_A6") (pintype "power_in"))
      (node (ref "U6") (pin "A9") (pinfunction "DIGVDD_A9") (pintype "power_in"))
      (node (ref "U6") (pin "B4") (pinfunction "VFUSE_B4") (pintype "power_in"))
    )
    (net (code "7") (name "/1.8V_AVDD") (class "Default")
      (node (ref "U7") (pin "49") (pinfunction "AVDD_49") (pintype "power_in"))
      (node (ref "U7") (pin "50") (pinfunction "AVDD_50") (pintype "power_in"))
      (node (ref "U7") (pin "53") (pinfunction "AVDD_53") (pintype "power_in"))
      (node (ref "U7") (pin "54") (pinfunction "AVDD_54") (pintype "power_in"))
      (node (ref "U7") (pin "59") (pinfunction "AVDD_59") (pintype "power_in"))
      (node (ref "U7") (pin "60") (pinfunction "AVDD_60") (pintype "power_in"))
      (node (ref "U7") (pin "63") (pinfunction "AVDD_63") (pintype "power_in"))
      (node (ref "U7") (pin "64") (pinfunction "AVDD_64") (pintype "power_in"))
    )
    (net (code "8") (name "/1.8V_DRVDD") (class "Default")
      (node (ref "P16") (pin "1") (pinfunction "1_1") (pintype "passive"))
      (node (ref "P17") (pin "1") (pinfunction "1_1") (pintype "passive"))
      (node (ref "U7") (pin "10") (pinfunction "DRVDD_10") (pintype "power_in"))
      (node (ref "U7") (pin "19") (pinfunction "DRVDD_19") (pintype "power_in"))
      (node (ref "U7") (pin "28") (pinfunction "DRVDD_28") (pintype "power_in"))
      (node (ref "U7") (pin "37") (pinfunction "DRVDD_37") (pintype "power_in"))
    )
    (net (code "9") (name "/3.3VA_DAC1") (class "Default")
      (node (ref "C220") (pin "1") (pinfunction "1_1") (pintype "passive"))
      (node (ref "C221") (pin "1") (pinfunction "1_1") (pintype "passive"))
      (node (ref "C222") (pin "1") (pinfunction "1_1") (pintype "passive"))
      (node (ref "C223") (pin "1") (pinfunction "1_1") (pintype "passive"))
      (node (ref "C224") (pin "1") (pinfunction "1_1") (pintype "passive"))
      (node (ref "C225") (pin "1") (pinfunction "1_1") (pintype "passive"))
      (node (ref "C226") (pin "1") (pinfunction "1_1") (pintype "passive"))
      (node (ref "FB11") (pin "1") (pinfunction "1_1") (pintype "passive"))
      (node (ref "FB17") (pin "1") (pinfunction "1_1") (pintype "passive"))
      (node (ref "U1") (pin "A36") (pinfunction "AVDD_A36") (pintype "power_in"))
      (node (ref "U1") (pin "A37") (pinfunction "AVDD_A37") (pintype "power_in"))
      (node (ref "U1") (pin "A38") (pinfunction "AVDD_A38") (pintype "power_in"))
      (node (ref "U1") (pin "A40") (pinfunction "AVDD_A40") (pintype "power_in"))
      (node (ref "U1") (pin "A41") (pinfunction "AVDD_A41") (pintype "power_in"))
      (node (ref "U1") (pin "A42") (pinfunction "AVDD_A42") (pintype "power_in"))
      (node (ref "U1") (pin "B31") (pinfunction "AVDD_B31") (pintype "power_in"))
    )
    (net (code "10") (name "/3.3VA_DAC2") (class "Default")
      (node (ref "C241") (pin "1") (pinfunction "1_1") (pintype "passive"))
      (node (ref "C242") (pin "1") (pinfunction "1_1") (pintype "passive"))
      (node (ref "C243") (pin "1") (pinfunction "1_1") (pintype "passive"))
      (node (ref "C244") (pin "1") (pinfunction "1_1") (pintype "passive"))
      (node (ref "C245") (pin "1") (pinfunction "1_1") (pintype "passive"))
      (node (ref "C246") (pin "1") (pinfunction "1_1") (pintype "passive"))
      (node (ref "C247") (pin "1") (pinfunction "1_1") (pintype "passive"))
      (node (ref "FB18") (pin "1") (pinfunction "1_1") (pintype "passive"))
      (node (ref "FB19") (pin "1") (pinfunction "1_1") (pintype "passive"))
      (node (ref "U6") (pin "A36") (pinfunction "AVDD_A36") (pintype "power_in"))
      (node (ref "U6") (pin "A37") (pinfunction "AVDD_A37") (pintype "power_in"))
      (node (ref "U6") (pin "A38") (pinfunction "AVDD_A38") (pintype "power_in"))
      (node (ref "U6") (pin "A40") (pinfunction "AVDD_A40") (pintype "power_in"))
      (node (ref "U6") (pin "A41") (pinfunction "AVDD_A41") (pintype "power_in"))
      (node (ref "U6") (pin "A42") (pinfunction "AVDD_A42") (pintype "power_in"))
      (node (ref "U6") (pin "B31") (pinfunction "AVDD_B31") (pintype "power_in"))
    )
    (net (code "11") (name "/3.3VCLK") (class "Default")
      (node (ref "FB22") (pin "1") (pinfunction "1_1") (pintype "passive"))
      (node (ref "FB23") (pin "1") (pinfunction "1_1") (pintype "passive"))
    )
    (net (code "12") (name "/3.3V_AVDD") (class "Default")
      (node (ref "P11") (pin "3") (pinfunction "3_3") (pintype "passive"))
      (node (ref "P12") (pin "3") (pinfunction "3_3") (pintype "passive"))
      (node (ref "U3") (pin "10") (pinfunction "+VS2_10") (pintype "power_in"))
      (node (ref "U3") (pin "3") (pinfunction "+VS1_3") (pintype "power_in"))
      (node (ref "U3") (pin "4") (pinfunction "+VS1_4") (pintype "power_in"))
      (node (ref "U3") (pin "9") (pinfunction "+VS2_9") (pintype "power_in"))
    )
    (net (code "13") (name "/3.3V_LOGIC") (class "Default")
      (node (ref "P3") (pin "1") (pinfunction "1_1") (pintype "passive"))
      (node (ref "P4") (pin "1") (pinfunction "1_1") (pintype "passive"))
      (node (ref "P5") (pin "1") (pinfunction "1_1") (pintype "passive"))
      (node (ref "P6") (pin "1") (pinfunction "1_1") (pintype "passive"))
      (node (ref "R70") (pin "2") (pinfunction "2_2") (pintype "passive"))
      (node (ref "R75") (pin "2") (pinfunction "2_2") (pintype "passive"))
    )
    (net (code "15") (name "/ADCCLK_N") (class "Default")
      (node (ref "U7") (pin "2") (pinfunction "CLK-_2") (pintype "input"))
    )
    (net (code "16") (name "/ADCCLK_P") (class "Default")
      (node (ref "U7") (pin "1") (pinfunction "CLK+_1") (pintype "input"))
    )
    (net (code "17") (name "/ADC_D0_N") (class "Default")
      (node (ref "J2") (pin "99") (pinfunction "99_99") (pintype "passive"))
      (node (ref "RN6") (pin "9") (pinfunction "9_9") (pintype "passive"))
    )
    (net (code "18") (name "/ADC_D0_P") (class "Default")
      (node (ref "J2") (pin "97") (pinfunction "97_97") (pintype "passive"))
      (node (ref "RN6") (pin "10") (pinfunction "10_10") (pintype "passive"))
    )
    (net (code "19") (name "/ADC_D1_N") (class "Default")
      (node (ref "J2") (pin "95") (pinfunction "95_95") (pintype "passive"))
      (node (ref "RN6") (pin "11") (pinfunction "11_11") (pintype "passive"))
    )
    (net (code "20") (name "/ADC_D1_P") (class "Default")
      (node (ref "J2") (pin "93") (pinfunction "93_93") (pintype "passive"))
      (node (ref "RN6") (pin "12") (pinfunction "12_12") (pintype "passive"))
    )
    (net (code "21") (name "/ADC_D2_N") (class "Default")
      (node (ref "J1") (pin "94") (pinfunction "94_94") (pintype "passive"))
      (node (ref "RN6") (pin "13") (pinfunction "13_13") (pintype "passive"))
    )
    (net (code "22") (name "/ADC_D2_P") (class "Default")
      (node (ref "J1") (pin "92") (pinfunction "92_92") (pintype "passive"))
      (node (ref "RN6") (pin "14") (pinfunction "14_14") (pintype "passive"))
    )
    (net (code "23") (name "/ADC_D3_N") (class "Default")
      (node (ref "J1") (pin "90") (pinfunction "90_90") (pintype "passive"))
      (node (ref "RN6") (pin "15") (pinfunction "15_15") (pintype "passive"))
    )
    (net (code "24") (name "/ADC_D3_P") (class "Default")
      (node (ref "J1") (pin "88") (pinfunction "88_88") (pintype "passive"))
      (node (ref "RN6") (pin "16") (pinfunction "16_16") (pintype "passive"))
    )
    (net (code "25") (name "/ADC_D4_N") (class "Default")
      (node (ref "J1") (pin "93") (pinfunction "93_93") (pintype "passive"))
      (node (ref "RN5") (pin "9") (pinfunction "9_9") (pintype "passive"))
    )
    (net (code "26") (name "/ADC_D4_P") (class "Default")
      (node (ref "J1") (pin "91") (pinfunction "91_91") (pintype "passive"))
      (node (ref "RN5") (pin "10") (pinfunction "10_10") (pintype "passive"))
    )
    (net (code "27") (name "/ADC_D5_N") (class "Default")
      (node (ref "J1") (pin "89") (pinfunction "89_89") (pintype "passive"))
      (node (ref "RN5") (pin "11") (pinfunction "11_11") (pintype "passive"))
    )
    (net (code "28") (name "/ADC_D5_P") (class "Default")
      (node (ref "J1") (pin "87") (pinfunction "87_87") (pintype "passive"))
      (node (ref "RN5") (pin "12") (pinfunction "12_12") (pintype "passive"))
    )
    (net (code "29") (name "/ADC_D6_N") (class "Default")
      (node (ref "J1") (pin "64") (pinfunction "64_64") (pintype "passive"))
      (node (ref "RN5") (pin "13") (pinfunction "13_13") (pintype "passive"))
    )
    (net (code "30") (name "/ADC_D6_P") (class "Default")
      (node (ref "J1") (pin "62") (pinfunction "62_62") (pintype "passive"))
      (node (ref "RN5") (pin "14") (pinfunction "14_14") (pintype "passive"))
    )
    (net (code "31") (name "/ADC_D7_N") (class "Default")
      (node (ref "J1") (pin "56") (pinfunction "56_56") (pintype "passive"))
      (node (ref "RN5") (pin "15") (pinfunction "15_15") (pintype "passive"))
    )
    (net (code "32") (name "/ADC_D7_P") (class "Default")
      (node (ref "J1") (pin "54") (pinfunction "54_54") (pintype "passive"))
      (node (ref "RN5") (pin "16") (pinfunction "16_16") (pintype "passive"))
    )
    (net (code "33") (name "/ADC_D8_N") (class "Default")
      (node (ref "J1") (pin "44") (pinfunction "44_44") (pintype "passive"))
      (node (ref "RN4") (pin "9") (pinfunction "9_9") (pintype "passive"))
    )
    (net (code "34") (name "/ADC_D8_P") (class "Default")
      (node (ref "J1") (pin "42") (pinfunction "42_42") (pintype "passive"))
      (node (ref "RN4") (pin "10") (pinfunction "10_10") (pintype "passive"))
    )
    (net (code "35") (name "/ADC_D9_N") (class "Default")
      (node (ref "J1") (pin "32") (pinfunction "32_32") (pintype "passive"))
      (node (ref "RN4") (pin "11") (pinfunction "11_11") (pintype "passive"))
    )
    (net (code "36") (name "/ADC_D9_P") (class "Default")
      (node (ref "J1") (pin "30") (pinfunction "30_30") (pintype "passive"))
      (node (ref "RN4") (pin "12") (pinfunction "12_12") (pintype "passive"))
    )
    (net (code "37") (name "/ADC_D10_N") (class "Default")
      (node (ref "J2") (pin "69") (pinfunction "69_69") (pintype "passive"))
      (node (ref "R148") (pin "2") (pinfunction "2_2") (pintype "passive"))
      (node (ref "RN4") (pin "13") (pinfunction "13_13") (pintype "passive"))
    )
    (net (code "38") (name "/ADC_D10_P") (class "Default")
      (node (ref "J2") (pin "67") (pinfunction "67_67") (pintype "passive"))
      (node (ref "R144") (pin "2") (pinfunction "2_2") (pintype "passive"))
      (node (ref "RN4") (pin "14") (pinfunction "14_14") (pintype "passive"))
    )
    (net (code "39") (name "/ADC_D11_N") (class "Default")
      (node (ref "J2") (pin "63") (pinfunction "63_63") (pintype "passive"))
      (node (ref "R143") (pin "2") (pinfunction "2_2") (pintype "passive"))
      (node (ref "RN4") (pin "15") (pinfunction "15_15") (pintype "passive"))
    )
    (net (code "40") (name "/ADC_D11_P") (class "Default")
      (node (ref "J2") (pin "61") (pinfunction "61_61") (pintype "passive"))
      (node (ref "R142") (pin "2") (pinfunction "2_2") (pintype "passive"))
      (node (ref "RN4") (pin "16") (pinfunction "16_16") (pintype "passive"))
    )
    (net (code "41") (name "/ADC_D12_N") (class "Default")
      (node (ref "J2") (pin "55") (pinfunction "55_55") (pintype "passive"))
      (node (ref "R141") (pin "2") (pinfunction "2_2") (pintype "passive"))
      (node (ref "RN3") (pin "9") (pinfunction "9_9") (pintype "passive"))
    )
    (net (code "42") (name "/ADC_D12_P") (class "Default")
      (node (ref "J2") (pin "53") (pinfunction "53_53") (pintype "passive"))
      (node (ref "R140") (pin "2") (pinfunction "2_2") (pintype "passive"))
      (node (ref "RN3") (pin "10") (pinfunction "10_10") (pintype "passive"))
    )
    (net (code "43") (name "/ADC_D13_N") (class "Default")
      (node (ref "J2") (pin "49") (pinfunction "49_49") (pintype "passive"))
      (node (ref "R139") (pin "2") (pinfunction "2_2") (pintype "passive"))
      (node (ref "RN3") (pin "11") (pinfunction "11_11") (pintype "passive"))
    )
    (net (code "44") (name "/ADC_D13_P") (class "Default")
      (node (ref "J2") (pin "47") (pinfunction "47_47") (pintype "passive"))
      (node (ref "R138") (pin "2") (pinfunction "2_2") (pintype "passive"))
      (node (ref "RN3") (pin "12") (pinfunction "12_12") (pintype "passive"))
    )
    (net (code "45") (name "/ADC_DCLK_N") (class "Default")
      (node (ref "J2") (pin "50") (pinfunction "50_50") (pintype "passive"))
      (node (ref "RN3") (pin "15") (pinfunction "15_15") (pintype "passive"))
    )
    (net (code "46") (name "/ADC_DCLK_P") (class "Default")
      (node (ref "J2") (pin "48") (pinfunction "48_48") (pintype "passive"))
      (node (ref "RN3") (pin "16") (pinfunction "16_16") (pintype "passive"))
    )
    (net (code "47") (name "/ADC_OR_N") (class "Default")
      (node (ref "J1") (pin "49") (pinfunction "49_49") (pintype "passive"))
      (node (ref "RN3") (pin "13") (pinfunction "13_13") (pintype "passive"))
    )
    (net (code "48") (name "/ADC_OR_P") (class "Default")
      (node (ref "J1") (pin "47") (pinfunction "47_47") (pintype "passive"))
      (node (ref "RN3") (pin "14") (pinfunction "14_14") (pintype "passive"))
    )
    (net (code "49") (name "/BIASJ_DAC1") (class "Default")
      (node (ref "R71") (pin "1") (pinfunction "1_1") (pintype "passive"))
      (node (ref "U1") (pin "A33") (pinfunction "BIASJ_A33") (pintype "passive"))
    )
    (net (code "50") (name "/BIASJ_DAC2") (class "Default")
      (node (ref "R76") (pin "1") (pinfunction "1_1") (pintype "passive"))
      (node (ref "U6") (pin "A33") (pinfunction "BIASJ_A33") (pintype "passive"))
    )
    (net (code "51") (name "/CSB_ADC") (class "Default")
      (node (ref "J2") (pin "5") (pinfunction "5_5") (pintype "passive"))
      (node (ref "U7") (pin "46") (pinfunction "CSB_46") (pintype "input"))
    )
    (net (code "52") (name "/CS_DAC1") (class "Default")
      (node (ref "J2") (pin "1") (pinfunction "1_1") (pintype "passive"))
      (node (ref "U1") (pin "B28") (pinfunction "SDENB_B28") (pintype "input"))
    )
    (net (code "53") (name "/CS_DAC2") (class "Default")
      (node (ref "J2") (pin "7") (pinfunction "7_7") (pintype "passive"))
      (node (ref "U6") (pin "B28") (pinfunction "SDENB_B28") (pintype "input"))
    )
    (net (code "54") (name "/CS_EXTERNAL_COMP") (class "Default")
      (node (ref "J2") (pin "6") (pinfunction "6_6") (pintype "passive"))
      (node (ref "R149") (pin "1") (pinfunction "1_1") (pintype "passive"))
    )
    (net (code "55") (name "/DCLK_N") (class "Default")
      (node (ref "RN3") (pin "2") (pinfunction "2_2") (pintype "passive"))
      (node (ref "U7") (pin "24") (pinfunction "DCO-_24") (pintype "output"))
    )
    (net (code "56") (name "/DCLK_P") (class "Default")
      (node (ref "RN3") (pin "1") (pinfunction "1_1") (pintype "passive"))
      (node (ref "U7") (pin "25") (pinfunction "DCO+_25") (pintype "output"))
    )
    (net (code "57") (name "/DOUT0_N") (class "Default")
      (node (ref "RN6") (pin "8") (pinfunction "8_8") (pintype "passive"))
      (node (ref "U7") (pin "8") (pinfunction "D0-(LSB)_8") (pintype "output"))
    )
    (net (code "58") (name "/DOUT0_P") (class "Default")
      (node (ref "RN6") (pin "7") (pinfunction "7_7") (pintype "passive"))
      (node (ref "U7") (pin "9") (pinfunction "D0+(LSB)_9") (pintype "output"))
    )
    (net (code "59") (name "/DOUT1_N") (class "Default")
      (node (ref "RN6") (pin "6") (pinfunction "6_6") (pintype "passive"))
      (node (ref "U7") (pin "11") (pinfunction "D1-_11") (pintype "output"))
    )
    (net (code "60") (name "/DOUT1_P") (class "Default")
      (node (ref "RN6") (pin "5") (pinfunction "5_5") (pintype "passive"))
      (node (ref "U7") (pin "12") (pinfunction "D1+_12") (pintype "output"))
    )
    (net (code "61") (name "/DOUT2_N") (class "Default")
      (node (ref "RN6") (pin "4") (pinfunction "4_4") (pintype "passive"))
      (node (ref "U7") (pin "13") (pinfunction "D2-_13") (pintype "output"))
    )
    (net (code "62") (name "/DOUT2_P") (class "Default")
      (node (ref "RN6") (pin "3") (pinfunction "3_3") (pintype "passive"))
      (node (ref "U7") (pin "14") (pinfunction "D2+_14") (pintype "output"))
    )
    (net (code "63") (name "/DOUT3_N") (class "Default")
      (node (ref "RN6") (pin "2") (pinfunction "2_2") (pintype "passive"))
      (node (ref "U7") (pin "15") (pinfunction "D3-_15") (pintype "output"))
    )
    (net (code "64") (name "/DOUT3_P") (class "Default")
      (node (ref "RN6") (pin "1") (pinfunction "1_1") (pintype "passive"))
      (node (ref "U7") (pin "16") (pinfunction "D3+_16") (pintype "output"))
    )
    (net (code "65") (name "/DOUT4_N") (class "Default")
      (node (ref "RN5") (pin "8") (pinfunction "8_8") (pintype "passive"))
      (node (ref "U7") (pin "17") (pinfunction "D4-_17") (pintype "output"))
    )
    (net (code "66") (name "/DOUT4_P") (class "Default")
      (node (ref "RN5") (pin "7") (pinfunction "7_7") (pintype "passive"))
      (node (ref "U7") (pin "18") (pinfunction "D4+_18") (pintype "output"))
    )
    (net (code "67") (name "/DOUT5_N") (class "Default")
      (node (ref "RN5") (pin "6") (pinfunction "6_6") (pintype "passive"))
      (node (ref "U7") (pin "20") (pinfunction "D5-_20") (pintype "output"))
    )
    (net (code "68") (name "/DOUT5_P") (class "Default")
      (node (ref "RN5") (pin "5") (pinfunction "5_5") (pintype "passive"))
      (node (ref "U7") (pin "21") (pinfunction "D5+_21") (pintype "output"))
    )
    (net (code "69") (name "/DOUT6_N") (class "Default")
      (node (ref "RN5") (pin "4") (pinfunction "4_4") (pintype "passive"))
      (node (ref "U7") (pin "22") (pinfunction "D6-_22") (pintype "output"))
    )
    (net (code "70") (name "/DOUT6_P") (class "Default")
      (node (ref "RN5") (pin "3") (pinfunction "3_3") (pintype "passive"))
      (node (ref "U7") (pin "23") (pinfunction "D6+_23") (pintype "output"))
    )
    (net (code "71") (name "/DOUT7_N") (class "Default")
      (node (ref "RN5") (pin "2") (pinfunction "2_2") (pintype "passive"))
      (node (ref "U7") (pin "26") (pinfunction "D7-_26") (pintype "output"))
    )
    (net (code "72") (name "/DOUT7_P") (class "Default")
      (node (ref "RN5") (pin "1") (pinfunction "1_1") (pintype "passive"))
      (node (ref "U7") (pin "27") (pinfunction "D7+_27") (pintype "output"))
    )
    (net (code "73") (name "/DOUT8_N") (class "Default")
      (node (ref "RN4") (pin "8") (pinfunction "8_8") (pintype "passive"))
      (node (ref "U7") (pin "29") (pinfunction "D8-_29") (pintype "output"))
    )
    (net (code "74") (name "/DOUT8_P") (class "Default")
      (node (ref "RN4") (pin "7") (pinfunction "7_7") (pintype "passive"))
      (node (ref "U7") (pin "30") (pinfunction "D8+_30") (pintype "output"))
    )
    (net (code "75") (name "/DOUT9_N") (class "Default")
      (node (ref "RN4") (pin "6") (pinfunction "6_6") (pintype "passive"))
      (node (ref "U7") (pin "31") (pinfunction "D9-_31") (pintype "output"))
    )
    (net (code "76") (name "/DOUT9_P") (class "Default")
      (node (ref "RN4") (pin "5") (pinfunction "5_5") (pintype "passive"))
      (node (ref "U7") (pin "32") (pinfunction "D9+_32") (pintype "output"))
    )
    (net (code "77") (name "/DOUT10_N") (class "Default")
      (node (ref "RN4") (pin "4") (pinfunction "4_4") (pintype "passive"))
      (node (ref "U7") (pin "33") (pinfunction "D10-_33") (pintype "output"))
    )
    (net (code "78") (name "/DOUT10_P") (class "Default")
      (node (ref "RN4") (pin "3") (pinfunction "3_3") (pintype "passive"))
      (node (ref "U7") (pin "34") (pinfunction "D10+_34") (pintype "output"))
    )
    (net (code "79") (name "/DOUT11_N") (class "Default")
      (node (ref "RN4") (pin "2") (pinfunction "2_2") (pintype "passive"))
      (node (ref "U7") (pin "35") (pinfunction "D11-_35") (pintype "output"))
    )
    (net (code "80") (name "/DOUT11_P") (class "Default")
      (node (ref "RN4") (pin "1") (pinfunction "1_1") (pintype "passive"))
      (node (ref "U7") (pin "36") (pinfunction "D11+_36") (pintype "output"))
    )
    (net (code "81") (name "/DOUT12_N") (class "Default")
      (node (ref "RN3") (pin "8") (pinfunction "8_8") (pintype "passive"))
      (node (ref "U7") (pin "38") (pinfunction "D12-_38") (pintype "output"))
    )
    (net (code "82") (name "/DOUT12_P") (class "Default")
      (node (ref "RN3") (pin "7") (pinfunction "7_7") (pintype "passive"))
      (node (ref "U7") (pin "39") (pinfunction "D12+_39") (pintype "output"))
    )
    (net (code "83") (name "/DOUT13_N") (class "Default")
      (node (ref "RN3") (pin "6") (pinfunction "6_6") (pintype "passive"))
      (node (ref "U7") (pin "40") (pinfunction "D13-(MSB)_40") (pintype "output"))
    )
    (net (code "84") (name "/DOUT13_P") (class "Default")
      (node (ref "RN3") (pin "5") (pinfunction "5_5") (pintype "passive"))
      (node (ref "U7") (pin "41") (pinfunction "D13+(MSB)_41") (pintype "output"))
    )
    (net (code "85") (name "/DXP0_N") (class "Default")
      (node (ref "J1") (pin "100") (pinfunction "100_100") (pintype "passive"))
      (node (ref "P10") (pin "6") (pinfunction "6_6") (pintype "passive"))
    )
    (net (code "86") (name "/DXP0_P") (class "Default")
      (node (ref "J1") (pin "98") (pinfunction "98_98") (pintype "passive"))
      (node (ref "P10") (pin "5") (pinfunction "5_5") (pintype "passive"))
    )
    (net (code "87") (name "/EXTIO_DAC1") (class "Default")
      (node (ref "C211") (pin "1") (pinfunction "1_1") (pintype "passive"))
      (node (ref "U1") (pin "A34") (pinfunction "EXTIO_A34") (pintype "bidirectional"))
    )
    (net (code "88") (name "/EXTIO_DAC2") (class "Default")
      (node (ref "C215") (pin "1") (pinfunction "1_1") (pintype "passive"))
      (node (ref "U6") (pin "A34") (pinfunction "EXTIO_A34") (pintype "bidirectional"))
    )
    (net (code "89") (name "/EXT_COM_0_N") (class "Default")
      (node (ref "P1") (pin "8") (pinfunction "8_8") (pintype "passive"))
      (node (ref "R150") (pin "1") (pinfunction "1_1") (pintype "passive"))
    )
    (net (code "90") (name "/EXT_COM_0_P") (class "Default")
      (node (ref "P1") (pin "7") (pinfunction "7_7") (pintype "passive"))
      (node (ref "R135") (pin "1") (pinfunction "1_1") (pintype "passive"))
    )
    (net (code "91") (name "/EXT_COM_1_N") (class "Default")
      (node (ref "P1") (pin "10") (pinfunction "10_10") (pintype "passive"))
      (node (ref "R137") (pin "1") (pinfunction "1_1") (pintype "passive"))
    )
    (net (code "92") (name "/EXT_COM_1_P") (class "Default")
      (node (ref "P1") (pin "9") (pinfunction "9_9") (pintype "passive"))
      (node (ref "R136") (pin "1") (pinfunction "1_1") (pintype "passive"))
    )
    (net (code "93") (name "/EXT_COM_2_N") (class "Default")
      (node (ref "P1") (pin "12") (pinfunction "12_12") (pintype "passive"))
      (node (ref "R139") (pin "1") (pinfunction "1_1") (pintype "passive"))
    )
    (net (code "94") (name "/EXT_COM_2_P") (class "Default")
      (node (ref "P1") (pin "11") (pinfunction "11_11") (pintype "passive"))
      (node (ref "R138") (pin "1") (pinfunction "1_1") (pintype "passive"))
    )
    (net (code "95") (name "/EXT_COM_3_N") (class "Default")
      (node (ref "P1") (pin "14") (pinfunction "14_14") (pintype "passive"))
      (node (ref "R141") (pin "1") (pinfunction "1_1") (pintype "passive"))
    )
    (net (code "96") (name "/EXT_COM_3_P") (class "Default")
      (node (ref "P1") (pin "13") (pinfunction "13_13") (pintype "passive"))
      (node (ref "R140") (pin "1") (pinfunction "1_1") (pintype "passive"))
    )
    (net (code "97") (name "/EXT_COM_4_N") (class "Default")
      (node (ref "P1") (pin "16") (pinfunction "16_16") (pintype "passive"))
      (node (ref "R143") (pin "1") (pinfunction "1_1") (pintype "passive"))
    )
    (net (code "98") (name "/EXT_COM_4_P") (class "Default")
      (node (ref "P1") (pin "15") (pinfunction "15_15") (pintype "passive"))
      (node (ref "R142") (pin "1") (pinfunction "1_1") (pintype "passive"))
    )
    (net (code "99") (name "/EXT_COM_5_N") (class "Default")
      (node (ref "P1") (pin "18") (pinfunction "18_18") (pintype "passive"))
      (node (ref "R148") (pin "1") (pinfunction "1_1") (pintype "passive"))
    )
    (net (code "100") (name "/EXT_COM_5_P") (class "Default")
      (node (ref "P1") (pin "17") (pinfunction "17_17") (pintype "passive"))
      (node (ref "R144") (pin "1") (pinfunction "1_1") (pintype "passive"))
    )
    (net (code "101") (name "/EXT_CS_EXTERNAL_COMP") (class "Default")
      (node (ref "P1") (pin "3") (pinfunction "3_3") (pintype "passive"))
      (node (ref "R149") (pin "2") (pinfunction "2_2") (pintype "passive"))
    )
    (net (code "102") (name "/EXT_SDO") (class "Default")
      (node (ref "P1") (pin "5") (pinfunction "5_5") (pintype "passive"))
      (node (ref "R152") (pin "2") (pinfunction "2_2") (pintype "passive"))
    )
    (net (code "103") (name "/EX_SPI_CLK") (class "Default")
      (node (ref "P1") (pin "4") (pinfunction "4_4") (pintype "passive"))
      (node (ref "R151") (pin "1") (pinfunction "1_1") (pintype "passive"))
    )
    (net (code "104") (name "/EX_SPI_MISO") (class "Default")
      (node (ref "J2") (pin "3") (pinfunction "3_3") (pintype "passive"))
      (node (ref "P1") (pin "6") (pinfunction "6_6") (pintype "passive"))
      (node (ref "U1") (pin "A30") (pinfunction "SDIO_A30") (pintype "bidirectional"))
      (node (ref "U6") (pin "A30") (pinfunction "SDIO_A30") (pintype "bidirectional"))
      (node (ref "U7") (pin "44") (pinfunction "SDIO_44") (pintype "bidirectional"))
    )
    (net (code "105") (name "/FPGA_CLK_N") (class "Default")
      (node (ref "J1") (pin "50") (pinfunction "50_50") (pintype "passive"))
    )
    (net (code "106") (name "/FPGA_CLK_P") (class "Default")
      (node (ref "J1") (pin "48") (pinfunction "48_48") (pintype "passive"))
    )
    (net (code "107") (name "/GPIO0") (class "Default")
      (node (ref "J2") (pin "94") (pinfunction "94_94") (pintype "passive"))
    )
    (net (code "108") (name "/GPIO1") (class "Default")
      (node (ref "J2") (pin "96") (pinfunction "96_96") (pintype "passive"))
    )
    (net (code "109") (name "/IOUT1A_N") (class "Default")
      (node (ref "L10") (pin "1") (pinfunction "1_1") (pintype "passive"))
      (node (ref "R4") (pin "2") (pinfunction "2_2") (pintype "passive"))
      (node (ref "U1") (pin "B38") (pinfunction "IOUTAN_B38") (pintype "output"))
    )
    (net (code "110") (name "/IOUT1A_P") (class "Default")
      (node (ref "L6") (pin "2") (pinfunction "2_2") (pintype "passive"))
      (node (ref "R2") (pin "2") (pinfunction "2_2") (pintype "passive"))
      (node (ref "U1") (pin "B39") (pinfunction "IOUTAP_B39") (pintype "output"))
    )
    (net (code "111") (name "/IOUT1B_N") (class "Default")
      (node (ref "L18") (pin "1") (pinfunction "1_1") (pintype "passive"))
      (node (ref "R5") (pin "2") (pinfunction "2_2") (pintype "passive"))
      (node (ref "U1") (pin "B37") (pinfunction "IOUTBN_B37") (pintype "output"))
    )
    (net (code "112") (name "/IOUT1B_P") (class "Default")
      (node (ref "L14") (pin "2") (pinfunction "2_2") (pintype "passive"))
      (node (ref "R3") (pin "2") (pinfunction "2_2") (pintype "passive"))
      (node (ref "U1") (pin "B36") (pinfunction "IOUTBP_B36") (pintype "output"))
    )
    (net (code "113") (name "/IOUT1C_N") (class "Default")
      (node (ref "L26") (pin "1") (pinfunction "1_1") (pintype "passive"))
      (node (ref "R8") (pin "2") (pinfunction "2_2") (pintype "passive"))
      (node (ref "U1") (pin "B34") (pinfunction "IOUTCN_B34") (pintype "output"))
    )
    (net (code "114") (name "/IOUT1C_P") (class "Default")
      (node (ref "L22") (pin "2") (pinfunction "2_2") (pintype "passive"))
      (node (ref "R6") (pin "2") (pinfunction "2_2") (pintype "passive"))
      (node (ref "U1") (pin "B35") (pinfunction "IOUTCP_B35") (pintype "output"))
    )
    (net (code "115") (name "/IOUT1D_N") (class "Default")
      (node (ref "L34") (pin "1") (pinfunction "1_1") (pintype "passive"))
      (node (ref "R14") (pin "2") (pinfunction "2_2") (pintype "passive"))
      (node (ref "U1") (pin "B33") (pinfunction "IOUTDN_B33") (pintype "output"))
    )
    (net (code "116") (name "/IOUT1D_P") (class "Default")
      (node (ref "L30") (pin "2") (pinfunction "2_2") (pintype "passive"))
      (node (ref "R13") (pin "2") (pinfunction "2_2") (pintype "passive"))
      (node (ref "U1") (pin "B32") (pinfunction "IOUTDP_B32") (pintype "output"))
    )
    (net (code "117") (name "/IOUT2A_N") (class "Default")
      (node (ref "L42") (pin "1") (pinfunction "1_1") (pintype "passive"))
      (node (ref "R17") (pin "2") (pinfunction "2_2") (pintype "passive"))
      (node (ref "U6") (pin "B38") (pinfunction "IOUTAN_B38") (pintype "output"))
    )
    (net (code "118") (name "/IOUT2A_P") (class "Default")
      (node (ref "L38") (pin "2") (pinfunction "2_2") (pintype "passive"))
      (node (ref "R15") (pin "2") (pinfunction "2_2") (pintype "passive"))
      (node (ref "U6") (pin "B39") (pinfunction "IOUTAP_B39") (pintype "output"))
    )
    (net (code "119") (name "/IOUT2B_N") (class "Default")
      (node (ref "L50") (pin "1") (pinfunction "1_1") (pintype "passive"))
      (node (ref "R18") (pin "2") (pinfunction "2_2") (pintype "passive"))
      (node (ref "U6") (pin "B37") (pinfunction "IOUTBN_B37") (pintype "output"))
    )
    (net (code "120") (name "/IOUT2B_P") (class "Default")
      (node (ref "L46") (pin "2") (pinfunction "2_2") (pintype "passive"))
      (node (ref "R16") (pin "2") (pinfunction "2_2") (pintype "passive"))
      (node (ref "U6") (pin "B36") (pinfunction "IOUTBP_B36") (pintype "output"))
    )
    (net (code "121") (name "/IOUT2C_N") (class "Default")
      (node (ref "L58") (pin "1") (pinfunction "1_1") (pintype "passive"))
      (node (ref "R21") (pin "2") (pinfunction "2_2") (pintype "passive"))
      (node (ref "U6") (pin "B34") (pinfunction "IOUTCN_B34") (pintype "output"))
    )
    (net (code "122") (name "/IOUT2C_P") (class "Default")
      (node (ref "L54") (pin "2") (pinfunction "2_2") (pintype "passive"))
      (node (ref "R19") (pin "2") (pinfunction "2_2") (pintype "passive"))
      (node (ref "U6") (pin "B35") (pinfunction "IOUTCP_B35") (pintype "output"))
    )
    (net (code "123") (name "/IOUT2D_N") (class "Default")
      (node (ref "L66") (pin "1") (pinfunction "1_1") (pintype "passive"))
      (node (ref "R22") (pin "2") (pinfunction "2_2") (pintype "passive"))
      (node (ref "U6") (pin "B33") (pinfunction "IOUTDN_B33") (pintype "output"))
    )
    (net (code "124") (name "/IOUT2D_P") (class "Default")
      (node (ref "L62") (pin "2") (pinfunction "2_2") (pintype "passive"))
      (node (ref "R20") (pin "2") (pinfunction "2_2") (pintype "passive"))
      (node (ref "U6") (pin "B32") (pinfunction "IOUTDP_B32") (pintype "output"))
    )
    (net (code "125") (name "/IOVDD_DAC1") (class "Default")
      (node (ref "C202") (pin "1") (pinfunction "1_1") (pintype "passive"))
      (node (ref "C203") (pin "1") (pinfunction "1_1") (pintype "passive"))
      (node (ref "C204") (pin "1") (pinfunction "1_1") (pintype "passive"))
      (node (ref "C205") (pin "1") (pinfunction "1_1") (pintype "passive"))
      (node (ref "FB17") (pin "2") (pinfunction "2_2") (pintype "passive"))
      (node (ref "U1") (pin "A17") (pinfunction "IOVDD_A17") (pintype "power_in"))
      (node (ref "U1") (pin "B25") (pinfunction "IOVDD_B25") (pintype "power_in"))
      (node (ref "U1") (pin "B6") (pinfunction "IOVDD_B6") (pintype "power_in"))
    )
    (net (code "126") (name "/IOVDD_DAC2") (class "Default")
      (node (ref "C206") (pin "1") (pinfunction "1_1") (pintype "passive"))
      (node (ref "C207") (pin "1") (pinfunction "1_1") (pintype "passive"))
      (node (ref "C208") (pin "1") (pinfunction "1_1") (pintype "passive"))
      (node (ref "C209") (pin "1") (pinfunction "1_1") (pintype "passive"))
      (node (ref "FB19") (pin "2") (pinfunction "2_2") (pintype "passive"))
      (node (ref "U6") (pin "A17") (pinfunction "IOVDD_A17") (pintype "power_in"))
      (node (ref "U6") (pin "B25") (pinfunction "IOVDD_B25") (pintype "power_in"))
      (node (ref "U6") (pin "B6") (pinfunction "IOVDD_B6") (pintype "power_in"))
    )
    (net (code "127") (name "/JX1_D0_DAC1_N") (class "Default")
      (node (ref "J2") (pin "19") (pinfunction "19_19") (pintype "passive"))
      (node (ref "U1") (pin "A27") (pinfunction "D0N_(LSB)_A27") (pintype "input"))
    )
    (net (code "128") (name "/JX1_D0_DAC1_P") (class "Default")
      (node (ref "J2") (pin "17") (pinfunction "17_17") (pintype "passive"))
      (node (ref "U1") (pin "B24") (pinfunction "D0P_(LSB)_B24") (pintype "input"))
    )
    (net (code "129") (name "/JX1_D1_DAC1_N") (class "Default")
      (node (ref "J2") (pin "25") (pinfunction "25_25") (pintype "passive"))
      (node (ref "U1") (pin "A26") (pinfunction "D1N_A26") (pintype "input"))
    )
    (net (code "130") (name "/JX1_D1_DAC1_P") (class "Default")
      (node (ref "J2") (pin "23") (pinfunction "23_23") (pintype "passive"))
      (node (ref "U1") (pin "B23") (pinfunction "D1P_B23") (pintype "input"))
    )
    (net (code "131") (name "/JX1_D2_DAC1_N") (class "Default")
      (node (ref "J2") (pin "31") (pinfunction "31_31") (pintype "passive"))
      (node (ref "U1") (pin "B22") (pinfunction "D2N_B22") (pintype "input"))
    )
    (net (code "132") (name "/JX1_D2_DAC1_P") (class "Default")
      (node (ref "J2") (pin "29") (pinfunction "29_29") (pintype "passive"))
      (node (ref "U1") (pin "A24") (pinfunction "D2P_A24") (pintype "input"))
    )
    (net (code "133") (name "/JX1_D3_DAC1_N") (class "Default")
      (node (ref "J2") (pin "20") (pinfunction "20_20") (pintype "passive"))
      (node (ref "U1") (pin "B21") (pinfunction "D3N_B21") (pintype "input"))
    )
    (net (code "134") (name "/JX1_D3_DAC1_P") (class "Default")
      (node (ref "J2") (pin "18") (pinfunction "18_18") (pintype "passive"))
      (node (ref "U1") (pin "A23") (pinfunction "D3P_A23") (pintype "input"))
    )
    (net (code "135") (name "/JX1_D4_DAC1_N") (class "Default")
      (node (ref "J2") (pin "26") (pinfunction "26_26") (pintype "passive"))
      (node (ref "U1") (pin "A22") (pinfunction "D4N_A22") (pintype "input"))
    )
    (net (code "136") (name "/JX1_D4_DAC1_P") (class "Default")
      (node (ref "J2") (pin "24") (pinfunction "24_24") (pintype "passive"))
      (node (ref "U1") (pin "B20") (pinfunction "D4P_B20") (pintype "input"))
    )
    (net (code "137") (name "/JX1_D5_DAC1_N") (class "Default")
      (node (ref "J2") (pin "32") (pinfunction "32_32") (pintype "passive"))
      (node (ref "U1") (pin "A21") (pinfunction "D5N_A21") (pintype "input"))
    )
    (net (code "138") (name "/JX1_D5_DAC1_P") (class "Default")
      (node (ref "J2") (pin "30") (pinfunction "30_30") (pintype "passive"))
      (node (ref "U1") (pin "B19") (pinfunction "D5P_B19") (pintype "input"))
    )
    (net (code "139") (name "/JX1_D6_DAC1_N") (class "Default")
      (node (ref "J2") (pin "38") (pinfunction "38_38") (pintype "passive"))
      (node (ref "U1") (pin "A20") (pinfunction "D6N_A20") (pintype "input"))
    )
    (net (code "140") (name "/JX1_D6_DAC1_P") (class "Default")
      (node (ref "J2") (pin "36") (pinfunction "36_36") (pintype "passive"))
      (node (ref "U1") (pin "B18") (pinfunction "D6P_B18") (pintype "input"))
    )
    (net (code "141") (name "/JX1_D7_DAC1_N") (class "Default")
      (node (ref "J2") (pin "44") (pinfunction "44_44") (pintype "passive"))
      (node (ref "U1") (pin "A19") (pinfunction "D7N_A19") (pintype "input"))
    )
    (net (code "142") (name "/JX1_D7_DAC1_P") (class "Default")
      (node (ref "J2") (pin "42") (pinfunction "42_42") (pintype "passive"))
      (node (ref "U1") (pin "B17") (pinfunction "D7P_B17") (pintype "input"))
    )
    (net (code "143") (name "/JX1_D8_DAC1_N") (class "Default")
      (node (ref "J2") (pin "64") (pinfunction "64_64") (pintype "passive"))
      (node (ref "U1") (pin "B14") (pinfunction "D8N_B14") (pintype "input"))
    )
    (net (code "144") (name "/JX1_D8_DAC1_P") (class "Default")
      (node (ref "J2") (pin "62") (pinfunction "62_62") (pintype "passive"))
      (node (ref "U1") (pin "A15") (pinfunction "D8P_A15") (pintype "input"))
    )
    (net (code "145") (name "/JX1_D9_DAC1_N") (class "Default")
      (node (ref "J2") (pin "70") (pinfunction "70_70") (pintype "passive"))
      (node (ref "U1") (pin "B13") (pinfunction "D9N_B13") (pintype "input"))
    )
    (net (code "146") (name "/JX1_D9_DAC1_P") (class "Default")
      (node (ref "J2") (pin "68") (pinfunction "68_68") (pintype "passive"))
      (node (ref "U1") (pin "A14") (pinfunction "D9P_A14") (pintype "input"))
    )
    (net (code "147") (name "/JX1_D10_DAC1_N") (class "Default")
      (node (ref "J2") (pin "76") (pinfunction "76_76") (pintype "passive"))
      (node (ref "U1") (pin "B12") (pinfunction "D10N_B12") (pintype "input"))
    )
    (net (code "148") (name "/JX1_D10_DAC1_P") (class "Default")
      (node (ref "J2") (pin "74") (pinfunction "74_74") (pintype "passive"))
      (node (ref "U1") (pin "A13") (pinfunction "D10P_A13") (pintype "input"))
    )
    (net (code "149") (name "/JX1_D11_DAC1_N") (class "Default")
      (node (ref "J2") (pin "84") (pinfunction "84_84") (pintype "passive"))
      (node (ref "U1") (pin "B11") (pinfunction "D11N_B11") (pintype "input"))
    )
    (net (code "150") (name "/JX1_D11_DAC1_P") (class "Default")
      (node (ref "J2") (pin "82") (pinfunction "82_82") (pintype "passive"))
      (node (ref "U1") (pin "A12") (pinfunction "D11P_A12") (pintype "input"))
    )
    (net (code "151") (name "/JX1_D12_DAC1_N") (class "Default")
      (node (ref "J2") (pin "90") (pinfunction "90_90") (pintype "passive"))
      (node (ref "U1") (pin "A11") (pinfunction "D12N_A11") (pintype "input"))
    )
    (net (code "152") (name "/JX1_D12_DAC1_P") (class "Default")
      (node (ref "J2") (pin "88") (pinfunction "88_88") (pintype "passive"))
      (node (ref "U1") (pin "B10") (pinfunction "D12P_B10") (pintype "input"))
    )
    (net (code "153") (name "/JX1_D13_DAC1_N") (class "Default")
      (node (ref "J2") (pin "75") (pinfunction "75_75") (pintype "passive"))
      (node (ref "U1") (pin "A10") (pinfunction "D13N_A10") (pintype "input"))
    )
    (net (code "154") (name "/JX1_D13_DAC1_P") (class "Default")
      (node (ref "J2") (pin "73") (pinfunction "73_73") (pintype "passive"))
      (node (ref "U1") (pin "B9") (pinfunction "D13P_B9") (pintype "input"))
    )
    (net (code "155") (name "/JX1_D14_DAC1_N") (class "Default")
      (node (ref "J2") (pin "83") (pinfunction "83_83") (pintype "passive"))
      (node (ref "U1") (pin "B8") (pinfunction "D14N_B8") (pintype "input"))
    )
    (net (code "156") (name "/JX1_D14_DAC1_P") (class "Default")
      (node (ref "J2") (pin "81") (pinfunction "81_81") (pintype "passive"))
      (node (ref "U1") (pin "A8") (pinfunction "D14P_A8") (pintype "input"))
    )
    (net (code "157") (name "/JX1_D15_DAC1_N") (class "Default")
      (node (ref "J2") (pin "89") (pinfunction "89_89") (pintype "passive"))
      (node (ref "U1") (pin "B7") (pinfunction "D15N_(MSB)_B7") (pintype "input"))
    )
    (net (code "158") (name "/JX1_D15_DAC1_P") (class "Default")
      (node (ref "J2") (pin "87") (pinfunction "87_87") (pintype "passive"))
      (node (ref "U1") (pin "A7") (pinfunction "D15P_(MSB)_A7") (pintype "input"))
    )
    (net (code "159") (name "/JX1_DACCLK_DAC1_IN_N") (class "Default")
      (node (ref "C323") (pin "1") (pinfunction "1_1") (pintype "passive"))
      (node (ref "R121") (pin "1") (pinfunction "1_1") (pintype "passive"))
      (node (ref "U1") (pin "B3") (pinfunction "DACCLKN_B3") (pintype "input"))
    )
    (net (code "160") (name "/JX1_DACCLK_DAC1_IN_P") (class "Default")
      (node (ref "C322") (pin "1") (pinfunction "1_1") (pintype "passive"))
      (node (ref "R121") (pin "2") (pinfunction "2_2") (pintype "passive"))
      (node (ref "U1") (pin "A3") (pinfunction "DACCLKP_A3") (pintype "input"))
    )
    (net (code "161") (name "/JX1_DACCLK_DAC1_N") (class "Default")
      (node (ref "C323") (pin "2") (pinfunction "2_2") (pintype "passive"))
    )
    (net (code "162") (name "/JX1_DACCLK_DAC1_P") (class "Default")
      (node (ref "C322") (pin "2") (pinfunction "2_2") (pintype "passive"))
    )
    (net (code "163") (name "/JX1_DATACLK_DAC1_N") (class "Default")
      (node (ref "J2") (pin "56") (pinfunction "56_56") (pintype "passive"))
      (node (ref "U1") (pin "B15") (pinfunction "DATACLKN_B15") (pintype "input"))
    )
    (net (code "164") (name "/JX1_DATACLK_DAC1_P") (class "Default")
      (node (ref "J2") (pin "54") (pinfunction "54_54") (pintype "passive"))
      (node (ref "U1") (pin "A16") (pinfunction "DATACLKP_A16") (pintype "input"))
    )
    (net (code "165") (name "/JX1_LVDS9_N") (class "Default")
      (node (ref "J1") (pin "38") (pinfunction "38_38") (pintype "passive"))
      (node (ref "R128") (pin "1") (pinfunction "1_1") (pintype "passive"))
    )
    (net (code "166") (name "/JX1_LVDS9_P") (class "Default")
      (node (ref "J1") (pin "36") (pinfunction "36_36") (pintype "passive"))
      (node (ref "R127") (pin "1") (pinfunction "1_1") (pintype "passive"))
    )
    (net (code "167") (name "/JX2_D0_DAC2_N") (class "Default")
      (node (ref "J1") (pin "84") (pinfunction "84_84") (pintype "passive"))
      (node (ref "U6") (pin "A27") (pinfunction "D0N_(LSB)_A27") (pintype "input"))
    )
    (net (code "168") (name "/JX2_D0_DAC2_P") (class "Default")
      (node (ref "J1") (pin "82") (pinfunction "82_82") (pintype "passive"))
      (node (ref "U6") (pin "B24") (pinfunction "D0P_(LSB)_B24") (pintype "input"))
    )
    (net (code "169") (name "/JX2_D1_DAC2_N") (class "Default")
      (node (ref "J1") (pin "76") (pinfunction "76_76") (pintype "passive"))
      (node (ref "U6") (pin "A26") (pinfunction "D1N_A26") (pintype "input"))
    )
    (net (code "170") (name "/JX2_D1_DAC2_P") (class "Default")
      (node (ref "J1") (pin "74") (pinfunction "74_74") (pintype "passive"))
      (node (ref "U6") (pin "B23") (pinfunction "D1P_B23") (pintype "input"))
    )
    (net (code "171") (name "/JX2_D2_DAC2_N") (class "Default")
      (node (ref "J1") (pin "70") (pinfunction "70_70") (pintype "passive"))
      (node (ref "U6") (pin "B22") (pinfunction "D2N_B22") (pintype "input"))
    )
    (net (code "172") (name "/JX2_D2_DAC2_P") (class "Default")
      (node (ref "J1") (pin "68") (pinfunction "68_68") (pintype "passive"))
      (node (ref "U6") (pin "A24") (pinfunction "D2P_A24") (pintype "input"))
    )
    (net (code "173") (name "/JX2_D3_DAC2_N") (class "Default")
      (node (ref "J1") (pin "83") (pinfunction "83_83") (pintype "passive"))
      (node (ref "U6") (pin "B21") (pinfunction "D3N_B21") (pintype "input"))
    )
    (net (code "174") (name "/JX2_D3_DAC2_P") (class "Default")
      (node (ref "J1") (pin "81") (pinfunction "81_81") (pintype "passive"))
      (node (ref "U6") (pin "A23") (pinfunction "D3P_A23") (pintype "input"))
    )
    (net (code "175") (name "/JX2_D4_DAC2_N") (class "Default")
      (node (ref "J1") (pin "75") (pinfunction "75_75") (pintype "passive"))
      (node (ref "U6") (pin "A22") (pinfunction "D4N_A22") (pintype "input"))
    )
    (net (code "176") (name "/JX2_D4_DAC2_P") (class "Default")
      (node (ref "J1") (pin "73") (pinfunction "73_73") (pintype "passive"))
      (node (ref "U6") (pin "B20") (pinfunction "D4P_B20") (pintype "input"))
    )
    (net (code "177") (name "/JX2_D5_DAC2_N") (class "Default")
      (node (ref "J1") (pin "69") (pinfunction "69_69") (pintype "passive"))
      (node (ref "U6") (pin "A21") (pinfunction "D5N_A21") (pintype "input"))
    )
    (net (code "178") (name "/JX2_D5_DAC2_P") (class "Default")
      (node (ref "J1") (pin "67") (pinfunction "67_67") (pintype "passive"))
      (node (ref "U6") (pin "B19") (pinfunction "D5P_B19") (pintype "input"))
    )
    (net (code "179") (name "/JX2_D6_DAC2_N") (class "Default")
      (node (ref "J1") (pin "63") (pinfunction "63_63") (pintype "passive"))
      (node (ref "U6") (pin "A20") (pinfunction "D6N_A20") (pintype "input"))
    )
    (net (code "180") (name "/JX2_D6_DAC2_P") (class "Default")
      (node (ref "J1") (pin "61") (pinfunction "61_61") (pintype "passive"))
      (node (ref "U6") (pin "B18") (pinfunction "D6P_B18") (pintype "input"))
    )
    (net (code "181") (name "/JX2_D7_DAC2_N") (class "Default")
      (node (ref "J1") (pin "55") (pinfunction "55_55") (pintype "passive"))
      (node (ref "U6") (pin "A19") (pinfunction "D7N_A19") (pintype "input"))
    )
    (net (code "182") (name "/JX2_D7_DAC2_P") (class "Default")
      (node (ref "J1") (pin "53") (pinfunction "53_53") (pintype "passive"))
      (node (ref "U6") (pin "B17") (pinfunction "D7P_B17") (pintype "input"))
    )
    (net (code "183") (name "/JX2_D8_DAC2_N") (class "Default")
      (node (ref "J1") (pin "37") (pinfunction "37_37") (pintype "passive"))
      (node (ref "U6") (pin "B14") (pinfunction "D8N_B14") (pintype "input"))
    )
    (net (code "184") (name "/JX2_D8_DAC2_P") (class "Default")
      (node (ref "J1") (pin "35") (pinfunction "35_35") (pintype "passive"))
      (node (ref "U6") (pin "A15") (pinfunction "D8P_A15") (pintype "input"))
    )
    (net (code "185") (name "/JX2_D9_DAC2_N") (class "Default")
      (node (ref "J1") (pin "31") (pinfunction "31_31") (pintype "passive"))
      (node (ref "U6") (pin "B13") (pinfunction "D9N_B13") (pintype "input"))
    )
    (net (code "186") (name "/JX2_D9_DAC2_P") (class "Default")
      (node (ref "J1") (pin "29") (pinfunction "29_29") (pintype "passive"))
      (node (ref "U6") (pin "A14") (pinfunction "D9P_A14") (pintype "input"))
    )
    (net (code "187") (name "/JX2_D10_DAC2_N") (class "Default")
      (node (ref "J1") (pin "25") (pinfunction "25_25") (pintype "passive"))
      (node (ref "U6") (pin "B12") (pinfunction "D10N_B12") (pintype "input"))
    )
    (net (code "188") (name "/JX2_D10_DAC2_P") (class "Default")
      (node (ref "J1") (pin "23") (pinfunction "23_23") (pintype "passive"))
      (node (ref "U6") (pin "A13") (pinfunction "D10P_A13") (pintype "input"))
    )
    (net (code "189") (name "/JX2_D11_DAC2_N") (class "Default")
      (node (ref "J1") (pin "19") (pinfunction "19_19") (pintype "passive"))
      (node (ref "U6") (pin "B11") (pinfunction "D11N_B11") (pintype "input"))
    )
    (net (code "190") (name "/JX2_D11_DAC2_P") (class "Default")
      (node (ref "J1") (pin "17") (pinfunction "17_17") (pintype "passive"))
      (node (ref "U6") (pin "A12") (pinfunction "D11P_A12") (pintype "input"))
    )
    (net (code "191") (name "/JX2_D12_DAC2_N") (class "Default")
      (node (ref "J1") (pin "13") (pinfunction "13_13") (pintype "passive"))
      (node (ref "U6") (pin "A11") (pinfunction "D12N_A11") (pintype "input"))
    )
    (net (code "192") (name "/JX2_D12_DAC2_P") (class "Default")
      (node (ref "J1") (pin "11") (pinfunction "11_11") (pintype "passive"))
      (node (ref "U6") (pin "B10") (pinfunction "D12P_B10") (pintype "input"))
    )
    (net (code "193") (name "/JX2_D13_DAC2_N") (class "Default")
      (node (ref "J1") (pin "26") (pinfunction "26_26") (pintype "passive"))
      (node (ref "U6") (pin "A10") (pinfunction "D13N_A10") (pintype "input"))
    )
    (net (code "194") (name "/JX2_D13_DAC2_P") (class "Default")
      (node (ref "J1") (pin "24") (pinfunction "24_24") (pintype "passive"))
      (node (ref "U6") (pin "B9") (pinfunction "D13P_B9") (pintype "input"))
    )
    (net (code "195") (name "/JX2_D14_DAC2_N") (class "Default")
      (node (ref "J1") (pin "20") (pinfunction "20_20") (pintype "passive"))
      (node (ref "U6") (pin "B8") (pinfunction "D14N_B8") (pintype "input"))
    )
    (net (code "196") (name "/JX2_D14_DAC2_P") (class "Default")
      (node (ref "J1") (pin "18") (pinfunction "18_18") (pintype "passive"))
      (node (ref "U6") (pin "A8") (pinfunction "D14P_A8") (pintype "input"))
    )
    (net (code "197") (name "/JX2_D15_DAC2_N") (class "Default")
      (node (ref "J1") (pin "14") (pinfunction "14_14") (pintype "passive"))
      (node (ref "U6") (pin "B7") (pinfunction "D15N_(MSB)_B7") (pintype "input"))
    )
    (net (code "198") (name "/JX2_D15_DAC2_P") (class "Default")
      (node (ref "J1") (pin "12") (pinfunction "12_12") (pintype "passive"))
      (node (ref "U6") (pin "A7") (pinfunction "D15P_(MSB)_A7") (pintype "input"))
    )
    (net (code "199") (name "/JX2_DACCLK_DAC2_IN_N") (class "Default")
      (node (ref "C319") (pin "1") (pinfunction "1_1") (pintype "passive"))
      (node (ref "R111") (pin "1") (pinfunction "1_1") (pintype "passive"))
      (node (ref "U6") (pin "B3") (pinfunction "DACCLKN_B3") (pintype "input"))
    )
    (net (code "200") (name "/JX2_DACCLK_DAC2_IN_P") (class "Default")
      (node (ref "C318") (pin "1") (pinfunction "1_1") (pintype "passive"))
      (node (ref "R111") (pin "2") (pinfunction "2_2") (pintype "passive"))
      (node (ref "U6") (pin "A3") (pinfunction "DACCLKP_A3") (pintype "input"))
    )
    (net (code "201") (name "/JX2_DACCLK_DAC2_N") (class "Default")
      (node (ref "C319") (pin "2") (pinfunction "2_2") (pintype "passive"))
    )
    (net (code "202") (name "/JX2_DACCLK_DAC2_P") (class "Default")
      (node (ref "C318") (pin "2") (pinfunction "2_2") (pintype "passive"))
    )
    (net (code "203") (name "/JX2_DATACLK_DAC2_N") (class "Default")
      (node (ref "J1") (pin "43") (pinfunction "43_43") (pintype "passive"))
      (node (ref "U6") (pin "B15") (pinfunction "DATACLKN_B15") (pintype "input"))
    )
    (net (code "204") (name "/JX2_DATACLK_DAC2_P") (class "Default")
      (node (ref "J1") (pin "41") (pinfunction "41_41") (pintype "passive"))
      (node (ref "U6") (pin "A16") (pinfunction "DATACLKP_A16") (pintype "input"))
    )
    (net (code "205") (name "/OR_OUT_N") (class "Default")
      (node (ref "RN3") (pin "4") (pinfunction "4_4") (pintype "passive"))
      (node (ref "U7") (pin "42") (pinfunction "OR-_42") (pintype "output"))
    )
    (net (code "206") (name "/OR_OUT_P") (class "Default")
      (node (ref "RN3") (pin "3") (pinfunction "3_3") (pintype "passive"))
      (node (ref "U7") (pin "43") (pinfunction "OR+_43") (pintype "output"))
    )
    (net (code "207") (name "/OSTR_DAC1_BUF_IN_N") (class "Default")
      (node (ref "C321") (pin "1") (pinfunction "1_1") (pintype "passive"))
      (node (ref "R120") (pin "1") (pinfunction "1_1") (pintype "passive"))
      (node (ref "U1") (pin "B2") (pinfunction "OSTRN_B2") (pintype "input"))
    )
    (net (code "208") (name "/OSTR_DAC1_BUF_IN_P") (class "Default")
      (node (ref "C320") (pin "1") (pinfunction "1_1") (pintype "passive"))
      (node (ref "R120") (pin "2") (pinfunction "2_2") (pintype "passive"))
      (node (ref "U1") (pin "A2") (pinfunction "OSTRP_A2") (pintype "input"))
    )
    (net (code "209") (name "/OSTR_DAC1_BUF_N") (class "Default")
      (node (ref "C321") (pin "2") (pinfunction "2_2") (pintype "passive"))
    )
    (net (code "210") (name "/OSTR_DAC1_BUF_P") (class "Default")
      (node (ref "C320") (pin "2") (pinfunction "2_2") (pintype "passive"))
    )
    (net (code "211") (name "/OSTR_DAC2_BUF_IN_N") (class "Default")
      (node (ref "C317") (pin "1") (pinfunction "1_1") (pintype "passive"))
      (node (ref "R83") (pin "1") (pinfunction "1_1") (pintype "passive"))
      (node (ref "U6") (pin "B2") (pinfunction "OSTRN_B2") (pintype "input"))
    )
    (net (code "212") (name "/OSTR_DAC2_BUF_IN_P") (class "Default")
      (node (ref "C316") (pin "1") (pinfunction "1_1") (pintype "passive"))
      (node (ref "R83") (pin "2") (pinfunction "2_2") (pintype "passive"))
      (node (ref "U6") (pin "A2") (pinfunction "OSTRP_A2") (pintype "input"))
    )
    (net (code "213") (name "/OSTR_DAC2_BUF_N") (class "Default")
      (node (ref "C317") (pin "2") (pinfunction "2_2") (pintype "passive"))
    )
    (net (code "214") (name "/OSTR_DAC2_BUF_P") (class "Default")
      (node (ref "C316") (pin "2") (pinfunction "2_2") (pintype "passive"))
    )
    (net (code "215") (name "/OUT_SYNC_N") (class "Default")
      (node (ref "J16") (pin "1") (pinfunction "1_1") (pintype "passive"))
      (node (ref "R104") (pin "1") (pinfunction "1_1") (pintype "passive"))
      (node (ref "U30") (pin "7") (pinfunction "OUT-_7") (pintype "output"))
    )
    (net (code "216") (name "/OUT_SYNC_P") (class "Default")
      (node (ref "J15") (pin "1") (pinfunction "1_1") (pintype "passive"))
      (node (ref "R104") (pin "2") (pinfunction "2_2") (pintype "passive"))
      (node (ref "U30") (pin "6") (pinfunction "OUT+_6") (pintype "output"))
    )
    (net (code "217") (name "/PLL_AVDD_DAC1") (class "Default")
      (node (ref "C218") (pin "1") (pinfunction "1_1") (pintype "passive"))
      (node (ref "C219") (pin "1") (pinfunction "1_1") (pintype "passive"))
      (node (ref "FB11") (pin "2") (pinfunction "2_2") (pintype "passive"))
      (node (ref "U1") (pin "B1") (pinfunction "PLLAVDD_B1") (pintype "power_in"))
    )
    (net (code "218") (name "/PLL_AVDD_DAC2") (class "Default")
      (node (ref "C239") (pin "1") (pinfunction "1_1") (pintype "passive"))
      (node (ref "C240") (pin "1") (pinfunction "1_1") (pintype "passive"))
      (node (ref "FB18") (pin "2") (pinfunction "2_2") (pintype "passive"))
      (node (ref "U6") (pin "B1") (pinfunction "PLLAVDD_B1") (pintype "power_in"))
    )
    (net (code "219") (name "/SDO") (class "Default")
      (node (ref "J2") (pin "2") (pinfunction "2_2") (pintype "passive"))
      (node (ref "R152") (pin "1") (pinfunction "1_1") (pintype "passive"))
      (node (ref "U1") (pin "B27") (pinfunction "SDO_B27") (pintype "tri_state"))
      (node (ref "U6") (pin "B27") (pinfunction "SDO_B27") (pintype "tri_state"))
    )
    (net (code "220") (name "/SPI_CLK") (class "Default")
      (node (ref "J2") (pin "4") (pinfunction "4_4") (pintype "passive"))
      (node (ref "R151") (pin "2") (pinfunction "2_2") (pintype "passive"))
      (node (ref "U1") (pin "A31") (pinfunction "SCLK_A31") (pintype "input"))
      (node (ref "U6") (pin "A31") (pinfunction "SCLK_A31") (pintype "input"))
      (node (ref "U7") (pin "45") (pinfunction "SCLK_45") (pintype "input"))
    )
    (net (code "221") (name "/SPI_LE") (class "Default")
      (node (ref "J2") (pin "8") (pinfunction "8_8") (pintype "passive"))
    )
    (net (code "222") (name "/SYNC_DAC1_BUF_N") (class "Default")
      (node (ref "R101") (pin "1") (pinfunction "1_1") (pintype "passive"))
      (node (ref "U1") (pin "B5") (pinfunction "SYNCN_B5") (pintype "input"))
      (node (ref "U30") (pin "2") (pinfunction "IN-_2") (pintype "input"))
      (node (ref "U5") (pin "10") (pinfunction "OUT1-_10") (pintype "passive"))
    )
    (net (code "223") (name "/SYNC_DAC1_BUF_P") (class "Default")
      (node (ref "R101") (pin "2") (pinfunction "2_2") (pintype "passive"))
      (node (ref "U1") (pin "A5") (pinfunction "SYNCP_A5") (pintype "input"))
      (node (ref "U30") (pin "3") (pinfunction "IN+_3") (pintype "input"))
      (node (ref "U5") (pin "11") (pinfunction "OUT1+_11") (pintype "passive"))
    )
    (net (code "224") (name "/SYNC_DAC2_BUF_N") (class "Default")
      (node (ref "R103") (pin "1") (pinfunction "1_1") (pintype "passive"))
      (node (ref "U5") (pin "9") (pinfunction "OUT2-_9") (pintype "passive"))
      (node (ref "U6") (pin "B5") (pinfunction "SYNCN_B5") (pintype "input"))
    )
    (net (code "225") (name "/SYNC_DAC2_BUF_P") (class "Default")
      (node (ref "R103") (pin "2") (pinfunction "2_2") (pintype "passive"))
      (node (ref "U5") (pin "8") (pinfunction "OUT2+_8") (pintype "passive"))
      (node (ref "U6") (pin "A5") (pinfunction "SYNCP_A5") (pintype "input"))
    )
    (net (code "226") (name "/SYNC_DAC_C_N") (class "Default")
      (node (ref "C284") (pin "2") (pinfunction "2_2") (pintype "passive"))
      (node (ref "U5") (pin "4") (pinfunction "IN-_4") (pintype "tri_state"))
    )
    (net (code "227") (name "/SYNC_DAC_C_P") (class "Default")
      (node (ref "C283") (pin "2") (pinfunction "2_2") (pintype "passive"))
      (node (ref "U5") (pin "3") (pinfunction "IN+_3") (pintype "tri_state"))
    )
    (net (code "228") (name "/SYNC_DAC_N") (class "Default")
      (node (ref "C284") (pin "1") (pinfunction "1_1") (pintype "passive"))
      (node (ref "R100") (pin "2") (pinfunction "2_2") (pintype "passive"))
      (node (ref "R102") (pin "1") (pinfunction "1_1") (pintype "passive"))
      (node (ref "R128") (pin "2") (pinfunction "2_2") (pintype "passive"))
    )
    (net (code "229") (name "/SYNC_DAC_P") (class "Default")
      (node (ref "C283") (pin "1") (pinfunction "1_1") (pintype "passive"))
      (node (ref "R102") (pin "2") (pinfunction "2_2") (pintype "passive"))
      (node (ref "R127") (pin "2") (pinfunction "2_2") (pintype "passive"))
      (node (ref "R99") (pin "2") (pinfunction "2_2") (pintype "passive"))
    )
    (net (code "230") (name "/V+U5") (class "Default")
      (node (ref "C277") (pin "1") (pinfunction "1_1") (pintype "passive"))
      (node (ref "C278") (pin "1") (pinfunction "1_1") (pintype "passive"))
      (node (ref "C279") (pin "1") (pinfunction "1_1") (pintype "passive"))
      (node (ref "C280") (pin "1") (pinfunction "1_1") (pintype "passive"))
      (node (ref "FB22") (pin "2") (pinfunction "2_2") (pintype "passive"))
      (node (ref "U5") (pin "2") (pinfunction "V+_2") (pintype "power_in"))
    )
    (net (code "231") (name "/VCCO_13") (class "Default")
      (node (ref "J2") (pin "98") (pinfunction "98_98") (pintype "passive"))
    )
    (net (code "232") (name "/VCCO_34") (class "Default")
      (node (ref "J1") (pin "78") (pinfunction "78_78") (pintype "passive"))
      (node (ref "J1") (pin "79") (pinfunction "79_79") (pintype "passive"))
      (node (ref "J1") (pin "80") (pinfunction "80_80") (pintype "passive"))
      (node (ref "J2") (pin "78") (pinfunction "78_78") (pintype "passive"))
      (node (ref "J2") (pin "79") (pinfunction "79_79") (pintype "passive"))
      (node (ref "J2") (pin "80") (pinfunction "80_80") (pintype "passive"))
    )
    (net (code "233") (name "/VCC_DS") (class "Default")
      (node (ref "C285") (pin "1") (pinfunction "1_1") (pintype "passive"))
      (node (ref "C286") (pin "1") (pinfunction "1_1") (pintype "passive"))
      (node (ref "C287") (pin "1") (pinfunction "1_1") (pintype "passive"))
      (node (ref "C288") (pin "1") (pinfunction "1_1") (pintype "passive"))
      (node (ref "FB23") (pin "2") (pinfunction "2_2") (pintype "passive"))
      (node (ref "U30") (pin "5") (pinfunction "VCC_5") (pintype "power_in"))
      (node (ref "U30") (pin "8") (pinfunction "EN_8") (pintype "input"))
    )
    (net (code "234") (name "/VIN_A_N") (class "Default")
      (node (ref "R47") (pin "2") (pinfunction "2_2") (pintype "passive"))
      (node (ref "U7") (pin "52") (pinfunction "VIN-A_52") (pintype "input"))
    )
    (net (code "235") (name "/VIN_A_P") (class "Default")
      (node (ref "R45") (pin "2") (pinfunction "2_2") (pintype "passive"))
      (node (ref "U7") (pin "51") (pinfunction "VIN+A_51") (pintype "input"))
    )
    (net (code "236") (name "/VIN_B_N") (class "Default")
      (node (ref "R131") (pin "2") (pinfunction "2_2") (pintype "passive"))
      (node (ref "U7") (pin "61") (pinfunction "VIN-B_61") (pintype "input"))
    )
    (net (code "237") (name "/VIN_B_P") (class "Default")
      (node (ref "R129") (pin "2") (pinfunction "2_2") (pintype "passive"))
      (node (ref "U7") (pin "62") (pinfunction "VIN+B_62") (pintype "input"))
    )
    (net (code "238") (name "/VIN_HDR") (class "Default")
      (node (ref "J1") (pin "57") (pinfunction "57_57") (pintype "passive"))
      (node (ref "J1") (pin "58") (pinfunction "58_58") (pintype "passive"))
      (node (ref "J1") (pin "59") (pinfunction "59_59") (pintype "passive"))
      (node (ref "J1") (pin "60") (pinfunction "60_60") (pintype "passive"))
      (node (ref "J2") (pin "12") (pinfunction "12_12") (pintype "passive"))
      (node (ref "J2") (pin "57") (pinfunction "57_57") (pintype "passive"))
      (node (ref "J2") (pin "58") (pinfunction "58_58") (pintype "passive"))
      (node (ref "J2") (pin "59") (pinfunction "59_59") (pintype "passive"))
      (node (ref "J2") (pin "60") (pinfunction "60_60") (pintype "passive"))
    )
    (net (code "239") (name "/VOCM_1") (class "Default")
      (node (ref "C260") (pin "1") (pinfunction "1_1") (pintype "passive"))
      (node (ref "C263") (pin "1") (pinfunction "1_1") (pintype "passive"))
      (node (ref "R147") (pin "2") (pinfunction "2_2") (pintype "passive"))
      (node (ref "U3") (pin "11") (pinfunction "VOCM2_11") (pintype "passive"))
      (node (ref "U3") (pin "17") (pinfunction "VOCM1_17") (pintype "passive"))
    )
    (net (code "240") (name "/VXP0_N") (class "Default")
      (node (ref "J1") (pin "99") (pinfunction "99_99") (pintype "passive"))
      (node (ref "P10") (pin "4") (pinfunction "4_4") (pintype "passive"))
    )
    (net (code "241") (name "/VXP0_P") (class "Default")
      (node (ref "J1") (pin "97") (pinfunction "97_97") (pintype "passive"))
      (node (ref "P10") (pin "3") (pinfunction "3_3") (pintype "passive"))
    )
    (net (code "242") (name "GND") (class "Default")
      (node (ref "C1") (pin "1") (pinfunction "1_1") (pintype "passive"))
      (node (ref "C10") (pin "1") (pinfunction "1_1") (pintype "passive"))
      (node (ref "C11") (pin "1") (pinfunction "1_1") (pintype "passive"))
      (node (ref "C145") (pin "1") (pinfunction "1_1") (pintype "passive"))
      (node (ref "C146") (pin "1") (pinfunction "1_1") (pintype "passive"))
      (node (ref "C147") (pin "1") (pinfunction "1_1") (pintype "passive"))
      (node (ref "C148") (pin "1") (pinfunction "1_1") (pintype "passive"))
      (node (ref "C149") (pin "1") (pinfunction "1_1") (pintype "passive"))
      (node (ref "C150") (pin "1") (pinfunction "1_1") (pintype "passive"))
      (node (ref "C154") (pin "1") (pinfunction "1_1") (pintype "passive"))
      (node (ref "C155") (pin "1") (pinfunction "1_1") (pintype "passive"))
      (node (ref "C156") (pin "1") (pinfunction "1_1") (pintype "passive"))
      (node (ref "C157") (pin "1") (pinfunction "1_1") (pintype "passive"))
      (node (ref "C158") (pin "1") (pinfunction "1_1") (pintype "passive"))
      (node (ref "C159") (pin "1") (pinfunction "1_1") (pintype "passive"))
      (node (ref "C163") (pin "1") (pinfunction "1_1") (pintype "passive"))
      (node (ref "C164") (pin "1") (pinfunction "1_1") (pintype "passive"))
      (node (ref "C165") (pin "1") (pinfunction "1_1") (pintype "passive"))
      (node (ref "C166") (pin "1") (pinfunction "1_1") (pintype "passive"))
      (node (ref "C167") (pin "1") (pinfunction "1_1") (pintype "passive"))
      (node (ref "C168") (pin "1") (pinfunction "1_1") (pintype "passive"))
      (node (ref "C172") (pin "1") (pinfunction "1_1") (pintype "passive"))
      (node (ref "C173") (pin "1") (pinfunction "1_1") (pintype "passive"))
      (node (ref "C174") (pin "1") (pinfunction "1_1") (pintype "passive"))
      (node (ref "C175") (pin "1") (pinfunction "1_1") (pintype "passive"))
      (node (ref "C176") (pin "1") (pinfunction "1_1") (pintype "passive"))
      (node (ref "C177") (pin "1") (pinfunction "1_1") (pintype "passive"))
      (node (ref "C181") (pin "1") (pinfunction "1_1") (pintype "passive"))
      (node (ref "C182") (pin "1") (pinfunction "1_1") (pintype "passive"))
      (node (ref "C183") (pin "1") (pinfunction "1_1") (pintype "passive"))
      (node (ref "C184") (pin "1") (pinfunction "1_1") (pintype "passive"))
      (node (ref "C185") (pin "1") (pinfunction "1_1") (pintype "passive"))
      (node (ref "C186") (pin "1") (pinfunction "1_1") (pintype "passive"))
      (node (ref "C19") (pin "1") (pinfunction "1_1") (pintype "passive"))
      (node (ref "C190") (pin "1") (pinfunction "1_1") (pintype "passive"))
      (node (ref "C191") (pin "1") (pinfunction "1_1") (pintype "passive"))
      (node (ref "C192") (pin "1") (pinfunction "1_1") (pintype "passive"))
      (node (ref "C193") (pin "1") (pinfunction "1_1") (pintype "passive"))
      (node (ref "C194") (pin "1") (pinfunction "1_1") (pintype "passive"))
      (node (ref "C195") (pin "1") (pinfunction "1_1") (pintype "passive"))
      (node (ref "C199") (pin "1") (pinfunction "1_1") (pintype "passive"))
      (node (ref "C2") (pin "1") (pinfunction "1_1") (pintype "passive"))
      (node (ref "C200") (pin "1") (pinfunction "1_1") (pintype "passive"))
      (node (ref "C201") (pin "1") (pinfunction "1_1") (pintype "passive"))
      (node (ref "C202") (pin "2") (pinfunction "2_2") (pintype "passive"))
      (node (ref "C203") (pin "2") (pinfunction "2_2") (pintype "passive"))
      (node (ref "C204") (pin "2") (pinfunction "2_2") (pintype "passive"))
      (node (ref "C205") (pin "2") (pinfunction "2_2") (pintype "passive"))
      (node (ref "C206") (pin "2") (pinfunction "2_2") (pintype "passive"))
      (node (ref "C207") (pin "2") (pinfunction "2_2") (pintype "passive"))
      (node (ref "C208") (pin "2") (pinfunction "2_2") (pintype "passive"))
      (node (ref "C209") (pin "2") (pinfunction "2_2") (pintype "passive"))
      (node (ref "C210") (pin "2") (pinfunction "2_2") (pintype "passive"))
      (node (ref "C211") (pin "2") (pinfunction "2_2") (pintype "passive"))
      (node (ref "C212") (pin "2") (pinfunction "2_2") (pintype "passive"))
      (node (ref "C213") (pin "2") (pinfunction "2_2") (pintype "passive"))
      (node (ref "C214") (pin "2") (pinfunction "2_2") (pintype "passive"))
      (node (ref "C215") (pin "2") (pinfunction "2_2") (pintype "passive"))
      (node (ref "C216") (pin "2") (pinfunction "2_2") (pintype "passive"))
      (node (ref "C217") (pin "2") (pinfunction "2_2") (pintype "passive"))
      (node (ref "C218") (pin "2") (pinfunction "2_2") (pintype "passive"))
      (node (ref "C219") (pin "2") (pinfunction "2_2") (pintype "passive"))
      (node (ref "C220") (pin "2") (pinfunction "2_2") (pintype "passive"))
      (node (ref "C221") (pin "2") (pinfunction "2_2") (pintype "passive"))
      (node (ref "C222") (pin "2") (pinfunction "2_2") (pintype "passive"))
      (node (ref "C223") (pin "2") (pinfunction "2_2") (pintype "passive"))
      (node (ref "C224") (pin "2") (pinfunction "2_2") (pintype "passive"))
      (node (ref "C225") (pin "2") (pinfunction "2_2") (pintype "passive"))
      (node (ref "C226") (pin "2") (pinfunction "2_2") (pintype "passive"))
      (node (ref "C227") (pin "2") (pinfunction "2_2") (pintype "passive"))
      (node (ref "C228") (pin "2") (pinfunction "2_2") (pintype "passive"))
      (node (ref "C229") (pin "2") (pinfunction "2_2") (pintype "passive"))
      (node (ref "C230") (pin "2") (pinfunction "2_2") (pintype "passive"))
      (node (ref "C231") (pin "2") (pinfunction "2_2") (pintype "passive"))
      (node (ref "C232") (pin "2") (pinfunction "2_2") (pintype "passive"))
      (node (ref "C233") (pin "2") (pinfunction "2_2") (pintype "passive"))
      (node (ref "C234") (pin "2") (pinfunction "2_2") (pintype "passive"))
      (node (ref "C235") (pin "2") (pinfunction "2_2") (pintype "passive"))
      (node (ref "C236") (pin "2") (pinfunction "2_2") (pintype "passive"))
      (node (ref "C237") (pin "2") (pinfunction "2_2") (pintype "passive"))
      (node (ref "C238") (pin "2") (pinfunction "2_2") (pintype "passive"))
      (node (ref "C239") (pin "2") (pinfunction "2_2") (pintype "passive"))
      (node (ref "C240") (pin "2") (pinfunction "2_2") (pintype "passive"))
      (node (ref "C241") (pin "2") (pinfunction "2_2") (pintype "passive"))
      (node (ref "C242") (pin "2") (pinfunction "2_2") (pintype "passive"))
      (node (ref "C243") (pin "2") (pinfunction "2_2") (pintype "passive"))
      (node (ref "C244") (pin "2") (pinfunction "2_2") (pintype "passive"))
      (node (ref "C245") (pin "2") (pinfunction "2_2") (pintype "passive"))
      (node (ref "C246") (pin "2") (pinfunction "2_2") (pintype "passive"))
      (node (ref "C247") (pin "2") (pinfunction "2_2") (pintype "passive"))
      (node (ref "C248") (pin "2") (pinfunction "2_2") (pintype "passive"))
      (node (ref "C249") (pin "2") (pinfunction "2_2") (pintype "passive"))
      (node (ref "C250") (pin "2") (pinfunction "2_2") (pintype "passive"))
      (node (ref "C251") (pin "2") (pinfunction "2_2") (pintype "passive"))
      (node (ref "C252") (pin "2") (pinfunction "2_2") (pintype "passive"))
      (node (ref "C253") (pin "2") (pinfunction "2_2") (pintype "passive"))
      (node (ref "C254") (pin "2") (pinfunction "2_2") (pintype "passive"))
      (node (ref "C255") (pin "2") (pinfunction "2_2") (pintype "passive"))
      (node (ref "C256") (pin "2") (pinfunction "2_2") (pintype "passive"))
      (node (ref "C257") (pin "2") (pinfunction "2_2") (pintype "passive"))
      (node (ref "C258") (pin "2") (pinfunction "2_2") (pintype "passive"))
      (node (ref "C259") (pin "2") (pinfunction "2_2") (pintype "passive"))
      (node (ref "C260") (pin "2") (pinfunction "2_2") (pintype "passive"))
      (node (ref "C261") (pin "2") (pinfunction "2_2") (pintype "passive"))
      (node (ref "C263") (pin "2") (pinfunction "2_2") (pintype "passive"))
      (node (ref "C264") (pin "2") (pinfunction "2_2") (pintype "passive"))
      (node (ref "C277") (pin "2") (pinfunction "2_2") (pintype "passive"))
      (node (ref "C278") (pin "2") (pinfunction "2_2") (pintype "passive"))
      (node (ref "C279") (pin "2") (pinfunction "2_2") (pintype "passive"))
      (node (ref "C280") (pin "2") (pinfunction "2_2") (pintype "passive"))
      (node (ref "C285") (pin "2") (pinfunction "2_2") (pintype "passive"))
      (node (ref "C286") (pin "2") (pinfunction "2_2") (pintype "passive"))
      (node (ref "C287") (pin "2") (pinfunction "2_2") (pintype "passive"))
      (node (ref "C288") (pin "2") (pinfunction "2_2") (pintype "passive"))
      (node (ref "C3") (pin "1") (pinfunction "1_1") (pintype "passive"))
      (node (ref "C4") (pin "1") (pinfunction "1_1") (pintype "passive"))
      (node (ref "C5") (pin "1") (pinfunction "1_1") (pintype "passive"))
      (node (ref "C6") (pin "1") (pinfunction "1_1") (pintype "passive"))
      (node (ref "C78") (pin "2") (pinfunction "2_2") (pintype "passive"))
      (node (ref "C80") (pin "2") (pinfunction "2_2") (pintype "passive"))
      (node (ref "C81") (pin "2") (pinfunction "2_2") (pintype "passive"))
      (node (ref "J1") (pin "15") (pinfunction "15_15") (pintype "passive"))
      (node (ref "J1") (pin "16") (pinfunction "16_16") (pintype "passive"))
      (node (ref "J1") (pin "21") (pinfunction "21_21") (pintype "passive"))
      (node (ref "J1") (pin "22") (pinfunction "22_22") (pintype "passive"))
      (node (ref "J1") (pin "27") (pinfunction "27_27") (pintype "passive"))
      (node (ref "J1") (pin "28") (pinfunction "28_28") (pintype "passive"))
      (node (ref "J1") (pin "33") (pinfunction "33_33") (pintype "passive"))
      (node (ref "J1") (pin "34") (pinfunction "34_34") (pintype "passive"))
      (node (ref "J1") (pin "39") (pinfunction "39_39") (pintype "passive"))
      (node (ref "J1") (pin "40") (pinfunction "40_40") (pintype "passive"))
      (node (ref "J1") (pin "45") (pinfunction "45_45") (pintype "passive"))
      (node (ref "J1") (pin "46") (pinfunction "46_46") (pintype "passive"))
      (node (ref "J1") (pin "51") (pinfunction "51_51") (pintype "passive"))
      (node (ref "J1") (pin "52") (pinfunction "52_52") (pintype "passive"))
      (node (ref "J1") (pin "65") (pinfunction "65_65") (pintype "passive"))
      (node (ref "J1") (pin "66") (pinfunction "66_66") (pintype "passive"))
      (node (ref "J1") (pin "71") (pinfunction "71_71") (pintype "passive"))
      (node (ref "J1") (pin "72") (pinfunction "72_72") (pintype "passive"))
      (node (ref "J1") (pin "77") (pinfunction "77_77") (pintype "passive"))
      (node (ref "J1") (pin "85") (pinfunction "85_85") (pintype "passive"))
      (node (ref "J1") (pin "86") (pinfunction "86_86") (pintype "passive"))
      (node (ref "J1") (pin "95") (pinfunction "95_95") (pintype "passive"))
      (node (ref "J1") (pin "96") (pinfunction "96_96") (pintype "passive"))
      (node (ref "J10") (pin "2") (pinfunction "2_2") (pintype "passive"))
      (node (ref "J10") (pin "3") (pinfunction "3_3") (pintype "passive"))
      (node (ref "J10") (pin "4") (pinfunction "4_4") (pintype "passive"))
      (node (ref "J10") (pin "5") (pinfunction "5_5") (pintype "passive"))
      (node (ref "J11") (pin "2") (pinfunction "2_2") (pintype "passive"))
      (node (ref "J11") (pin "3") (pinfunction "3_3") (pintype "passive"))
      (node (ref "J11") (pin "4") (pinfunction "4_4") (pintype "passive"))
      (node (ref "J11") (pin "5") (pinfunction "5_5") (pintype "passive"))
      (node (ref "J12") (pin "2") (pinfunction "2_2") (pintype "passive"))
      (node (ref "J12") (pin "3") (pinfunction "3_3") (pintype "passive"))
      (node (ref "J12") (pin "4") (pinfunction "4_4") (pintype "passive"))
      (node (ref "J12") (pin "5") (pinfunction "5_5") (pintype "passive"))
      (node (ref "J13") (pin "2") (pinfunction "2_2") (pintype "passive"))
      (node (ref "J13") (pin "3") (pinfunction "3_3") (pintype "passive"))
      (node (ref "J13") (pin "4") (pinfunction "4_4") (pintype "passive"))
      (node (ref "J13") (pin "5") (pinfunction "5_5") (pintype "passive"))
      (node (ref "J14") (pin "2") (pinfunction "2_2") (pintype "passive"))
      (node (ref "J14") (pin "3") (pinfunction "3_3") (pintype "passive"))
      (node (ref "J14") (pin "4") (pinfunction "4_4") (pintype "passive"))
      (node (ref "J14") (pin "5") (pinfunction "5_5") (pintype "passive"))
      (node (ref "J15") (pin "2") (pinfunction "2_2") (pintype "passive"))
      (node (ref "J15") (pin "3") (pinfunction "3_3") (pintype "passive"))
      (node (ref "J15") (pin "4") (pinfunction "4_4") (pintype "passive"))
      (node (ref "J15") (pin "5") (pinfunction "5_5") (pintype "passive"))
      (node (ref "J16") (pin "2") (pinfunction "2_2") (pintype "passive"))
      (node (ref "J16") (pin "3") (pinfunction "3_3") (pintype "passive"))
      (node (ref "J16") (pin "4") (pinfunction "4_4") (pintype "passive"))
      (node (ref "J16") (pin "5") (pinfunction "5_5") (pintype "passive"))
      (node (ref "J17") (pin "2") (pinfunction "2_2") (pintype "passive"))
      (node (ref "J17") (pin "3") (pinfunction "3_3") (pintype "passive"))
      (node (ref "J17") (pin "4") (pinfunction "4_4") (pintype "passive"))
      (node (ref "J17") (pin "5") (pinfunction "5_5") (pintype "passive"))
      (node (ref "J18") (pin "2") (pinfunction "2_2") (pintype "passive"))
      (node (ref "J18") (pin "3") (pinfunction "3_3") (pintype "passive"))
      (node (ref "J18") (pin "4") (pinfunction "4_4") (pintype "passive"))
      (node (ref "J18") (pin "5") (pinfunction "5_5") (pintype "passive"))
      (node (ref "J2") (pin "15") (pinfunction "15_15") (pintype "passive"))
      (node (ref "J2") (pin "16") (pinfunction "16_16") (pintype "passive"))
      (node (ref "J2") (pin "21") (pinfunction "21_21") (pintype "passive"))
      (node (ref "J2") (pin "22") (pinfunction "22_22") (pintype "passive"))
      (node (ref "J2") (pin "27") (pinfunction "27_27") (pintype "passive"))
      (node (ref "J2") (pin "28") (pinfunction "28_28") (pintype "passive"))
      (node (ref "J2") (pin "33") (pinfunction "33_33") (pintype "passive"))
      (node (ref "J2") (pin "34") (pinfunction "34_34") (pintype "passive"))
      (node (ref "J2") (pin "39") (pinfunction "39_39") (pintype "passive"))
      (node (ref "J2") (pin "40") (pinfunction "40_40") (pintype "passive"))
      (node (ref "J2") (pin "45") (pinfunction "45_45") (pintype "passive"))
      (node (ref "J2") (pin "46") (pinfunction "46_46") (pintype "passive"))
      (node (ref "J2") (pin "51") (pinfunction "51_51") (pintype "passive"))
      (node (ref "J2") (pin "52") (pinfunction "52_52") (pintype "passive"))
      (node (ref "J2") (pin "65") (pinfunction "65_65") (pintype "passive"))
      (node (ref "J2") (pin "66") (pinfunction "66_66") (pintype "passive"))
      (node (ref "J2") (pin "71") (pinfunction "71_71") (pintype "passive"))
      (node (ref "J2") (pin "72") (pinfunction "72_72") (pintype "passive"))
      (node (ref "J2") (pin "77") (pinfunction "77_77") (pintype "passive"))
      (node (ref "J2") (pin "85") (pinfunction "85_85") (pintype "passive"))
      (node (ref "J2") (pin "86") (pinfunction "86_86") (pintype "passive"))
      (node (ref "J2") (pin "91") (pinfunction "91_91") (pintype "passive"))
      (node (ref "J2") (pin "92") (pinfunction "92_92") (pintype "passive"))
      (node (ref "J4") (pin "2") (pinfunction "2_2") (pintype "passive"))
      (node (ref "J4") (pin "3") (pinfunction "3_3") (pintype "passive"))
      (node (ref "J4") (pin "4") (pinfunction "4_4") (pintype "passive"))
      (node (ref "J4") (pin "5") (pinfunction "5_5") (pintype "passive"))
      (node (ref "J8") (pin "2") (pinfunction "2_2") (pintype "passive"))
      (node (ref "J8") (pin "3") (pinfunction "3_3") (pintype "passive"))
      (node (ref "J8") (pin "4") (pinfunction "4_4") (pintype "passive"))
      (node (ref "J8") (pin "5") (pinfunction "5_5") (pintype "passive"))
      (node (ref "J9") (pin "2") (pinfunction "2_2") (pintype "passive"))
      (node (ref "J9") (pin "3") (pinfunction "3_3") (pintype "passive"))
      (node (ref "J9") (pin "4") (pinfunction "4_4") (pintype "passive"))
      (node (ref "J9") (pin "5") (pinfunction "5_5") (pintype "passive"))
      (node (ref "P1") (pin "1") (pinfunction "1_1") (pintype "passive"))
      (node (ref "P1") (pin "19") (pinfunction "19_19") (pintype "passive"))
      (node (ref "P1") (pin "2") (pinfunction "2_2") (pintype "passive"))
      (node (ref "P1") (pin "20") (pinfunction "20_20") (pintype "passive"))
      (node (ref "P10") (pin "1") (pinfunction "1_1") (pintype "passive"))
      (node (ref "P10") (pin "2") (pinfunction "2_2") (pintype "passive"))
      (node (ref "P10") (pin "7") (pinfunction "7_7") (pintype "passive"))
      (node (ref "P10") (pin "8") (pinfunction "8_8") (pintype "passive"))
      (node (ref "P11") (pin "1") (pinfunction "1_1") (pintype "passive"))
      (node (ref "P12") (pin "1") (pinfunction "1_1") (pintype "passive"))
      (node (ref "P16") (pin "3") (pinfunction "3_3") (pintype "passive"))
      (node (ref "P17") (pin "3") (pinfunction "3_3") (pintype "passive"))
      (node (ref "P3") (pin "3") (pinfunction "3_3") (pintype "passive"))
      (node (ref "P4") (pin "3") (pinfunction "3_3") (pintype "passive"))
      (node (ref "P5") (pin "3") (pinfunction "3_3") (pintype "passive"))
      (node (ref "P6") (pin "3") (pinfunction "3_3") (pintype "passive"))
      (node (ref "R1") (pin "1") (pinfunction "1_1") (pintype "passive"))
      (node (ref "R10") (pin "1") (pinfunction "1_1") (pintype "passive"))
      (node (ref "R100") (pin "1") (pinfunction "1_1") (pintype "passive"))
      (node (ref "R11") (pin "2") (pinfunction "2_2") (pintype "passive"))
      (node (ref "R12") (pin "1") (pinfunction "1_1") (pintype "passive"))
      (node (ref "R13") (pin "1") (pinfunction "1_1") (pintype "passive"))
      (node (ref "R132") (pin "2") (pinfunction "2_2") (pintype "passive"))
      (node (ref "R14") (pin "1") (pinfunction "1_1") (pintype "passive"))
      (node (ref "R146") (pin "2") (pinfunction "2_2") (pintype "passive"))
      (node (ref "R15") (pin "1") (pinfunction "1_1") (pintype "passive"))
      (node (ref "R16") (pin "1") (pinfunction "1_1") (pintype "passive"))
      (node (ref "R17") (pin "1") (pinfunction "1_1") (pintype "passive"))
      (node (ref "R18") (pin "1") (pinfunction "1_1") (pintype "passive"))
      (node (ref "R19") (pin "1") (pinfunction "1_1") (pintype "passive"))
      (node (ref "R2") (pin "1") (pinfunction "1_1") (pintype "passive"))
      (node (ref "R20") (pin "1") (pinfunction "1_1") (pintype "passive"))
      (node (ref "R21") (pin "1") (pinfunction "1_1") (pintype "passive"))
      (node (ref "R22") (pin "1") (pinfunction "1_1") (pintype "passive"))
      (node (ref "R3") (pin "1") (pinfunction "1_1") (pintype "passive"))
      (node (ref "R4") (pin "1") (pinfunction "1_1") (pintype "passive"))
      (node (ref "R48") (pin "2") (pinfunction "2_2") (pintype "passive"))
      (node (ref "R49") (pin "2") (pinfunction "2_2") (pintype "passive"))
      (node (ref "R5") (pin "1") (pinfunction "1_1") (pintype "passive"))
      (node (ref "R59") (pin "2") (pinfunction "2_2") (pintype "passive"))
      (node (ref "R6") (pin "1") (pinfunction "1_1") (pintype "passive"))
      (node (ref "R60") (pin "1") (pinfunction "1_1") (pintype "passive"))
      (node (ref "R61") (pin "2") (pinfunction "2_2") (pintype "passive"))
      (node (ref "R62") (pin "1") (pinfunction "1_1") (pintype "passive"))
      (node (ref "R63") (pin "2") (pinfunction "2_2") (pintype "passive"))
      (node (ref "R64") (pin "1") (pinfunction "1_1") (pintype "passive"))
      (node (ref "R65") (pin "2") (pinfunction "2_2") (pintype "passive"))
      (node (ref "R66") (pin "1") (pinfunction "1_1") (pintype "passive"))
      (node (ref "R67") (pin "2") (pinfunction "2_2") (pintype "passive"))
      (node (ref "R68") (pin "1") (pinfunction "1_1") (pintype "passive"))
      (node (ref "R69") (pin "2") (pinfunction "2_2") (pintype "passive"))
      (node (ref "R7") (pin "2") (pinfunction "2_2") (pintype "passive"))
      (node (ref "R72") (pin "2") (pinfunction "2_2") (pintype "passive"))
      (node (ref "R77") (pin "2") (pinfunction "2_2") (pintype "passive"))
      (node (ref "R8") (pin "1") (pinfunction "1_1") (pintype "passive"))
      (node (ref "R99") (pin "1") (pinfunction "1_1") (pintype "passive"))
      (node (ref "SW1") (pin "4") (pinfunction "4_4") (pintype "passive"))
      (node (ref "SW2") (pin "4") (pinfunction "4_4") (pintype "passive"))
      (node (ref "T1") (pin "4") (pinfunction "NC_4") (pintype "passive"))
      (node (ref "T10") (pin "4") (pinfunction "NC_4") (pintype "passive"))
      (node (ref "T4") (pin "4") (pinfunction "NC_4") (pintype "passive"))
      (node (ref "T5") (pin "4") (pinfunction "NC_4") (pintype "passive"))
      (node (ref "T6") (pin "4") (pinfunction "NC_4") (pintype "passive"))
      (node (ref "T7") (pin "4") (pinfunction "NC_4") (pintype "passive"))
      (node (ref "T8") (pin "4") (pinfunction "NC_4") (pintype "passive"))
      (node (ref "T9") (pin "4") (pinfunction "NC_4") (pintype "passive"))
      (node (ref "U1") (pin "A18") (pinfunction "FRAMEN_A18") (pintype "input"))
      (node (ref "U1") (pin "A29") (pinfunction "PARITYN_A29") (pintype "input"))
      (node (ref "U1") (pin "B16") (pinfunction "FRAMEP_B16") (pintype "input"))
      (node (ref "U1") (pin "B26") (pinfunction "PARITYP_B26") (pintype "input"))
      (node (ref "U1") (pin "C1") (pinfunction "GND_C1") (pintype "power_in"))
      (node (ref "U1") (pin "C2") (pinfunction "GND_C2") (pintype "power_in"))
      (node (ref "U1") (pin "C3") (pinfunction "GND_C3") (pintype "power_in"))
      (node (ref "U1") (pin "C4") (pinfunction "GND_C4") (pintype "power_in"))
      (node (ref "U1") (pin "C5") (pinfunction "GND_C5") (pintype "power_in"))
      (node (ref "U22") (pin "3") (pinfunction "3_3") (pintype "passive"))
      (node (ref "U22") (pin "5") (pinfunction "5_5") (pintype "passive"))
      (node (ref "U23") (pin "3") (pinfunction "3_3") (pintype "passive"))
      (node (ref "U23") (pin "5") (pinfunction "5_5") (pintype "passive"))
      (node (ref "U24") (pin "3") (pinfunction "3_3") (pintype "passive"))
      (node (ref "U24") (pin "5") (pinfunction "5_5") (pintype "passive"))
      (node (ref "U25") (pin "3") (pinfunction "3_3") (pintype "passive"))
      (node (ref "U25") (pin "5") (pinfunction "5_5") (pintype "passive"))
      (node (ref "U26") (pin "3") (pinfunction "3_3") (pintype "passive"))
      (node (ref "U26") (pin "5") (pinfunction "5_5") (pintype "passive"))
      (node (ref "U27") (pin "3") (pinfunction "3_3") (pintype "passive"))
      (node (ref "U27") (pin "5") (pinfunction "5_5") (pintype "passive"))
      (node (ref "U28") (pin "3") (pinfunction "3_3") (pintype "passive"))
      (node (ref "U28") (pin "5") (pinfunction "5_5") (pintype "passive"))
      (node (ref "U29") (pin "3") (pinfunction "3_3") (pintype "passive"))
      (node (ref "U29") (pin "5") (pinfunction "5_5") (pintype "passive"))
      (node (ref "U3") (pin "15") (pinfunction "-VS2_15") (pintype "power_in"))
      (node (ref "U3") (pin "16") (pinfunction "-VS2_16") (pintype "power_in"))
      (node (ref "U3") (pin "21") (pinfunction "-VS1_21") (pintype "power_in"))
      (node (ref "U3") (pin "22") (pinfunction "-VS1_22") (pintype "power_in"))
      (node (ref "U3") (pin "25") (pinfunction "EP_25") (pintype "power_in"))
      (node (ref "U30") (pin "1") (pinfunction "GND_1") (pintype "power_in"))
      (node (ref "U5") (pin "1") (pinfunction "FILTA_1") (pintype "input"))
      (node (ref "U5") (pin "12") (pinfunction "SD1_12") (pintype "output"))
      (node (ref "U5") (pin "6") (pinfunction "FILTB_6") (pintype "input"))
      (node (ref "U5") (pin "7") (pinfunction "SD2_7") (pintype "output"))
      (node (ref "U6") (pin "A18") (pinfunction "FRAMEN_A18") (pintype "input"))
      (node (ref "U6") (pin "A29") (pinfunction "PARITYN_A29") (pintype "input"))
      (node (ref "U6") (pin "B16") (pinfunction "FRAMEP_B16") (pintype "input"))
      (node (ref "U6") (pin "B26") (pinfunction "PARITYP_B26") (pintype "input"))
      (node (ref "U6") (pin "C1") (pinfunction "GND_C1") (pintype "power_in"))
      (node (ref "U6") (pin "C2") (pinfunction "GND_C2") (pintype "power_in"))
      (node (ref "U6") (pin "C3") (pinfunction "GND_C3") (pintype "power_in"))
      (node (ref "U6") (pin "C4") (pinfunction "GND_C4") (pintype "power_in"))
      (node (ref "U6") (pin "C5") (pinfunction "GND_C5") (pintype "power_in"))
      (node (ref "U7") (pin "3") (pinfunction "SYNC_3") (pintype "input"))
      (node (ref "U7") (pin "4") (pinfunction "DNC_4") (pintype "passive"))
      (node (ref "U7") (pin "5") (pinfunction "DNC_5") (pintype "passive"))
      (node (ref "U7") (pin "55") (pinfunction "DNC_55") (pintype "passive"))
      (node (ref "U7") (pin "56") (pinfunction "DNC_56") (pintype "passive"))
      (node (ref "U7") (pin "58") (pinfunction "DNC_58") (pintype "passive"))
      (node (ref "U7") (pin "6") (pinfunction "DNC_6") (pintype "passive"))
      (node (ref "U7") (pin "65") (pinfunction "EPAD_65") (pintype "passive"))
      (node (ref "U7") (pin "7") (pinfunction "DNC_7") (pintype "passive"))
    )
    (net (code "243") (name "Net-(C1-Pad2)") (class "Default")
      (node (ref "C1") (pin "2") (pinfunction "2_2") (pintype "passive"))
      (node (ref "C7") (pin "1") (pinfunction "1_1") (pintype "passive"))
      (node (ref "L6") (pin "1") (pinfunction "1_1") (pintype "passive"))
      (node (ref "L7") (pin "2") (pinfunction "2_2") (pintype "passive"))
    )
    (net (code "244") (name "Net-(C2-Pad2)") (class "Default")
      (node (ref "C2") (pin "2") (pinfunction "2_2") (pintype "passive"))
      (node (ref "C8") (pin "1") (pinfunction "1_1") (pintype "passive"))
      (node (ref "L7") (pin "1") (pinfunction "1_1") (pintype "passive"))
      (node (ref "L8") (pin "2") (pinfunction "2_2") (pintype "passive"))
    )
    (net (code "245") (name "Net-(C3-Pad2)") (class "Default")
      (node (ref "C3") (pin "2") (pinfunction "2_2") (pintype "passive"))
      (node (ref "C9") (pin "1") (pinfunction "1_1") (pintype "passive"))
      (node (ref "L8") (pin "1") (pinfunction "1_1") (pintype "passive"))
      (node (ref "L9") (pin "2") (pinfunction "2_2") (pintype "passive"))
    )
    (net (code "246") (name "Net-(C4-Pad2)") (class "Default")
      (node (ref "C4") (pin "2") (pinfunction "2_2") (pintype "passive"))
      (node (ref "C7") (pin "2") (pinfunction "2_2") (pintype "passive"))
      (node (ref "L10") (pin "2") (pinfunction "2_2") (pintype "passive"))
      (node (ref "L11") (pin "1") (pinfunction "1_1") (pintype "passive"))
    )
    (net (code "247") (name "Net-(C5-Pad2)") (class "Default")
      (node (ref "C5") (pin "2") (pinfunction "2_2") (pintype "passive"))
      (node (ref "C8") (pin "2") (pinfunction "2_2") (pintype "passive"))
      (node (ref "L11") (pin "2") (pinfunction "2_2") (pintype "passive"))
      (node (ref "L12") (pin "1") (pinfunction "1_1") (pintype "passive"))
    )
    (net (code "248") (name "Net-(C6-Pad2)") (class "Default")
      (node (ref "C6") (pin "2") (pinfunction "2_2") (pintype "passive"))
      (node (ref "C9") (pin "2") (pinfunction "2_2") (pintype "passive"))
      (node (ref "L12") (pin "2") (pinfunction "2_2") (pintype "passive"))
      (node (ref "L13") (pin "1") (pinfunction "1_1") (pintype "passive"))
    )
    (net (code "249") (name "Net-(C10-Pad2)") (class "Default")
      (node (ref "C10") (pin "2") (pinfunction "2_2") (pintype "passive"))
      (node (ref "C142") (pin "1") (pinfunction "1_1") (pintype "passive"))
      (node (ref "L14") (pin "1") (pinfunction "1_1") (pintype "passive"))
      (node (ref "L15") (pin "2") (pinfunction "2_2") (pintype "passive"))
    )
    (net (code "250") (name "Net-(C11-Pad2)") (class "Default")
      (node (ref "C11") (pin "2") (pinfunction "2_2") (pintype "passive"))
      (node (ref "C143") (pin "1") (pinfunction "1_1") (pintype "passive"))
      (node (ref "L15") (pin "1") (pinfunction "1_1") (pintype "passive"))
      (node (ref "L16") (pin "2") (pinfunction "2_2") (pintype "passive"))
    )
    (net (code "251") (name "Net-(C78-Pad1)") (class "Default")
      (node (ref "C78") (pin "1") (pinfunction "1_1") (pintype "passive"))
      (node (ref "C79") (pin "1") (pinfunction "1_1") (pintype "passive"))
      (node (ref "R45") (pin "1") (pinfunction "1_1") (pintype "passive"))
      (node (ref "R9") (pin "2") (pinfunction "2_2") (pintype "passive"))
    )
    (net (code "252") (name "Net-(C79-Pad2)") (class "Default")
      (node (ref "C79") (pin "2") (pinfunction "2_2") (pintype "passive"))
      (node (ref "C80") (pin "1") (pinfunction "1_1") (pintype "passive"))
      (node (ref "R46") (pin "2") (pinfunction "2_2") (pintype "passive"))
      (node (ref "R47") (pin "1") (pinfunction "1_1") (pintype "passive"))
    )
    (net (code "253") (name "Net-(C81-Pad1)") (class "Default")
      (node (ref "C81") (pin "1") (pinfunction "1_1") (pintype "passive"))
      (node (ref "C83") (pin "1") (pinfunction "1_1") (pintype "passive"))
      (node (ref "R129") (pin "1") (pinfunction "1_1") (pintype "passive"))
      (node (ref "R82") (pin "2") (pinfunction "2_2") (pintype "passive"))
    )
    (net (code "254") (name "Net-(C142-Pad2)") (class "Default")
      (node (ref "C142") (pin "2") (pinfunction "2_2") (pintype "passive"))
      (node (ref "C145") (pin "2") (pinfunction "2_2") (pintype "passive"))
      (node (ref "L18") (pin "2") (pinfunction "2_2") (pintype "passive"))
      (node (ref "L19") (pin "1") (pinfunction "1_1") (pintype "passive"))
    )
    (net (code "255") (name "Net-(C143-Pad2)") (class "Default")
      (node (ref "C143") (pin "2") (pinfunction "2_2") (pintype "passive"))
      (node (ref "C146") (pin "2") (pinfunction "2_2") (pintype "passive"))
      (node (ref "L19") (pin "2") (pinfunction "2_2") (pintype "passive"))
      (node (ref "L20") (pin "1") (pinfunction "1_1") (pintype "passive"))
    )
    (net (code "256") (name "Net-(C144-Pad1)") (class "Default")
      (node (ref "C144") (pin "1") (pinfunction "1_1") (pintype "passive"))
      (node (ref "C19") (pin "2") (pinfunction "2_2") (pintype "passive"))
      (node (ref "L16") (pin "1") (pinfunction "1_1") (pintype "passive"))
      (node (ref "L17") (pin "2") (pinfunction "2_2") (pintype "passive"))
    )
    (net (code "257") (name "Net-(C144-Pad2)") (class "Default")
      (node (ref "C144") (pin "2") (pinfunction "2_2") (pintype "passive"))
      (node (ref "C147") (pin "2") (pinfunction "2_2") (pintype "passive"))
      (node (ref "L20") (pin "2") (pinfunction "2_2") (pintype "passive"))
      (node (ref "L21") (pin "1") (pinfunction "1_1") (pintype "passive"))
    )
    (net (code "258") (name "Net-(C148-Pad2)") (class "Default")
      (node (ref "C148") (pin "2") (pinfunction "2_2") (pintype "passive"))
      (node (ref "C151") (pin "1") (pinfunction "1_1") (pintype "passive"))
      (node (ref "L22") (pin "1") (pinfunction "1_1") (pintype "passive"))
      (node (ref "L23") (pin "2") (pinfunction "2_2") (pintype "passive"))
    )
    (net (code "259") (name "Net-(C149-Pad2)") (class "Default")
      (node (ref "C149") (pin "2") (pinfunction "2_2") (pintype "passive"))
      (node (ref "C152") (pin "1") (pinfunction "1_1") (pintype "passive"))
      (node (ref "L23") (pin "1") (pinfunction "1_1") (pintype "passive"))
      (node (ref "L24") (pin "2") (pinfunction "2_2") (pintype "passive"))
    )
    (net (code "260") (name "Net-(C150-Pad2)") (class "Default")
      (node (ref "C150") (pin "2") (pinfunction "2_2") (pintype "passive"))
      (node (ref "C153") (pin "1") (pinfunction "1_1") (pintype "passive"))
      (node (ref "L24") (pin "1") (pinfunction "1_1") (pintype "passive"))
      (node (ref "L25") (pin "2") (pinfunction "2_2") (pintype "passive"))
    )
    (net (code "261") (name "Net-(C151-Pad2)") (class "Default")
      (node (ref "C151") (pin "2") (pinfunction "2_2") (pintype "passive"))
      (node (ref "C154") (pin "2") (pinfunction "2_2") (pintype "passive"))
      (node (ref "L26") (pin "2") (pinfunction "2_2") (pintype "passive"))
      (node (ref "L27") (pin "1") (pinfunction "1_1") (pintype "passive"))
    )
    (net (code "262") (name "Net-(C152-Pad2)") (class "Default")
      (node (ref "C152") (pin "2") (pinfunction "2_2") (pintype "passive"))
      (node (ref "C155") (pin "2") (pinfunction "2_2") (pintype "passive"))
      (node (ref "L27") (pin "2") (pinfunction "2_2") (pintype "passive"))
      (node (ref "L28") (pin "1") (pinfunction "1_1") (pintype "passive"))
    )
    (net (code "263") (name "Net-(C153-Pad2)") (class "Default")
      (node (ref "C153") (pin "2") (pinfunction "2_2") (pintype "passive"))
      (node (ref "C156") (pin "2") (pinfunction "2_2") (pintype "passive"))
      (node (ref "L28") (pin "2") (pinfunction "2_2") (pintype "passive"))
      (node (ref "L29") (pin "1") (pinfunction "1_1") (pintype "passive"))
    )
    (net (code "264") (name "Net-(C157-Pad2)") (class "Default")
      (node (ref "C157") (pin "2") (pinfunction "2_2") (pintype "passive"))
      (node (ref "C160") (pin "1") (pinfunction "1_1") (pintype "passive"))
      (node (ref "L30") (pin "1") (pinfunction "1_1") (pintype "passive"))
      (node (ref "L31") (pin "2") (pinfunction "2_2") (pintype "passive"))
    )
    (net (code "265") (name "Net-(C158-Pad2)") (class "Default")
      (node (ref "C158") (pin "2") (pinfunction "2_2") (pintype "passive"))
      (node (ref "C161") (pin "1") (pinfunction "1_1") (pintype "passive"))
      (node (ref "L31") (pin "1") (pinfunction "1_1") (pintype "passive"))
      (node (ref "L32") (pin "2") (pinfunction "2_2") (pintype "passive"))
    )
    (net (code "266") (name "Net-(C159-Pad2)") (class "Default")
      (node (ref "C159") (pin "2") (pinfunction "2_2") (pintype "passive"))
      (node (ref "C162") (pin "1") (pinfunction "1_1") (pintype "passive"))
      (node (ref "L32") (pin "1") (pinfunction "1_1") (pintype "passive"))
      (node (ref "L33") (pin "2") (pinfunction "2_2") (pintype "passive"))
    )
    (net (code "267") (name "Net-(C160-Pad2)") (class "Default")
      (node (ref "C160") (pin "2") (pinfunction "2_2") (pintype "passive"))
      (node (ref "C163") (pin "2") (pinfunction "2_2") (pintype "passive"))
      (node (ref "L34") (pin "2") (pinfunction "2_2") (pintype "passive"))
      (node (ref "L35") (pin "1") (pinfunction "1_1") (pintype "passive"))
    )
    (net (code "268") (name "Net-(C161-Pad2)") (class "Default")
      (node (ref "C161") (pin "2") (pinfunction "2_2") (pintype "passive"))
      (node (ref "C164") (pin "2") (pinfunction "2_2") (pintype "passive"))
      (node (ref "L35") (pin "2") (pinfunction "2_2") (pintype "passive"))
      (node (ref "L36") (pin "1") (pinfunction "1_1") (pintype "passive"))
    )
    (net (code "269") (name "Net-(C162-Pad2)") (class "Default")
      (node (ref "C162") (pin "2") (pinfunction "2_2") (pintype "passive"))
      (node (ref "C165") (pin "2") (pinfunction "2_2") (pintype "passive"))
      (node (ref "L36") (pin "2") (pinfunction "2_2") (pintype "passive"))
      (node (ref "L37") (pin "1") (pinfunction "1_1") (pintype "passive"))
    )
    (net (code "270") (name "Net-(C166-Pad2)") (class "Default")
      (node (ref "C166") (pin "2") (pinfunction "2_2") (pintype "passive"))
      (node (ref "C169") (pin "1") (pinfunction "1_1") (pintype "passive"))
      (node (ref "L38") (pin "1") (pinfunction "1_1") (pintype "passive"))
      (node (ref "L39") (pin "2") (pinfunction "2_2") (pintype "passive"))
    )
    (net (code "271") (name "Net-(C167-Pad2)") (class "Default")
      (node (ref "C167") (pin "2") (pinfunction "2_2") (pintype "passive"))
      (node (ref "C170") (pin "1") (pinfunction "1_1") (pintype "passive"))
      (node (ref "L39") (pin "1") (pinfunction "1_1") (pintype "passive"))
      (node (ref "L40") (pin "2") (pinfunction "2_2") (pintype "passive"))
    )
    (net (code "272") (name "Net-(C168-Pad2)") (class "Default")
      (node (ref "C168") (pin "2") (pinfunction "2_2") (pintype "passive"))
      (node (ref "C171") (pin "1") (pinfunction "1_1") (pintype "passive"))
      (node (ref "L40") (pin "1") (pinfunction "1_1") (pintype "passive"))
      (node (ref "L41") (pin "2") (pinfunction "2_2") (pintype "passive"))
    )
    (net (code "273") (name "Net-(C169-Pad2)") (class "Default")
      (node (ref "C169") (pin "2") (pinfunction "2_2") (pintype "passive"))
      (node (ref "C172") (pin "2") (pinfunction "2_2") (pintype "passive"))
      (node (ref "L42") (pin "2") (pinfunction "2_2") (pintype "passive"))
      (node (ref "L43") (pin "1") (pinfunction "1_1") (pintype "passive"))
    )
    (net (code "274") (name "Net-(C170-Pad2)") (class "Default")
      (node (ref "C170") (pin "2") (pinfunction "2_2") (pintype "passive"))
      (node (ref "C173") (pin "2") (pinfunction "2_2") (pintype "passive"))
      (node (ref "L43") (pin "2") (pinfunction "2_2") (pintype "passive"))
      (node (ref "L44") (pin "1") (pinfunction "1_1") (pintype "passive"))
    )
    (net (code "275") (name "Net-(C171-Pad2)") (class "Default")
      (node (ref "C171") (pin "2") (pinfunction "2_2") (pintype "passive"))
      (node (ref "C174") (pin "2") (pinfunction "2_2") (pintype "passive"))
      (node (ref "L44") (pin "2") (pinfunction "2_2") (pintype "passive"))
      (node (ref "L45") (pin "1") (pinfunction "1_1") (pintype "passive"))
    )
    (net (code "276") (name "Net-(C175-Pad2)") (class "Default")
      (node (ref "C175") (pin "2") (pinfunction "2_2") (pintype "passive"))
      (node (ref "C178") (pin "1") (pinfunction "1_1") (pintype "passive"))
      (node (ref "L46") (pin "1") (pinfunction "1_1") (pintype "passive"))
      (node (ref "L47") (pin "2") (pinfunction "2_2") (pintype "passive"))
    )
    (net (code "277") (name "Net-(C176-Pad2)") (class "Default")
      (node (ref "C176") (pin "2") (pinfunction "2_2") (pintype "passive"))
      (node (ref "C179") (pin "1") (pinfunction "1_1") (pintype "passive"))
      (node (ref "L47") (pin "1") (pinfunction "1_1") (pintype "passive"))
      (node (ref "L48") (pin "2") (pinfunction "2_2") (pintype "passive"))
    )
    (net (code "278") (name "Net-(C177-Pad2)") (class "Default")
      (node (ref "C177") (pin "2") (pinfunction "2_2") (pintype "passive"))
      (node (ref "C180") (pin "1") (pinfunction "1_1") (pintype "passive"))
      (node (ref "L48") (pin "1") (pinfunction "1_1") (pintype "passive"))
      (node (ref "L49") (pin "2") (pinfunction "2_2") (pintype "passive"))
    )
    (net (code "279") (name "Net-(C178-Pad2)") (class "Default")
      (node (ref "C178") (pin "2") (pinfunction "2_2") (pintype "passive"))
      (node (ref "C181") (pin "2") (pinfunction "2_2") (pintype "passive"))
      (node (ref "L50") (pin "2") (pinfunction "2_2") (pintype "passive"))
      (node (ref "L51") (pin "1") (pinfunction "1_1") (pintype "passive"))
    )
    (net (code "280") (name "Net-(C179-Pad2)") (class "Default")
      (node (ref "C179") (pin "2") (pinfunction "2_2") (pintype "passive"))
      (node (ref "C182") (pin "2") (pinfunction "2_2") (pintype "passive"))
      (node (ref "L51") (pin "2") (pinfunction "2_2") (pintype "passive"))
      (node (ref "L52") (pin "1") (pinfunction "1_1") (pintype "passive"))
    )
    (net (code "281") (name "Net-(C180-Pad2)") (class "Default")
      (node (ref "C180") (pin "2") (pinfunction "2_2") (pintype "passive"))
      (node (ref "C183") (pin "2") (pinfunction "2_2") (pintype "passive"))
      (node (ref "L52") (pin "2") (pinfunction "2_2") (pintype "passive"))
      (node (ref "L53") (pin "1") (pinfunction "1_1") (pintype "passive"))
    )
    (net (code "282") (name "Net-(C184-Pad2)") (class "Default")
      (node (ref "C184") (pin "2") (pinfunction "2_2") (pintype "passive"))
      (node (ref "C187") (pin "1") (pinfunction "1_1") (pintype "passive"))
      (node (ref "L54") (pin "1") (pinfunction "1_1") (pintype "passive"))
      (node (ref "L55") (pin "2") (pinfunction "2_2") (pintype "passive"))
    )
    (net (code "283") (name "Net-(C185-Pad2)") (class "Default")
      (node (ref "C185") (pin "2") (pinfunction "2_2") (pintype "passive"))
      (node (ref "C188") (pin "1") (pinfunction "1_1") (pintype "passive"))
      (node (ref "L55") (pin "1") (pinfunction "1_1") (pintype "passive"))
      (node (ref "L56") (pin "2") (pinfunction "2_2") (pintype "passive"))
    )
    (net (code "284") (name "Net-(C186-Pad2)") (class "Default")
      (node (ref "C186") (pin "2") (pinfunction "2_2") (pintype "passive"))
      (node (ref "C189") (pin "1") (pinfunction "1_1") (pintype "passive"))
      (node (ref "L56") (pin "1") (pinfunction "1_1") (pintype "passive"))
      (node (ref "L57") (pin "2") (pinfunction "2_2") (pintype "passive"))
    )
    (net (code "285") (name "Net-(C187-Pad2)") (class "Default")
      (node (ref "C187") (pin "2") (pinfunction "2_2") (pintype "passive"))
      (node (ref "C190") (pin "2") (pinfunction "2_2") (pintype "passive"))
      (node (ref "L58") (pin "2") (pinfunction "2_2") (pintype "passive"))
      (node (ref "L59") (pin "1") (pinfunction "1_1") (pintype "passive"))
    )
    (net (code "286") (name "Net-(C188-Pad2)") (class "Default")
      (node (ref "C188") (pin "2") (pinfunction "2_2") (pintype "passive"))
      (node (ref "C191") (pin "2") (pinfunction "2_2") (pintype "passive"))
      (node (ref "L59") (pin "2") (pinfunction "2_2") (pintype "passive"))
      (node (ref "L60") (pin "1") (pinfunction "1_1") (pintype "passive"))
    )
    (net (code "287") (name "Net-(C189-Pad2)") (class "Default")
      (node (ref "C189") (pin "2") (pinfunction "2_2") (pintype "passive"))
      (node (ref "C192") (pin "2") (pinfunction "2_2") (pintype "passive"))
      (node (ref "L60") (pin "2") (pinfunction "2_2") (pintype "passive"))
      (node (ref "L61") (pin "1") (pinfunction "1_1") (pintype "passive"))
    )
    (net (code "288") (name "Net-(C193-Pad2)") (class "Default")
      (node (ref "C193") (pin "2") (pinfunction "2_2") (pintype "passive"))
      (node (ref "C196") (pin "1") (pinfunction "1_1") (pintype "passive"))
      (node (ref "L62") (pin "1") (pinfunction "1_1") (pintype "passive"))
      (node (ref "L63") (pin "2") (pinfunction "2_2") (pintype "passive"))
    )
    (net (code "289") (name "Net-(C194-Pad2)") (class "Default")
      (node (ref "C194") (pin "2") (pinfunction "2_2") (pintype "passive"))
      (node (ref "C197") (pin "1") (pinfunction "1_1") (pintype "passive"))
      (node (ref "L63") (pin "1") (pinfunction "1_1") (pintype "passive"))
      (node (ref "L64") (pin "2") (pinfunction "2_2") (pintype "passive"))
    )
    (net (code "290") (name "Net-(C195-Pad2)") (class "Default")
      (node (ref "C195") (pin "2") (pinfunction "2_2") (pintype "passive"))
      (node (ref "C198") (pin "1") (pinfunction "1_1") (pintype "passive"))
      (node (ref "L64") (pin "1") (pinfunction "1_1") (pintype "passive"))
      (node (ref "L65") (pin "2") (pinfunction "2_2") (pintype "passive"))
    )
    (net (code "291") (name "Net-(C196-Pad2)") (class "Default")
      (node (ref "C196") (pin "2") (pinfunction "2_2") (pintype "passive"))
      (node (ref "C199") (pin "2") (pinfunction "2_2") (pintype "passive"))
      (node (ref "L66") (pin "2") (pinfunction "2_2") (pintype "passive"))
      (node (ref "L67") (pin "1") (pinfunction "1_1") (pintype "passive"))
    )
    (net (code "292") (name "Net-(C197-Pad2)") (class "Default")
      (node (ref "C197") (pin "2") (pinfunction "2_2") (pintype "passive"))
      (node (ref "C200") (pin "2") (pinfunction "2_2") (pintype "passive"))
      (node (ref "L67") (pin "2") (pinfunction "2_2") (pintype "passive"))
      (node (ref "L68") (pin "1") (pinfunction "1_1") (pintype "passive"))
    )
    (net (code "293") (name "Net-(C198-Pad2)") (class "Default")
      (node (ref "C198") (pin "2") (pinfunction "2_2") (pintype "passive"))
      (node (ref "C201") (pin "2") (pinfunction "2_2") (pintype "passive"))
      (node (ref "L68") (pin "2") (pinfunction "2_2") (pintype "passive"))
      (node (ref "L69") (pin "1") (pinfunction "1_1") (pintype "passive"))
    )
    (net (code "294") (name "Net-(C212-Pad1)") (class "Default")
      (node (ref "C212") (pin "1") (pinfunction "1_1") (pintype "passive"))
      (node (ref "R73") (pin "2") (pinfunction "2_2") (pintype "passive"))
    )
    (net (code "295") (name "Net-(C213-Pad1)") (class "Default")
      (node (ref "C213") (pin "1") (pinfunction "1_1") (pintype "passive"))
      (node (ref "R73") (pin "1") (pinfunction "1_1") (pintype "passive"))
      (node (ref "R74") (pin "2") (pinfunction "2_2") (pintype "passive"))
    )
    (net (code "296") (name "Net-(C216-Pad1)") (class "Default")
      (node (ref "C216") (pin "1") (pinfunction "1_1") (pintype "passive"))
      (node (ref "R78") (pin "2") (pinfunction "2_2") (pintype "passive"))
    )
    (net (code "297") (name "Net-(C217-Pad1)") (class "Default")
      (node (ref "C217") (pin "1") (pinfunction "1_1") (pintype "passive"))
      (node (ref "R78") (pin "1") (pinfunction "1_1") (pintype "passive"))
      (node (ref "R79") (pin "2") (pinfunction "2_2") (pintype "passive"))
    )
    (net (code "298") (name "Net-(C261-Pad1)") (class "Default")
      (node (ref "C261") (pin "1") (pinfunction "1_1") (pintype "passive"))
      (node (ref "C83") (pin "2") (pinfunction "2_2") (pintype "passive"))
      (node (ref "R130") (pin "2") (pinfunction "2_2") (pintype "passive"))
      (node (ref "R131") (pin "1") (pinfunction "1_1") (pintype "passive"))
    )
    (net (code "299") (name "Net-(J2-Pad35)") (class "Default")
      (node (ref "J2") (pin "35") (pinfunction "35_35") (pintype "passive"))
      (node (ref "R135") (pin "2") (pinfunction "2_2") (pintype "passive"))
    )
    (net (code "300") (name "Net-(J2-Pad37)") (class "Default")
      (node (ref "J2") (pin "37") (pinfunction "37_37") (pintype "passive"))
      (node (ref "R150") (pin "2") (pinfunction "2_2") (pintype "passive"))
    )
    (net (code "301") (name "Net-(J2-Pad41)") (class "Default")
      (node (ref "J2") (pin "41") (pinfunction "41_41") (pintype "passive"))
      (node (ref "R136") (pin "2") (pinfunction "2_2") (pintype "passive"))
    )
    (net (code "302") (name "Net-(J2-Pad43)") (class "Default")
      (node (ref "J2") (pin "43") (pinfunction "43_43") (pintype "passive"))
      (node (ref "R137") (pin "2") (pinfunction "2_2") (pintype "passive"))
    )
    (net (code "303") (name "Net-(J4-Pad1)") (class "Default")
      (node (ref "J4") (pin "1") (pinfunction "1_1") (pintype "passive"))
      (node (ref "U22") (pin "1") (pinfunction "1_1") (pintype "passive"))
    )
    (net (code "304") (name "Net-(J8-Pad1)") (class "Default")
      (node (ref "J8") (pin "1") (pinfunction "1_1") (pintype "passive"))
      (node (ref "U23") (pin "1") (pinfunction "1_1") (pintype "passive"))
    )
    (net (code "305") (name "Net-(J9-Pad1)") (class "Default")
      (node (ref "J9") (pin "1") (pinfunction "1_1") (pintype "passive"))
      (node (ref "U24") (pin "1") (pinfunction "1_1") (pintype "passive"))
    )
    (net (code "306") (name "Net-(J10-Pad1)") (class "Default")
      (node (ref "J10") (pin "1") (pinfunction "1_1") (pintype "passive"))
      (node (ref "U25") (pin "1") (pinfunction "1_1") (pintype "passive"))
    )
    (net (code "307") (name "Net-(J11-Pad1)") (class "Default")
      (node (ref "J11") (pin "1") (pinfunction "1_1") (pintype "passive"))
      (node (ref "U26") (pin "1") (pinfunction "1_1") (pintype "passive"))
    )
    (net (code "308") (name "Net-(J12-Pad1)") (class "Default")
      (node (ref "J12") (pin "1") (pinfunction "1_1") (pintype "passive"))
      (node (ref "U27") (pin "1") (pinfunction "1_1") (pintype "passive"))
    )
    (net (code "309") (name "Net-(J13-Pad1)") (class "Default")
      (node (ref "J13") (pin "1") (pinfunction "1_1") (pintype "passive"))
      (node (ref "U28") (pin "1") (pinfunction "1_1") (pintype "passive"))
    )
    (net (code "310") (name "Net-(J14-Pad1)") (class "Default")
      (node (ref "J14") (pin "1") (pinfunction "1_1") (pintype "passive"))
      (node (ref "U29") (pin "1") (pinfunction "1_1") (pintype "passive"))
    )
    (net (code "311") (name "Net-(J17-Pad1)") (class "Default")
      (node (ref "J17") (pin "1") (pinfunction "1_1") (pintype "passive"))
      (node (ref "R49") (pin "1") (pinfunction "1_1") (pintype "passive"))
      (node (ref "R80") (pin "1") (pinfunction "1_1") (pintype "passive"))
    )
    (net (code "312") (name "Net-(J18-Pad1)") (class "Default")
      (node (ref "J18") (pin "1") (pinfunction "1_1") (pintype "passive"))
      (node (ref "R133") (pin "1") (pinfunction "1_1") (pintype "passive"))
      (node (ref "R146") (pin "1") (pinfunction "1_1") (pintype "passive"))
    )
    (net (code "313") (name "Net-(R71-Pad2)") (class "Default")
      (node (ref "R71") (pin "2") (pinfunction "2_2") (pintype "passive"))
      (node (ref "R72") (pin "1") (pinfunction "1_1") (pintype "passive"))
    )
    (net (code "314") (name "Net-(R76-Pad2)") (class "Default")
      (node (ref "R76") (pin "2") (pinfunction "2_2") (pintype "passive"))
      (node (ref "R77") (pin "1") (pinfunction "1_1") (pintype "passive"))
    )
    (net (code "315") (name "Net-(T1-Primary)") (class "Default")
      (node (ref "L9") (pin "1") (pinfunction "1_1") (pintype "passive"))
      (node (ref "R1") (pin "2") (pinfunction "2_2") (pintype "passive"))
      (node (ref "T1") (pin "2") (pinfunction "Primary_2") (pintype "passive"))
    )
    (net (code "316") (name "Net-(T1-Primary_Dot)") (class "Default")
      (node (ref "L13") (pin "2") (pinfunction "2_2") (pintype "passive"))
      (node (ref "R7") (pin "1") (pinfunction "1_1") (pintype "passive"))
      (node (ref "T1") (pin "1") (pinfunction "Primary_Dot_1") (pintype "passive"))
    )
    (net (code "317") (name "Net-(T1-Secondary)") (class "Default")
      (node (ref "T1") (pin "3") (pinfunction "Secondary_3") (pintype "passive"))
      (node (ref "U22") (pin "6") (pinfunction "6_6") (pintype "passive"))
    )
    (net (code "318") (name "Net-(T1-Secondary_Dot)") (class "Default")
      (node (ref "T1") (pin "5") (pinfunction "Secondary_Dot_5") (pintype "passive"))
      (node (ref "U22") (pin "4") (pinfunction "4_4") (pintype "passive"))
    )
    (net (code "319") (name "Net-(T4-Primary)") (class "Default")
      (node (ref "L17") (pin "1") (pinfunction "1_1") (pintype "passive"))
      (node (ref "R10") (pin "2") (pinfunction "2_2") (pintype "passive"))
      (node (ref "T4") (pin "2") (pinfunction "Primary_2") (pintype "passive"))
    )
    (net (code "320") (name "Net-(T4-Primary_Dot)") (class "Default")
      (node (ref "L21") (pin "2") (pinfunction "2_2") (pintype "passive"))
      (node (ref "R11") (pin "1") (pinfunction "1_1") (pintype "passive"))
      (node (ref "T4") (pin "1") (pinfunction "Primary_Dot_1") (pintype "passive"))
    )
    (net (code "321") (name "Net-(T4-Secondary)") (class "Default")
      (node (ref "T4") (pin "3") (pinfunction "Secondary_3") (pintype "passive"))
      (node (ref "U23") (pin "6") (pinfunction "6_6") (pintype "passive"))
    )
    (net (code "322") (name "Net-(T4-Secondary_Dot)") (class "Default")
      (node (ref "T4") (pin "5") (pinfunction "Secondary_Dot_5") (pintype "passive"))
      (node (ref "U23") (pin "4") (pinfunction "4_4") (pintype "passive"))
    )
    (net (code "323") (name "Net-(T5-Primary)") (class "Default")
      (node (ref "L25") (pin "1") (pinfunction "1_1") (pintype "passive"))
      (node (ref "R12") (pin "2") (pinfunction "2_2") (pintype "passive"))
      (node (ref "T5") (pin "2") (pinfunction "Primary_2") (pintype "passive"))
    )
    (net (code "324") (name "Net-(T5-Primary_Dot)") (class "Default")
      (node (ref "L29") (pin "2") (pinfunction "2_2") (pintype "passive"))
      (node (ref "R59") (pin "1") (pinfunction "1_1") (pintype "passive"))
      (node (ref "T5") (pin "1") (pinfunction "Primary_Dot_1") (pintype "passive"))
    )
    (net (code "325") (name "Net-(T5-Secondary)") (class "Default")
      (node (ref "T5") (pin "3") (pinfunction "Secondary_3") (pintype "passive"))
      (node (ref "U24") (pin "6") (pinfunction "6_6") (pintype "passive"))
    )
    (net (code "326") (name "Net-(T5-Secondary_Dot)") (class "Default")
      (node (ref "T5") (pin "5") (pinfunction "Secondary_Dot_5") (pintype "passive"))
      (node (ref "U24") (pin "4") (pinfunction "4_4") (pintype "passive"))
    )
    (net (code "327") (name "Net-(T6-Primary)") (class "Default")
      (node (ref "L33") (pin "1") (pinfunction "1_1") (pintype "passive"))
      (node (ref "R60") (pin "2") (pinfunction "2_2") (pintype "passive"))
      (node (ref "T6") (pin "2") (pinfunction "Primary_2") (pintype "passive"))
    )
    (net (code "328") (name "Net-(T6-Primary_Dot)") (class "Default")
      (node (ref "L37") (pin "2") (pinfunction "2_2") (pintype "passive"))
      (node (ref "R61") (pin "1") (pinfunction "1_1") (pintype "passive"))
      (node (ref "T6") (pin "1") (pinfunction "Primary_Dot_1") (pintype "passive"))
    )
    (net (code "329") (name "Net-(T6-Secondary)") (class "Default")
      (node (ref "T6") (pin "3") (pinfunction "Secondary_3") (pintype "passive"))
      (node (ref "U25") (pin "6") (pinfunction "6_6") (pintype "passive"))
    )
    (net (code "330") (name "Net-(T6-Secondary_Dot)") (class "Default")
      (node (ref "T6") (pin "5") (pinfunction "Secondary_Dot_5") (pintype "passive"))
      (node (ref "U25") (pin "4") (pinfunction "4_4") (pintype "passive"))
    )
    (net (code "331") (name "Net-(T7-Primary)") (class "Default")
      (node (ref "L41") (pin "1") (pinfunction "1_1") (pintype "passive"))
      (node (ref "R62") (pin "2") (pinfunction "2_2") (pintype "passive"))
      (node (ref "T7") (pin "2") (pinfunction "Primary_2") (pintype "passive"))
    )
    (net (code "332") (name "Net-(T7-Primary_Dot)") (class "Default")
      (node (ref "L45") (pin "2") (pinfunction "2_2") (pintype "passive"))
      (node (ref "R63") (pin "1") (pinfunction "1_1") (pintype "passive"))
      (node (ref "T7") (pin "1") (pinfunction "Primary_Dot_1") (pintype "passive"))
    )
    (net (code "333") (name "Net-(T7-Secondary)") (class "Default")
      (node (ref "T7") (pin "3") (pinfunction "Secondary_3") (pintype "passive"))
      (node (ref "U26") (pin "6") (pinfunction "6_6") (pintype "passive"))
    )
    (net (code "334") (name "Net-(T7-Secondary_Dot)") (class "Default")
      (node (ref "T7") (pin "5") (pinfunction "Secondary_Dot_5") (pintype "passive"))
      (node (ref "U26") (pin "4") (pinfunction "4_4") (pintype "passive"))
    )
    (net (code "335") (name "Net-(T8-Primary)") (class "Default")
      (node (ref "L49") (pin "1") (pinfunction "1_1") (pintype "passive"))
      (node (ref "R64") (pin "2") (pinfunction "2_2") (pintype "passive"))
      (node (ref "T8") (pin "2") (pinfunction "Primary_2") (pintype "passive"))
    )
    (net (code "336") (name "Net-(T8-Primary_Dot)") (class "Default")
      (node (ref "L53") (pin "2") (pinfunction "2_2") (pintype "passive"))
      (node (ref "R65") (pin "1") (pinfunction "1_1") (pintype "passive"))
      (node (ref "T8") (pin "1") (pinfunction "Primary_Dot_1") (pintype "passive"))
    )
    (net (code "337") (name "Net-(T8-Secondary)") (class "Default")
      (node (ref "T8") (pin "3") (pinfunction "Secondary_3") (pintype "passive"))
      (node (ref "U27") (pin "6") (pinfunction "6_6") (pintype "passive"))
    )
    (net (code "338") (name "Net-(T8-Secondary_Dot)") (class "Default")
      (node (ref "T8") (pin "5") (pinfunction "Secondary_Dot_5") (pintype "passive"))
      (node (ref "U27") (pin "4") (pinfunction "4_4") (pintype "passive"))
    )
    (net (code "339") (name "Net-(T9-Primary)") (class "Default")
      (node (ref "L57") (pin "1") (pinfunction "1_1") (pintype "passive"))
      (node (ref "R66") (pin "2") (pinfunction "2_2") (pintype "passive"))
      (node (ref "T9") (pin "2") (pinfunction "Primary_2") (pintype "passive"))
    )
    (net (code "340") (name "Net-(T9-Primary_Dot)") (class "Default")
      (node (ref "L61") (pin "2") (pinfunction "2_2") (pintype "passive"))
      (node (ref "R67") (pin "1") (pinfunction "1_1") (pintype "passive"))
      (node (ref "T9") (pin "1") (pinfunction "Primary_Dot_1") (pintype "passive"))
    )
    (net (code "341") (name "Net-(T9-Secondary)") (class "Default")
      (node (ref "T9") (pin "3") (pinfunction "Secondary_3") (pintype "passive"))
      (node (ref "U28") (pin "6") (pinfunction "6_6") (pintype "passive"))
    )
    (net (code "342") (name "Net-(T9-Secondary_Dot)") (class "Default")
      (node (ref "T9") (pin "5") (pinfunction "Secondary_Dot_5") (pintype "passive"))
      (node (ref "U28") (pin "4") (pinfunction "4_4") (pintype "passive"))
    )
    (net (code "343") (name "Net-(T10-Primary)") (class "Default")
      (node (ref "L65") (pin "1") (pinfunction "1_1") (pintype "passive"))
      (node (ref "R68") (pin "2") (pinfunction "2_2") (pintype "passive"))
      (node (ref "T10") (pin "2") (pinfunction "Primary_2") (pintype "passive"))
    )
    (net (code "344") (name "Net-(T10-Primary_Dot)") (class "Default")
      (node (ref "L69") (pin "2") (pinfunction "2_2") (pintype "passive"))
      (node (ref "R69") (pin "1") (pinfunction "1_1") (pintype "passive"))
      (node (ref "T10") (pin "1") (pinfunction "Primary_Dot_1") (pintype "passive"))
    )
    (net (code "345") (name "Net-(T10-Secondary)") (class "Default")
      (node (ref "T10") (pin "3") (pinfunction "Secondary_3") (pintype "passive"))
      (node (ref "U29") (pin "6") (pinfunction "6_6") (pintype "passive"))
    )
    (net (code "346") (name "Net-(T10-Secondary_Dot)") (class "Default")
      (node (ref "T10") (pin "5") (pinfunction "Secondary_Dot_5") (pintype "passive"))
      (node (ref "U29") (pin "4") (pinfunction "4_4") (pintype "passive"))
    )
    (net (code "347") (name "Net-(U1A-ALARM)") (class "Default")
      (node (ref "TP5") (pin "1") (pinfunction "1_1") (pintype "passive"))
      (node (ref "U1") (pin "B29") (pinfunction "ALARM_B29") (pintype "tri_state"))
    )
    (net (code "348") (name "Net-(U1A-LPF)") (class "Default")
      (node (ref "R74") (pin "1") (pinfunction "1_1") (pintype "passive"))
      (node (ref "U1") (pin "A1") (pinfunction "LPF_A1") (pintype "passive"))
    )
    (net (code "349") (name "Net-(U1A-RESETB)") (class "Default")
      (node (ref "C210") (pin "1") (pinfunction "1_1") (pintype "passive"))
      (node (ref "R70") (pin "1") (pinfunction "1_1") (pintype "passive"))
      (node (ref "SW1") (pin "2") (pinfunction "2_2") (pintype "passive"))
      (node (ref "U1") (pin "B30") (pinfunction "RESETB_B30") (pintype "input"))
    )
    (net (code "350") (name "Net-(U1A-SLEEP)") (class "Default")
      (node (ref "P4") (pin "2") (pinfunction "2_2") (pintype "passive"))
      (node (ref "U1") (pin "B40") (pinfunction "SLEEP_B40") (pintype "input"))
    )
    (net (code "351") (name "Net-(U1A-TESTMODE)") (class "Default")
      (node (ref "TP6") (pin "1") (pinfunction "1_1") (pintype "passive"))
      (node (ref "U1") (pin "A44") (pinfunction "TESTMODE_A44") (pintype "passive"))
    )
    (net (code "352") (name "Net-(U1A-TXENABLE)") (class "Default")
      (node (ref "P3") (pin "2") (pinfunction "2_2") (pintype "passive"))
      (node (ref "U1") (pin "A32") (pinfunction "TXENABLE_A32") (pintype "input"))
    )
    (net (code "353") (name "Net-(U3-+FB1)") (class "Default")
      (node (ref "R50") (pin "2") (pinfunction "2_2") (pintype "passive"))
      (node (ref "U3") (pin "2") (pinfunction "+FB1_2") (pintype "passive"))
    )
    (net (code "354") (name "Net-(U3-+FB2)") (class "Default")
      (node (ref "R134") (pin "2") (pinfunction "2_2") (pintype "passive"))
      (node (ref "U3") (pin "8") (pinfunction "+FB2_8") (pintype "passive"))
    )
    (net (code "355") (name "Net-(U3-+IN1)") (class "Default")
      (node (ref "R48") (pin "1") (pinfunction "1_1") (pintype "passive"))
      (node (ref "R50") (pin "1") (pinfunction "1_1") (pintype "passive"))
      (node (ref "U3") (pin "24") (pinfunction "+IN1_24") (pintype "tri_state"))
    )
    (net (code "356") (name "Net-(U3-+IN2)") (class "Default")
      (node (ref "R132") (pin "1") (pinfunction "1_1") (pintype "passive"))
      (node (ref "R134") (pin "1") (pinfunction "1_1") (pintype "passive"))
      (node (ref "U3") (pin "6") (pinfunction "+IN2_6") (pintype "tri_state"))
    )
    (net (code "357") (name "Net-(U3-+OUT1)") (class "Default")
      (node (ref "R9") (pin "1") (pinfunction "1_1") (pintype "passive"))
      (node (ref "U3") (pin "18") (pinfunction "+OUT1_18") (pintype "passive"))
    )
    (net (code "358") (name "Net-(U3-+OUT2)") (class "Default")
      (node (ref "R82") (pin "1") (pinfunction "1_1") (pintype "passive"))
      (node (ref "U3") (pin "12") (pinfunction "+OUT2_12") (pintype "passive"))
    )
    (net (code "359") (name "Net-(U3--FB1)") (class "Default")
      (node (ref "R81") (pin "2") (pinfunction "2_2") (pintype "passive"))
      (node (ref "U3") (pin "23") (pinfunction "-FB1_23") (pintype "passive"))
    )
    (net (code "360") (name "Net-(U3--FB2)") (class "Default")
      (node (ref "R145") (pin "2") (pinfunction "2_2") (pintype "passive"))
      (node (ref "U3") (pin "5") (pinfunction "-FB2_5") (pintype "passive"))
    )
    (net (code "361") (name "Net-(U3--IN1)") (class "Default")
      (node (ref "R80") (pin "2") (pinfunction "2_2") (pintype "passive"))
      (node (ref "R81") (pin "1") (pinfunction "1_1") (pintype "passive"))
      (node (ref "U3") (pin "1") (pinfunction "-IN1_1") (pintype "tri_state"))
    )
    (net (code "362") (name "Net-(U3--IN2)") (class "Default")
      (node (ref "R133") (pin "2") (pinfunction "2_2") (pintype "passive"))
      (node (ref "R145") (pin "1") (pinfunction "1_1") (pintype "passive"))
      (node (ref "U3") (pin "7") (pinfunction "-IN2_7") (pintype "tri_state"))
    )
    (net (code "363") (name "Net-(U3--OUT1)") (class "Default")
      (node (ref "R46") (pin "1") (pinfunction "1_1") (pintype "passive"))
      (node (ref "U3") (pin "19") (pinfunction "-OUT1_19") (pintype "passive"))
    )
    (net (code "364") (name "Net-(U3--OUT2)") (class "Default")
      (node (ref "R130") (pin "1") (pinfunction "1_1") (pintype "passive"))
      (node (ref "U3") (pin "13") (pinfunction "-OUT2_13") (pintype "passive"))
    )
    (net (code "365") (name "Net-(U3-~{PD1})") (class "Default")
      (node (ref "P11") (pin "2") (pinfunction "2_2") (pintype "passive"))
      (node (ref "U3") (pin "20") (pinfunction "~{PD1}_20") (pintype "input"))
    )
    (net (code "366") (name "Net-(U3-~{PD2})") (class "Default")
      (node (ref "P12") (pin "2") (pinfunction "2_2") (pintype "passive"))
      (node (ref "U3") (pin "14") (pinfunction "~{PD2}_14") (pintype "input"))
    )
    (net (code "367") (name "Net-(U6A-ALARM)") (class "Default")
      (node (ref "TP7") (pin "1") (pinfunction "1_1") (pintype "passive"))
      (node (ref "U6") (pin "B29") (pinfunction "ALARM_B29") (pintype "tri_state"))
    )
    (net (code "368") (name "Net-(U6A-LPF)") (class "Default")
      (node (ref "R79") (pin "1") (pinfunction "1_1") (pintype "passive"))
      (node (ref "U6") (pin "A1") (pinfunction "LPF_A1") (pintype "passive"))
    )
    (net (code "369") (name "Net-(U6A-RESETB)") (class "Default")
      (node (ref "C214") (pin "1") (pinfunction "1_1") (pintype "passive"))
      (node (ref "R75") (pin "1") (pinfunction "1_1") (pintype "passive"))
      (node (ref "SW2") (pin "2") (pinfunction "2_2") (pintype "passive"))
      (node (ref "U6") (pin "B30") (pinfunction "RESETB_B30") (pintype "input"))
    )
    (net (code "370") (name "Net-(U6A-SLEEP)") (class "Default")
      (node (ref "P6") (pin "2") (pinfunction "2_2") (pintype "passive"))
      (node (ref "U6") (pin "B40") (pinfunction "SLEEP_B40") (pintype "input"))
    )
    (net (code "371") (name "Net-(U6A-TESTMODE)") (class "Default")
      (node (ref "TP8") (pin "1") (pinfunction "1_1") (pintype "passive"))
      (node (ref "U6") (pin "A44") (pinfunction "TESTMODE_A44") (pintype "passive"))
    )
    (net (code "372") (name "Net-(U6A-TXENABLE)") (class "Default")
      (node (ref "P5") (pin "2") (pinfunction "2_2") (pintype "passive"))
      (node (ref "U6") (pin "A32") (pinfunction "TXENABLE_A32") (pintype "input"))
    )
    (net (code "373") (name "Net-(U7-OEB)") (class "Default")
      (node (ref "P17") (pin "2") (pinfunction "2_2") (pintype "passive"))
      (node (ref "U7") (pin "47") (pinfunction "OEB_47") (pintype "bidirectional"))
    )
    (net (code "374") (name "Net-(U7-PDWN)") (class "Default")
      (node (ref "P16") (pin "2") (pinfunction "2_2") (pintype "passive"))
      (node (ref "U7") (pin "48") (pinfunction "PDWN_48") (pintype "bidirectional"))
    )
    (net (code "375") (name "Net-(U7-VCM)") (class "Default")
      (node (ref "C264") (pin "1") (pinfunction "1_1") (pintype "passive"))
      (node (ref "R147") (pin "1") (pinfunction "1_1") (pintype "passive"))
      (node (ref "U7") (pin "57") (pinfunction "VCM_57") (pintype "output"))
    )
    (net (code "376") (name "unconnected-(J1-Pad1)") (class "Default")
      (node (ref "J1") (pin "1") (pinfunction "1_1") (pintype "passive"))
    )
    (net (code "377") (name "unconnected-(J1-Pad2)") (class "Default")
      (node (ref "J1") (pin "2") (pinfunction "2_2") (pintype "passive"))
    )
    (net (code "378") (name "unconnected-(J1-Pad3)") (class "Default")
      (node (ref "J1") (pin "3") (pinfunction "3_3") (pintype "passive"))
    )
    (net (code "379") (name "unconnected-(J1-Pad4)") (class "Default")
      (node (ref "J1") (pin "4") (pinfunction "4_4") (pintype "passive"))
    )
    (net (code "380") (name "unconnected-(J1-Pad5)") (class "Default")
      (node (ref "J1") (pin "5") (pinfunction "5_5") (pintype "passive"))
    )
    (net (code "381") (name "unconnected-(J1-Pad6)") (class "Default")
      (node (ref "J1") (pin "6") (pinfunction "6_6") (pintype "passive"))
    )
    (net (code "382") (name "unconnected-(J1-Pad7)") (class "Default")
      (node (ref "J1") (pin "7") (pinfunction "7_7") (pintype "passive"))
    )
    (net (code "383") (name "unconnected-(J1-Pad8)") (class "Default")
      (node (ref "J1") (pin "8") (pinfunction "8_8") (pintype "passive"))
    )
    (net (code "384") (name "unconnected-(J1-Pad9)") (class "Default")
      (node (ref "J1") (pin "9") (pinfunction "9_9") (pintype "passive"))
    )
    (net (code "385") (name "unconnected-(J1-Pad10)") (class "Default")
      (node (ref "J1") (pin "10") (pinfunction "10_10") (pintype "passive"))
    )
    (net (code "386") (name "unconnected-(J2-Pad9)") (class "Default")
      (node (ref "J2") (pin "9") (pinfunction "9_9") (pintype "passive"))
    )
    (net (code "387") (name "unconnected-(J2-Pad10)") (class "Default")
      (node (ref "J2") (pin "10") (pinfunction "10_10") (pintype "passive"))
    )
    (net (code "388") (name "unconnected-(J2-Pad11)") (class "Default")
      (node (ref "J2") (pin "11") (pinfunction "11_11") (pintype "passive"))
    )
    (net (code "389") (name "unconnected-(J2-Pad13)") (class "Default")
      (node (ref "J2") (pin "13") (pinfunction "13_13") (pintype "passive"))
    )
    (net (code "390") (name "unconnected-(J2-Pad14)") (class "Default")
      (node (ref "J2") (pin "14") (pinfunction "14_14") (pintype "passive"))
    )
    (net (code "391") (name "unconnected-(J2-Pad100)") (class "Default")
      (node (ref "J2") (pin "100") (pinfunction "100_100") (pintype "passive"))
    )
    (net (code "392") (name "unconnected-(SW1-Pad1)") (class "Default")
      (node (ref "SW1") (pin "1") (pinfunction "1_1") (pintype "passive"))
    )
    (net (code "393") (name "unconnected-(SW1-Pad3)") (class "Default")
      (node (ref "SW1") (pin "3") (pinfunction "3_3") (pintype "passive"))
    )
    (net (code "394") (name "unconnected-(SW2-Pad1)") (class "Default")
      (node (ref "SW2") (pin "1") (pinfunction "1_1") (pintype "passive"))
    )
    (net (code "395") (name "unconnected-(SW2-Pad3)") (class "Default")
      (node (ref "SW2") (pin "3") (pinfunction "3_3") (pintype "passive"))
    )
    (net (code "396") (name "unconnected-(U5-GND-Pad5)") (class "Default")
      (node (ref "U5") (pin "5") (pinfunction "GND_5") (pintype "power_in"))
    )
    (net (code "397") (name "unconnected-(U22-Pad2)") (class "Default")
      (node (ref "U22") (pin "2") (pinfunction "2_2") (pintype "passive"))
    )
    (net (code "398") (name "unconnected-(U23-Pad2)") (class "Default")
      (node (ref "U23") (pin "2") (pinfunction "2_2") (pintype "passive"))
    )
    (net (code "399") (name "unconnected-(U24-Pad2)") (class "Default")
      (node (ref "U24") (pin "2") (pinfunction "2_2") (pintype "passive"))
    )
    (net (code "400") (name "unconnected-(U25-Pad2)") (class "Default")
      (node (ref "U25") (pin "2") (pinfunction "2_2") (pintype "passive"))
    )
    (net (code "401") (name "unconnected-(U26-Pad2)") (class "Default")
      (node (ref "U26") (pin "2") (pinfunction "2_2") (pintype "passive"))
    )
    (net (code "402") (name "unconnected-(U27-Pad2)") (class "Default")
      (node (ref "U27") (pin "2") (pinfunction "2_2") (pintype "passive"))
    )
    (net (code "403") (name "unconnected-(U28-Pad2)") (class "Default")
      (node (ref "U28") (pin "2") (pinfunction "2_2") (pintype "passive"))
    )
    (net (code "404") (name "unconnected-(U29-Pad2)") (class "Default")
      (node (ref "U29") (pin "2") (pinfunction "2_2") (pintype "passive"))
    )
    (net (code "405") (name "unconnected-(U30-NC-Pad4)") (class "Default")
      (node (ref "U30") (pin "4") (pinfunction "NC_4") (pintype "passive"))
    )
  )
)
